# cfc-card.net
KiCad netlist of a schematic drawn in EAGLE
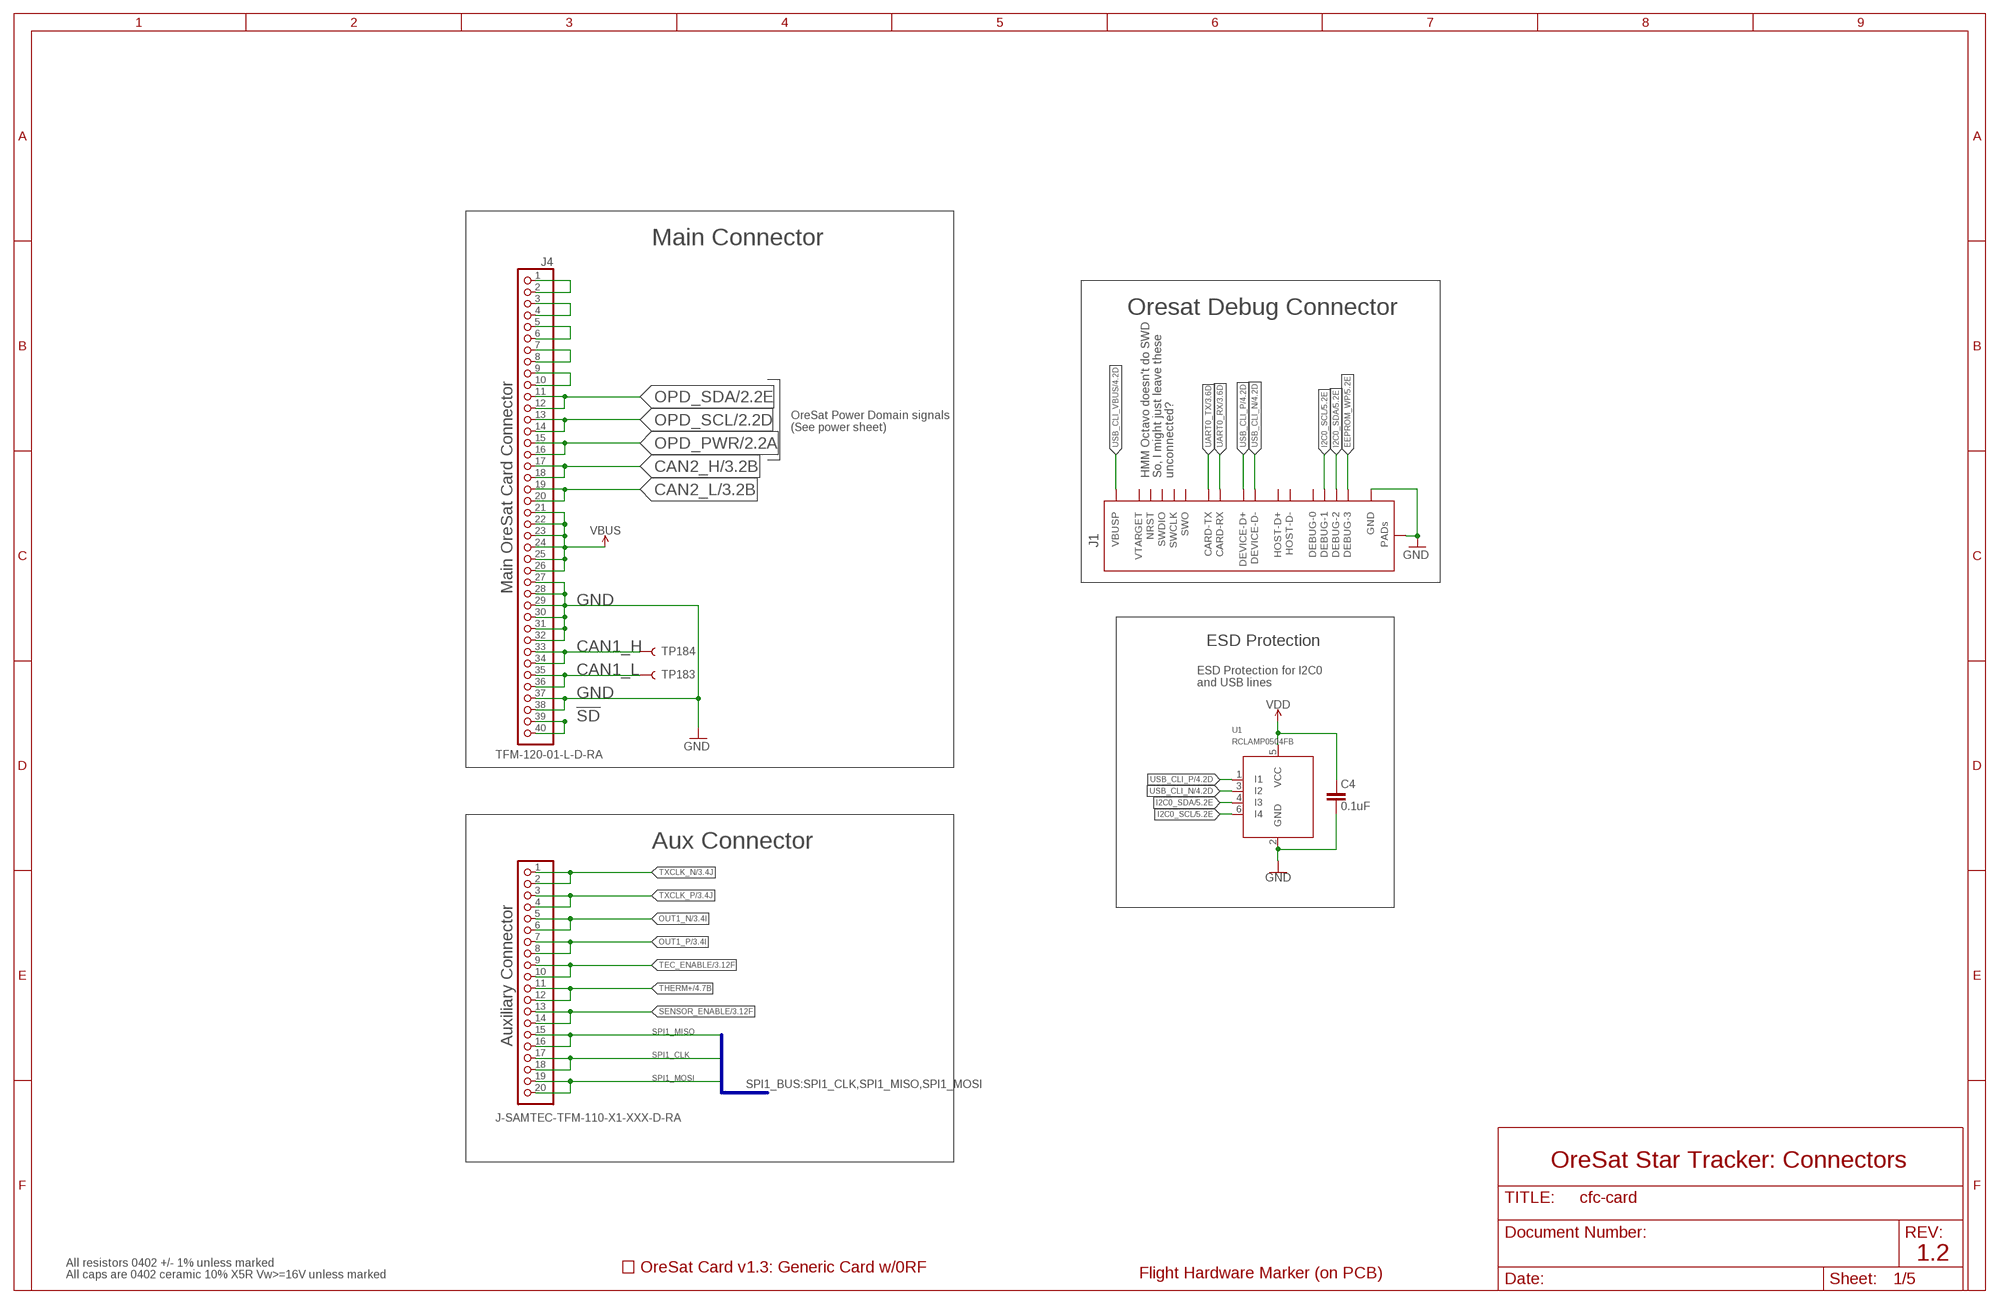
[diagram p0: schematic, sheet 1]
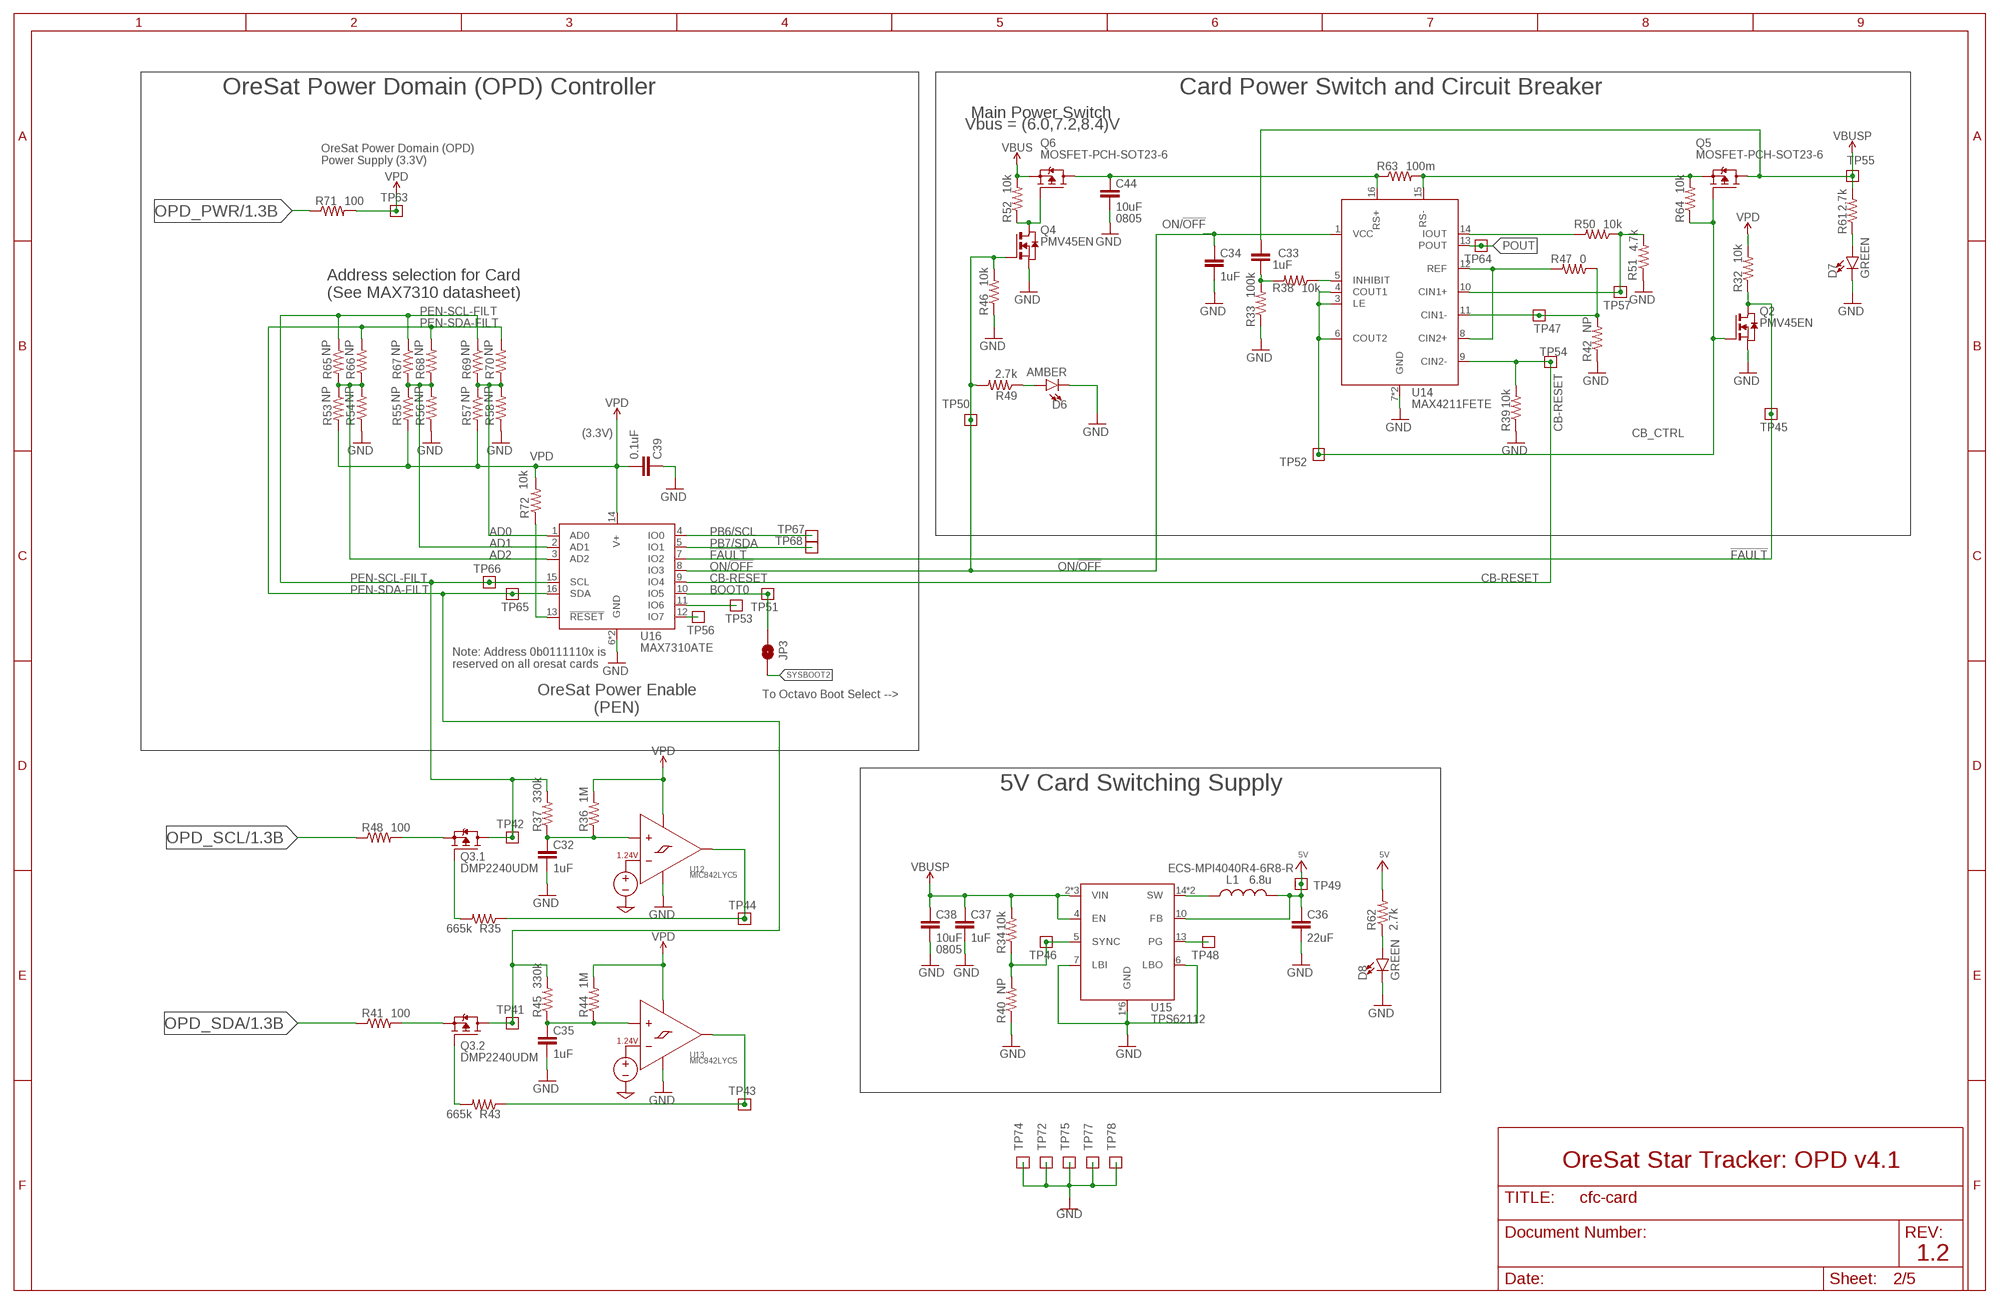
[diagram p1: schematic, sheet 2]
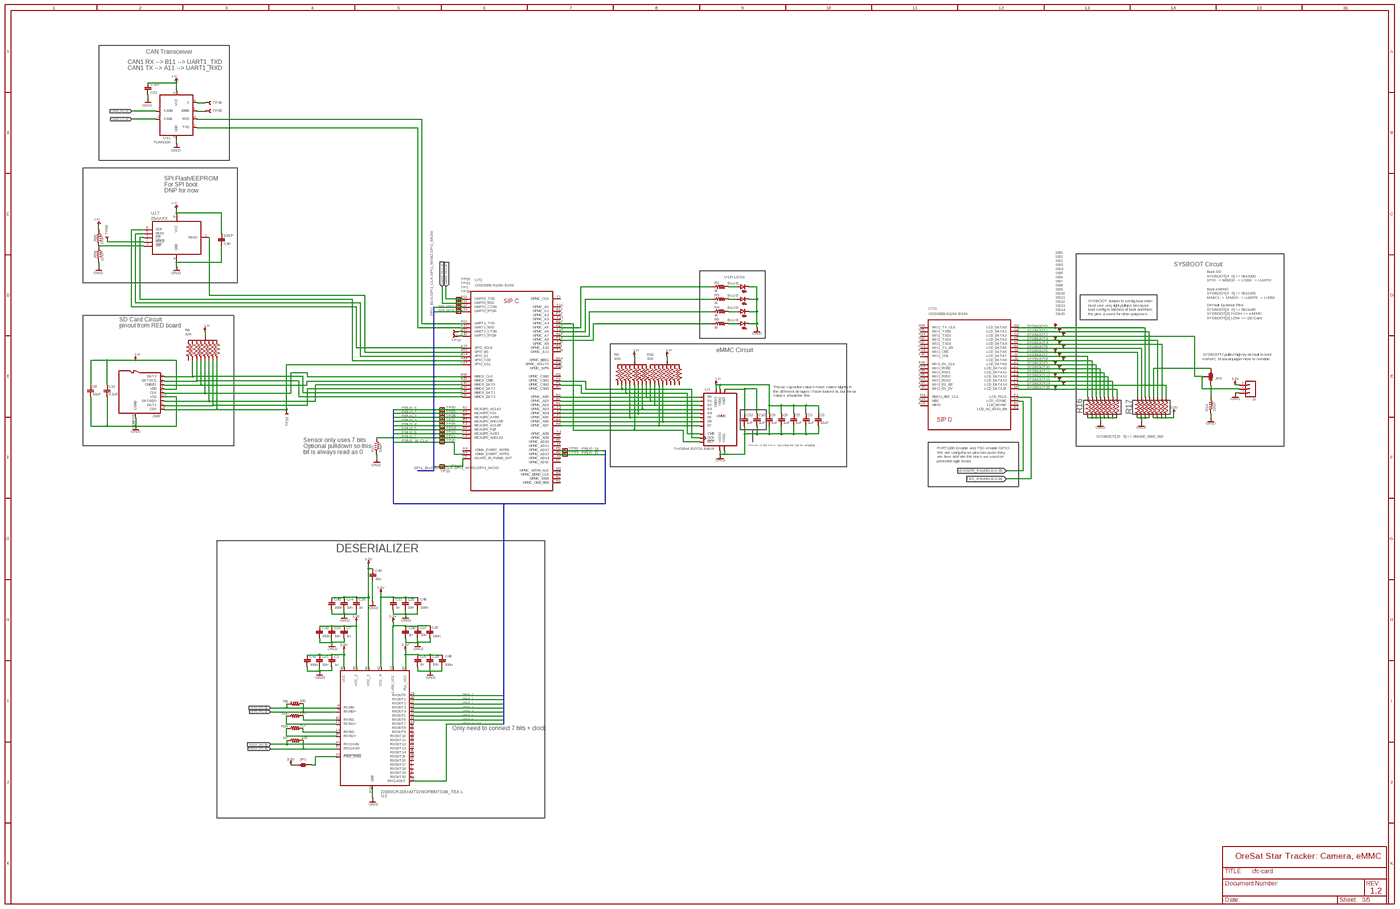
[diagram p2: schematic, sheet 3, overview]
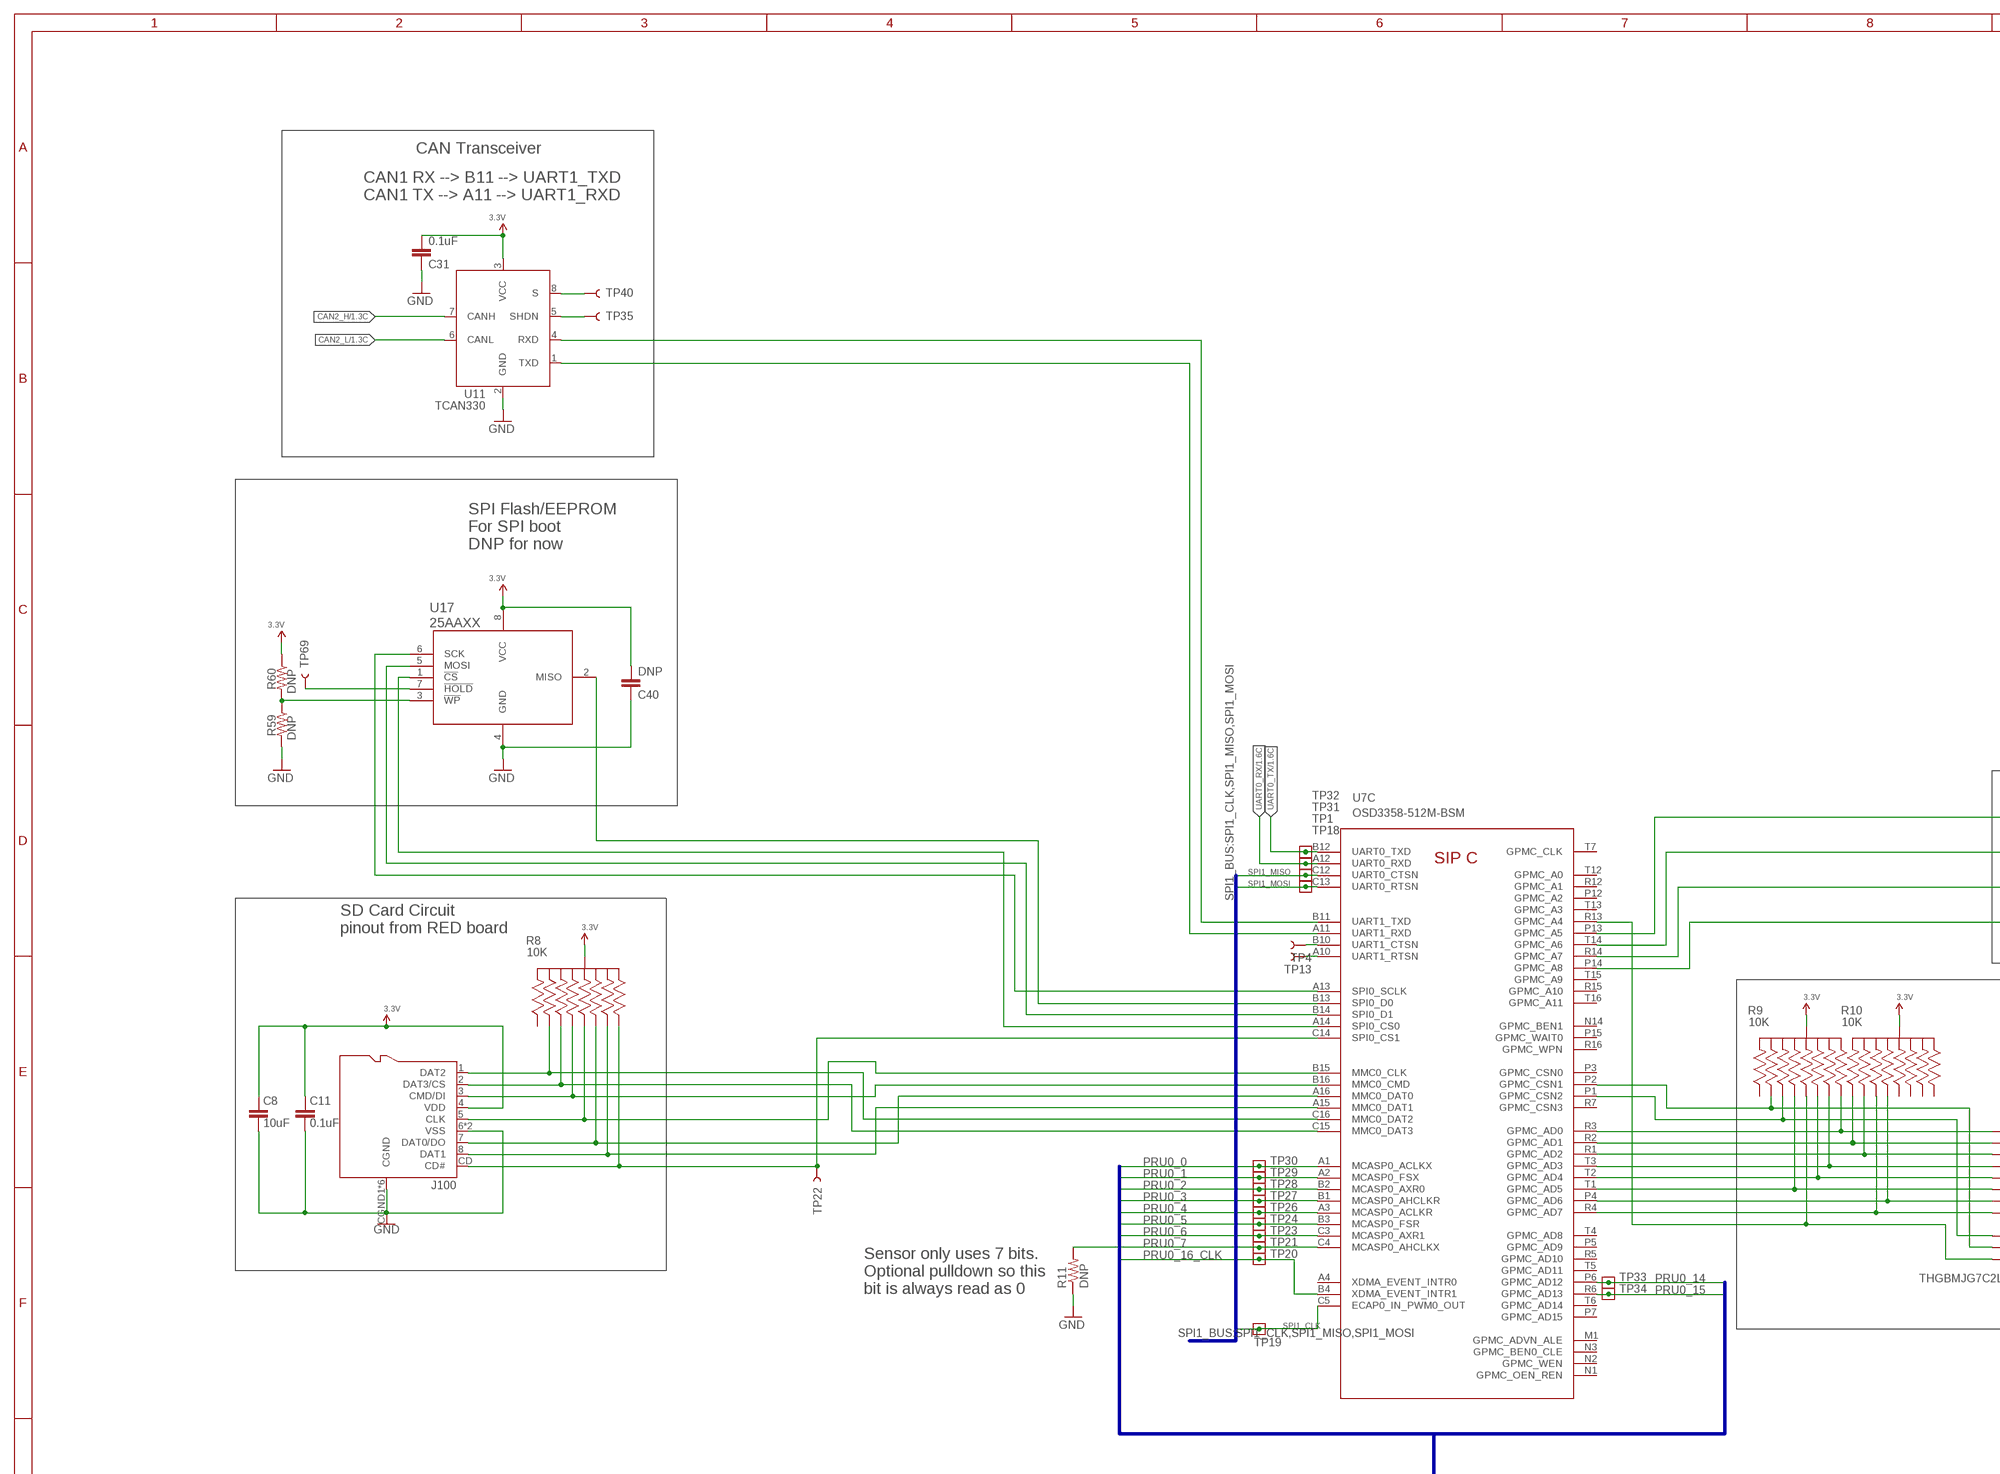
[diagram p3: schematic, sheet 3, part 1 of 4]
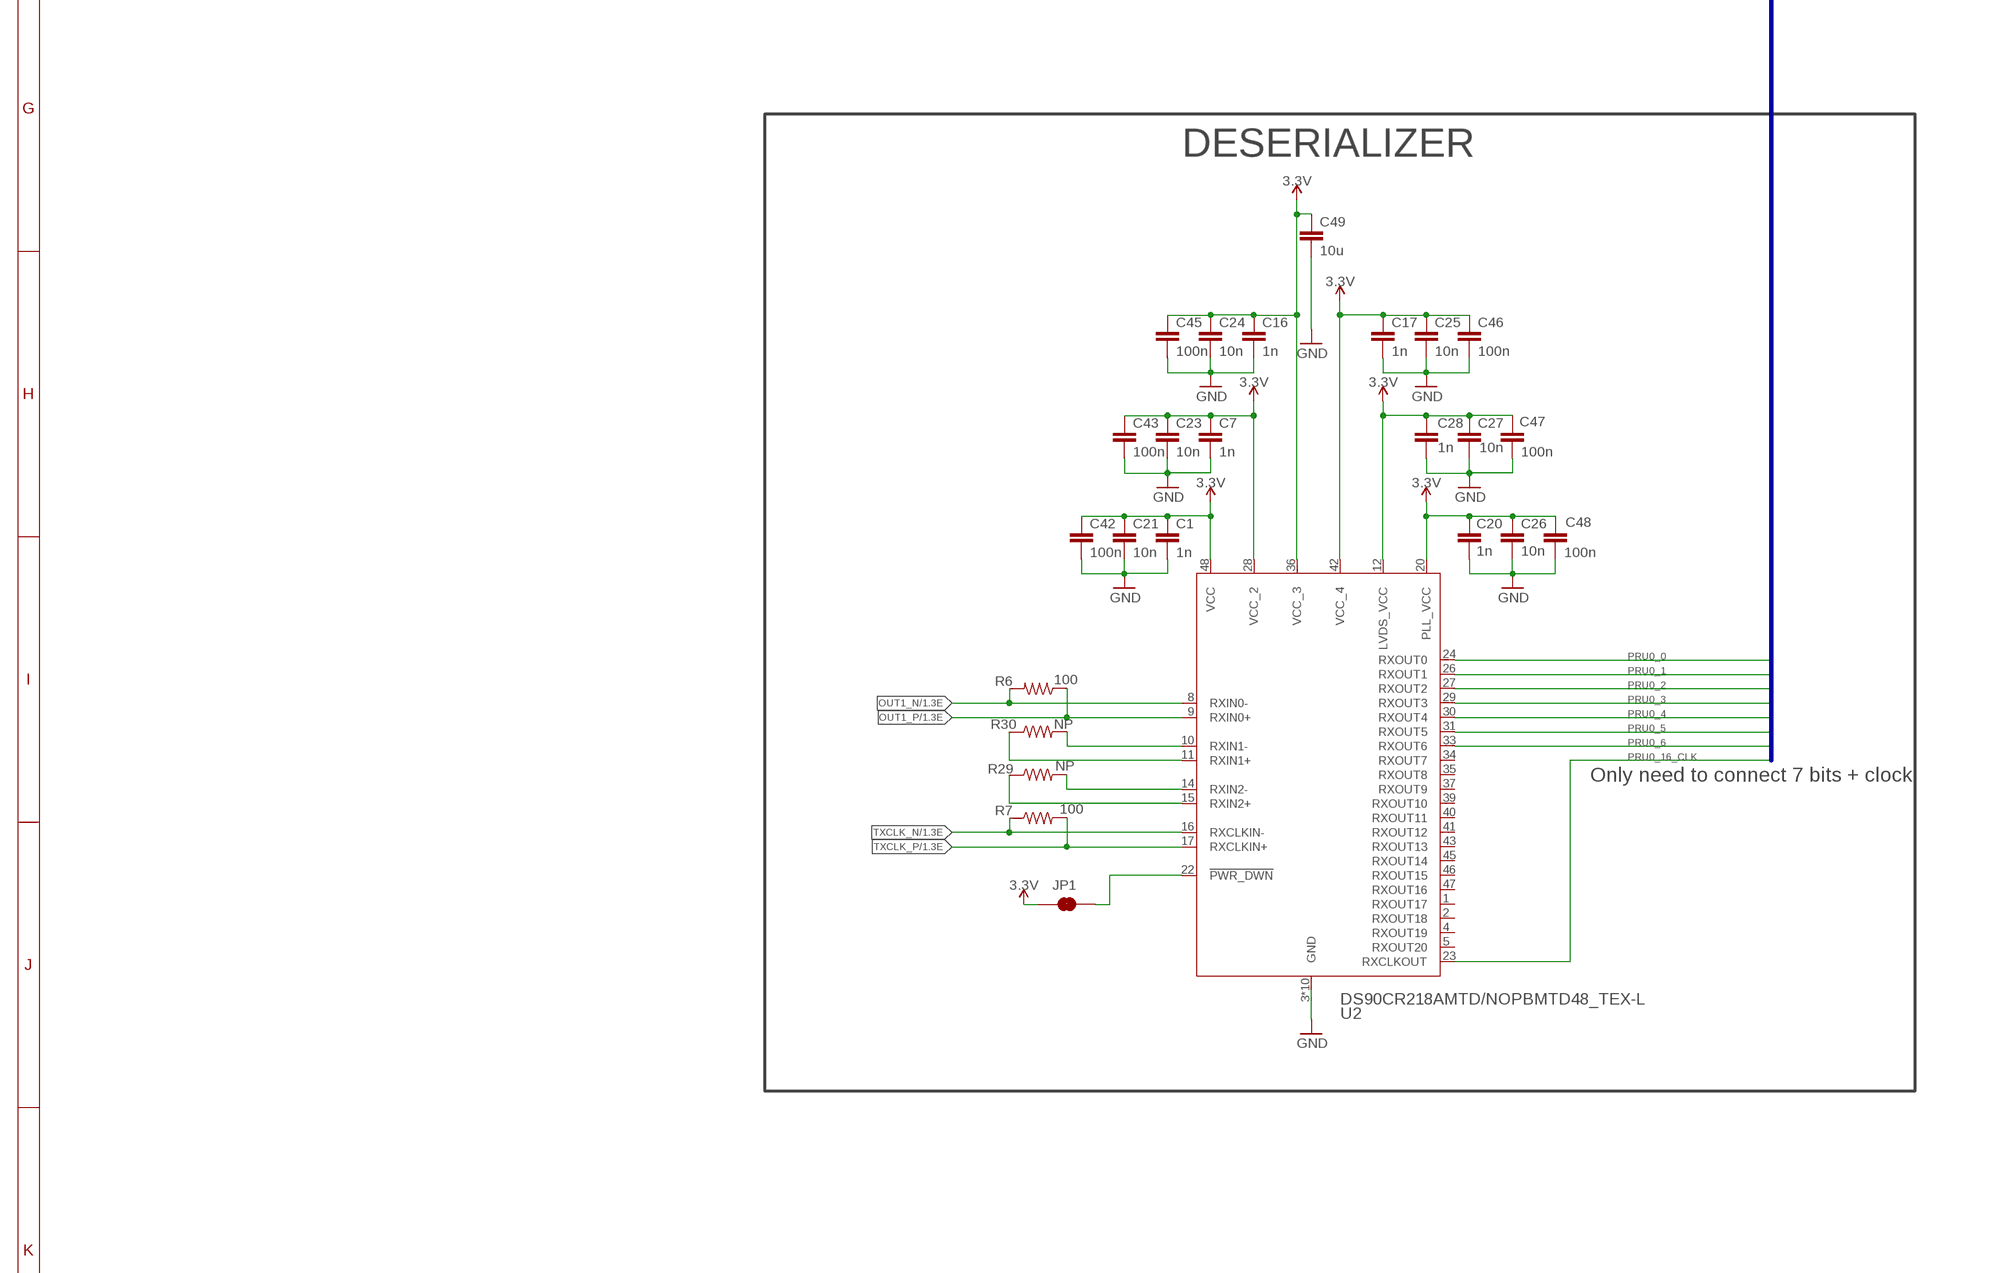
[diagram p4: schematic, sheet 3, part 2 of 4]
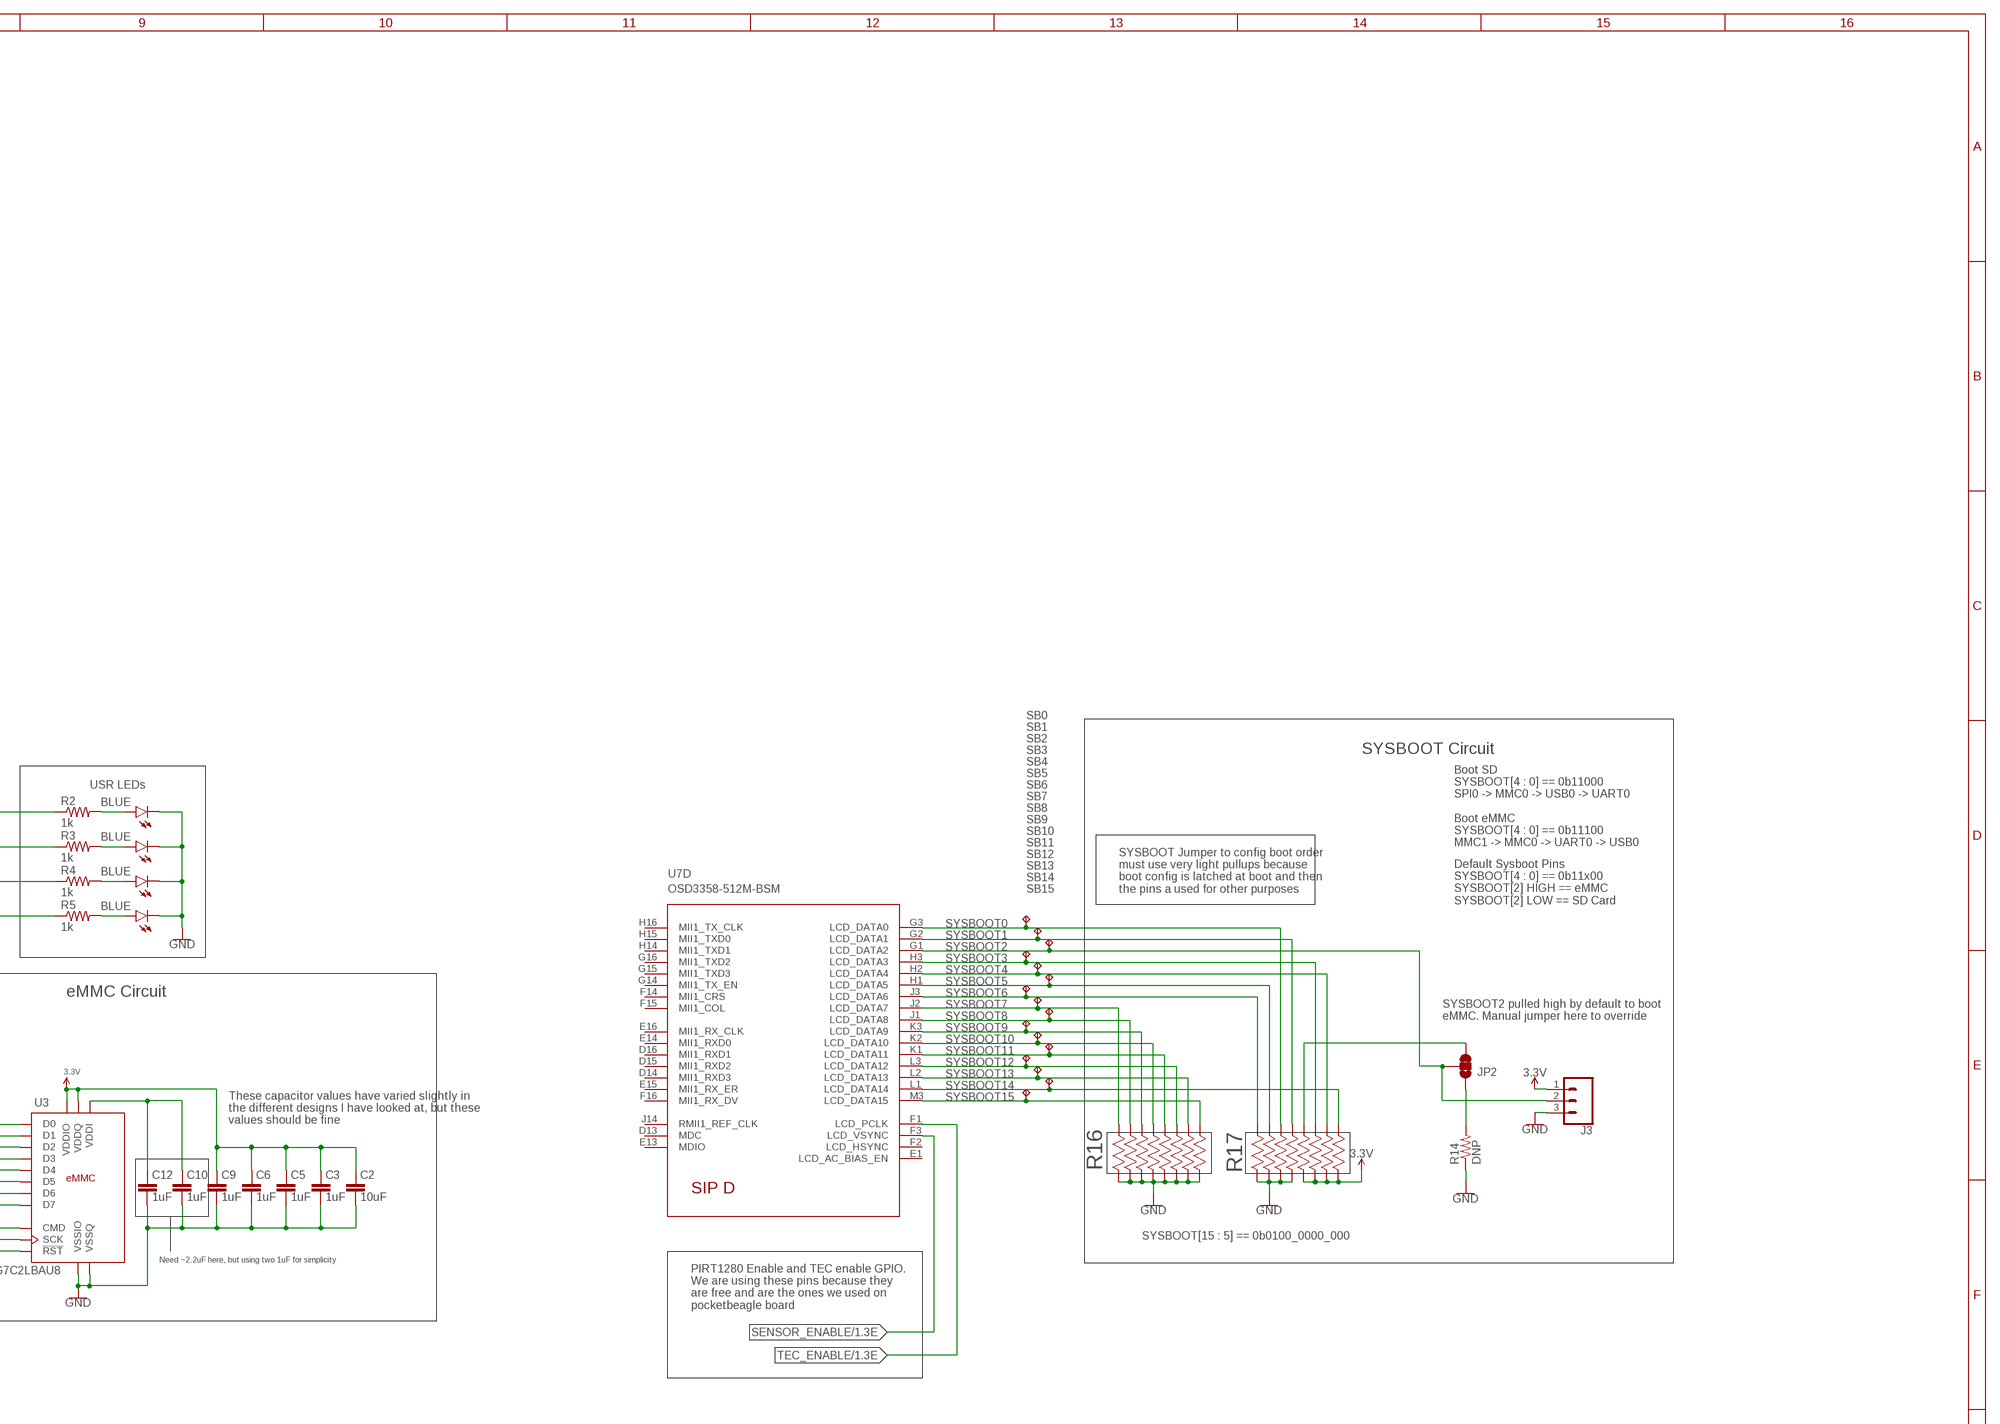
[diagram p5: schematic, sheet 3, part 3 of 4]
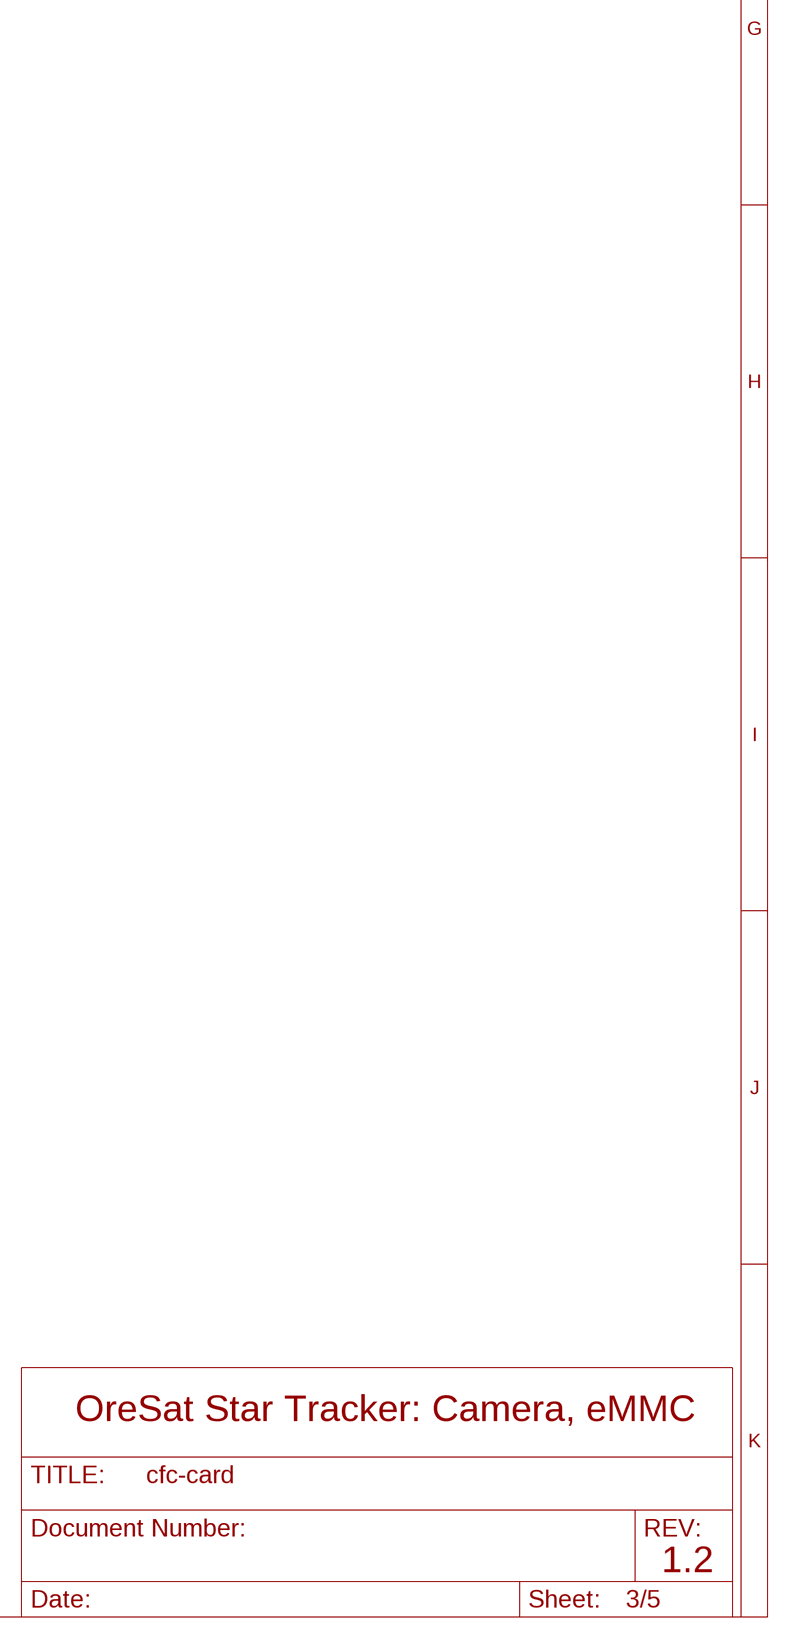
[diagram p6: schematic, sheet 3, part 4 of 4]
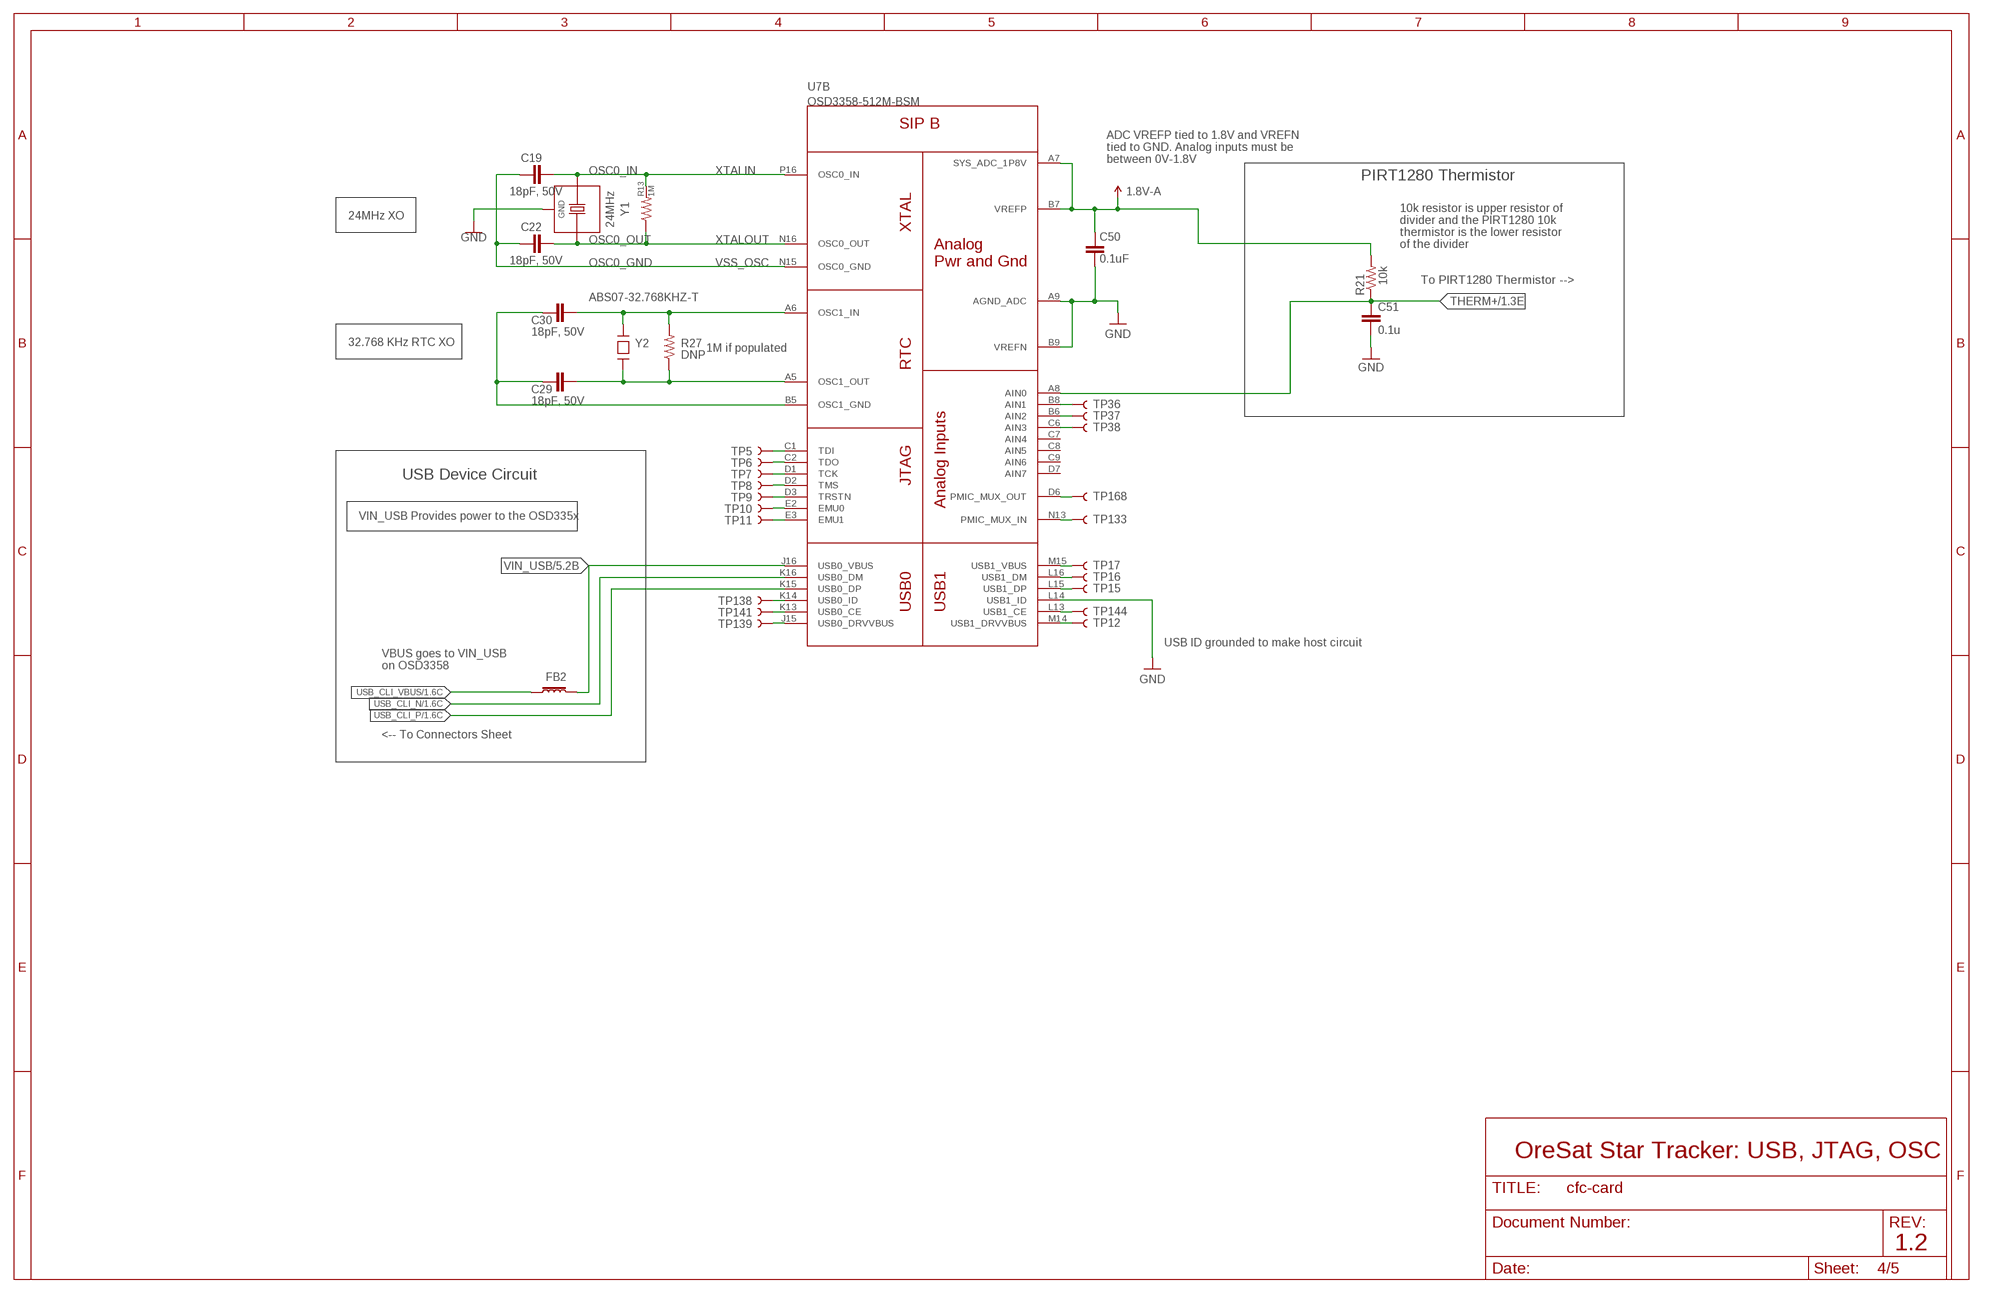
[diagram p7: schematic, sheet 4]
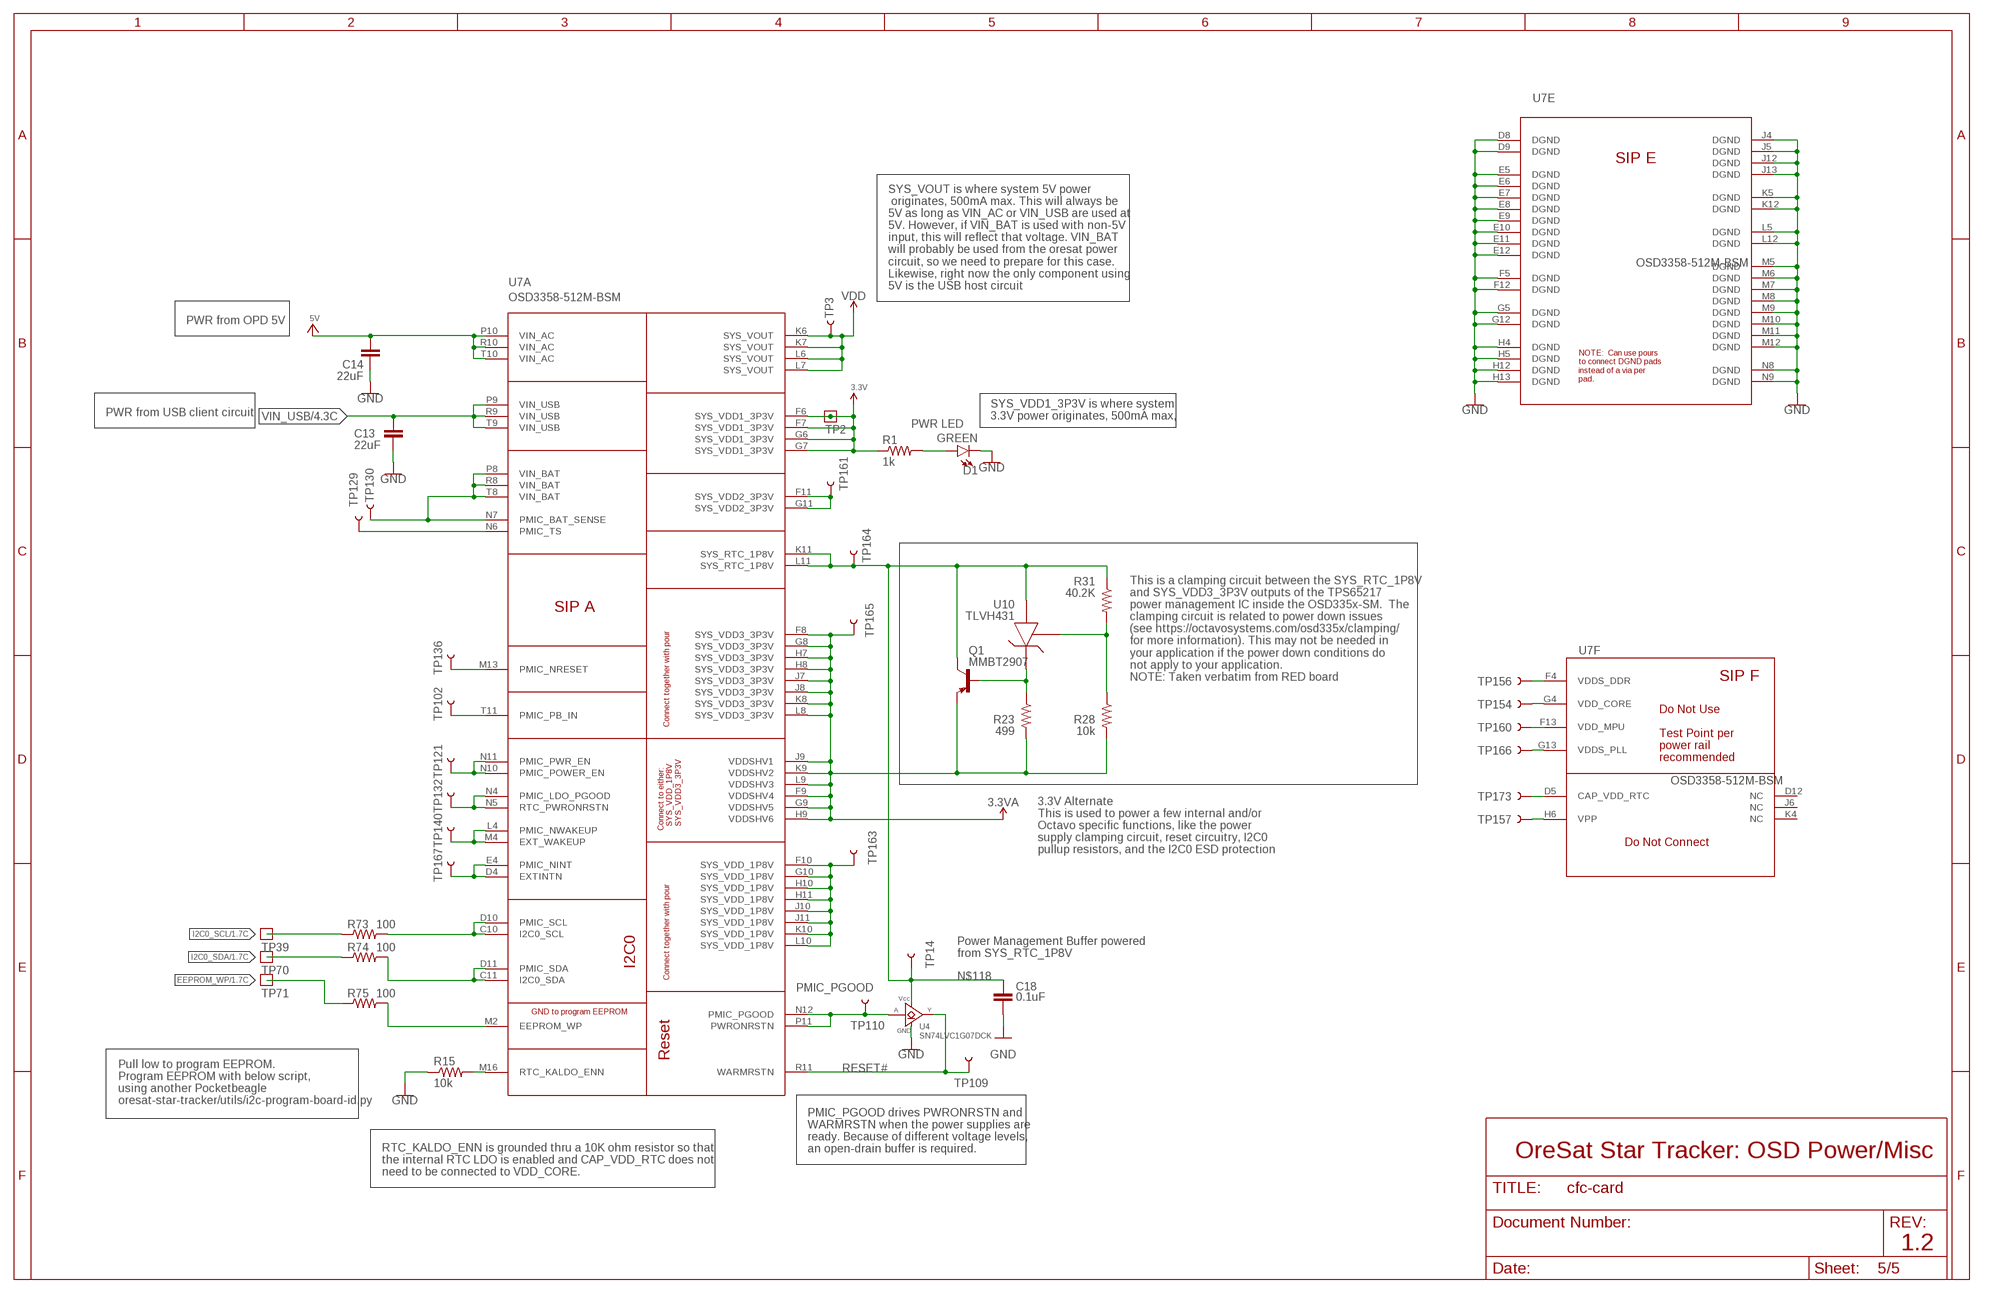
[diagram p8: schematic, sheet 5]

(export (version "E")
  (design (tool "Eeschema 10.0.6"))
  (components
    (comp (ref "C4")
      (value "0.1uF")
      (footprint "eagle-import:.0603-A")
      (libsource (lib "eagle-import") (part "C-EU0603-A"))
    )
    (comp (ref "J1")
      (value "ORESAT-DEBUG-CONNECTOR-ALL")
      (footprint "eagle-import:TE_2-1734592-0")
      (fields (field (name "MPN") "2-1734592-0"))
      (libsource (lib "eagle-import") (part "ORESAT-DEBUG-CONNECTOR-ALL"))
    )
    (comp (ref "J2")
      (value "J-SAMTEC-TFM-110-X1-XXX-D-RA")
      (footprint "eagle-import:J-SAMTEC-TFM-110-X1-XXX-D-RA")
      (fields (field (name "MFR") "Samtec") (field (name "MPN") "TFM-110-01-L-D-RA "))
      (libsource (lib "eagle-import") (part "J-SAMTEC-TFM-110-X1-XXX-D-RA"))
    )
    (comp (ref "J4")
      (value "TFM-120-01-L-D-RA")
      (footprint "eagle-import:J-SAMTEC-TFM-120-X1-XXX-D-RA")
      (libsource (lib "eagle-import") (part "J-SAMTEC-TFM-120-X1-XXX-D-RA"))
    )
    (comp (ref "PCB1")
      (value "ORESAT-CARD-V1.3-GENERIC-0RF")
      (footprint "eagle-import:ORESAT-CARD-V1.3-GENERIC-0RF")
      (libsource (lib "eagle-import") (part "ORESAT-CARD-V1.3-GENERIC-0RF"))
    )
    (comp (ref "TP183")
      (value "TEST-POINT3X4")
      (footprint "eagle-import:PAD.03X.04")
      (libsource (lib "eagle-import") (part "TEST-POINT3X4"))
    )
    (comp (ref "TP184")
      (value "TEST-POINT3X4")
      (footprint "eagle-import:PAD.03X.04")
      (libsource (lib "eagle-import") (part "TEST-POINT3X4"))
    )
    (comp (ref "U$1")
      (value "FLIGHMARKERNEW")
      (footprint "eagle-import:FLIGHTMARKER_NEW_BOARDS")
      (libsource (lib "eagle-import") (part "FLIGHMARKERNEW"))
    )
    (comp (ref "U1")
      (value "RCLAMP0504FB")
      (footprint "eagle-import:SC70-6")
      (fields (field (name "MPN") "RCLAMP0504FBTCT"))
      (libsource (lib "eagle-import") (part "RCLAMP0504FB"))
    )
    (comp (ref "C1")
      (value "1n")
      (footprint "eagle-import:.0402-C-NOSILK")
      (fields (field (name "MFR") "Murata") (field (name "MPN") "GRM155R71H102KA01J"))
      (libsource (lib "eagle-import") (part "C-EU0402-C-NOSILK"))
    )
    (comp (ref "C2")
      (value "10uF")
      (footprint "eagle-import:.0805-B")
      (libsource (lib "eagle-import") (part "C-EU0805-B"))
    )
    (comp (ref "C3")
      (value "1uF")
      (footprint "eagle-import:.0603-A")
      (libsource (lib "eagle-import") (part "C-EU0603-A"))
    )
    (comp (ref "C5")
      (value "1uF")
      (footprint "eagle-import:.0603-A")
      (libsource (lib "eagle-import") (part "C-EU0603-A"))
    )
    (comp (ref "C6")
      (value "1uF")
      (footprint "eagle-import:.0603-A")
      (libsource (lib "eagle-import") (part "C-EU0603-A"))
    )
    (comp (ref "C7")
      (value "1n")
      (footprint "eagle-import:.0402-C-NOSILK")
      (fields (field (name "MFR") "Murata") (field (name "MPN") "GRM155R71H102KA01J"))
      (libsource (lib "eagle-import") (part "C-EU0402-C-NOSILK"))
    )
    (comp (ref "C8")
      (value "10uF")
      (footprint "eagle-import:.0805-B")
      (libsource (lib "eagle-import") (part "C-EU0805-B"))
    )
    (comp (ref "C9")
      (value "1uF")
      (footprint "eagle-import:.0603-A")
      (libsource (lib "eagle-import") (part "C-EU0603-A"))
    )
    (comp (ref "C10")
      (value "1uF")
      (footprint "eagle-import:.0603-A")
      (libsource (lib "eagle-import") (part "C-EU0603-A"))
    )
    (comp (ref "C11")
      (value "0.1uF")
      (footprint "eagle-import:.0603-A")
      (libsource (lib "eagle-import") (part "C-EU0603-A"))
    )
    (comp (ref "C12")
      (value "1uF")
      (footprint "eagle-import:.0603-A")
      (libsource (lib "eagle-import") (part "C-EU0603-A"))
    )
    (comp (ref "C16")
      (value "1n")
      (footprint "eagle-import:.0402-C-NOSILK")
      (fields (field (name "MFR") "Murata") (field (name "MPN") "GRM155R71H102KA01J"))
      (libsource (lib "eagle-import") (part "C-EU0402-C-NOSILK"))
    )
    (comp (ref "C17")
      (value "1n")
      (footprint "eagle-import:.0402-C-NOSILK")
      (fields (field (name "MFR") "Murata") (field (name "MPN") "GRM155R71H102KA01J"))
      (libsource (lib "eagle-import") (part "C-EU0402-C-NOSILK"))
    )
    (comp (ref "C20")
      (value "1n")
      (footprint "eagle-import:.0402-C-NOSILK")
      (fields (field (name "MFR") "Murata") (field (name "MPN") "GRM155R71H102KA01J"))
      (libsource (lib "eagle-import") (part "C-EU0402-C-NOSILK"))
    )
    (comp (ref "C21")
      (value "10n")
      (footprint "eagle-import:.0402-C-NOSILK")
      (fields (field (name "MFR") "Kemet") (field (name "MPN") "C0603C103M5RACTU"))
      (libsource (lib "eagle-import") (part "C-EU0402-C-NOSILK"))
    )
    (comp (ref "C23")
      (value "10n")
      (footprint "eagle-import:.0402-C-NOSILK")
      (fields (field (name "MFR") "Kemet") (field (name "MPN") "C0603C103M5RACTU"))
      (libsource (lib "eagle-import") (part "C-EU0402-C-NOSILK"))
    )
    (comp (ref "C24")
      (value "10n")
      (footprint "eagle-import:.0402-C-NOSILK")
      (fields (field (name "MFR") "Kemet") (field (name "MPN") "C0603C103M5RACTU"))
      (libsource (lib "eagle-import") (part "C-EU0402-C-NOSILK"))
    )
    (comp (ref "C25")
      (value "10n")
      (footprint "eagle-import:.0402-C-NOSILK")
      (fields (field (name "MFR") "Kemet") (field (name "MPN") "C0603C103M5RACTU"))
      (libsource (lib "eagle-import") (part "C-EU0402-C-NOSILK"))
    )
    (comp (ref "C26")
      (value "10n")
      (footprint "eagle-import:.0402-C-NOSILK")
      (fields (field (name "MFR") "Kemet") (field (name "MPN") "C0603C103M5RACTU"))
      (libsource (lib "eagle-import") (part "C-EU0402-C-NOSILK"))
    )
    (comp (ref "C27")
      (value "10n")
      (footprint "eagle-import:.0402-C-NOSILK")
      (fields (field (name "MFR") "Kemet") (field (name "MPN") "C0603C103M5RACTU"))
      (libsource (lib "eagle-import") (part "C-EU0402-C-NOSILK"))
    )
    (comp (ref "C28")
      (value "1n")
      (footprint "eagle-import:.0402-C-NOSILK")
      (fields (field (name "MFR") "Murata") (field (name "MPN") "GRM155R71H102KA01J"))
      (libsource (lib "eagle-import") (part "C-EU0402-C-NOSILK"))
    )
    (comp (ref "C31")
      (value "0.1uF")
      (footprint "eagle-import:.0603-A")
      (libsource (lib "eagle-import") (part "C-EU0603-A"))
    )
    (comp (ref "C40")
      (value "DNP")
      (footprint "eagle-import:.0603-A")
      (libsource (lib "eagle-import") (part "C-EU0603-A"))
    )
    (comp (ref "C42")
      (value "100n")
      (footprint "eagle-import:.0402-C-NOSILK")
      (fields (field (name "MFR") "Kemet") (field (name "MPN") "C0805C104Z5VACTU"))
      (libsource (lib "eagle-import") (part "C-EU0402-C-NOSILK"))
    )
    (comp (ref "C43")
      (value "100n")
      (footprint "eagle-import:.0402-C-NOSILK")
      (fields (field (name "MFR") "Kemet") (field (name "MPN") "C0805C104Z5VACTU"))
      (libsource (lib "eagle-import") (part "C-EU0402-C-NOSILK"))
    )
    (comp (ref "C45")
      (value "100n")
      (footprint "eagle-import:.0402-C-NOSILK")
      (fields (field (name "MFR") "Kemet") (field (name "MPN") "C0805C104Z5VACTU"))
      (libsource (lib "eagle-import") (part "C-EU0402-C-NOSILK"))
    )
    (comp (ref "C46")
      (value "100n")
      (footprint "eagle-import:.0402-C-NOSILK")
      (fields (field (name "MFR") "Kemet") (field (name "MPN") "C0805C104Z5VACTU"))
      (libsource (lib "eagle-import") (part "C-EU0402-C-NOSILK"))
    )
    (comp (ref "C47")
      (value "100n")
      (footprint "eagle-import:.0402-C-NOSILK")
      (fields (field (name "MFR") "Kemet") (field (name "MPN") "C0805C104Z5VACTU"))
      (libsource (lib "eagle-import") (part "C-EU0402-C-NOSILK"))
    )
    (comp (ref "C48")
      (value "100n")
      (footprint "eagle-import:.0402-C-NOSILK")
      (fields (field (name "MFR") "Kemet") (field (name "MPN") "C0805C104Z5VACTU"))
      (libsource (lib "eagle-import") (part "C-EU0402-C-NOSILK"))
    )
    (comp (ref "C49")
      (value "10u")
      (footprint "eagle-import:.0603-C-NOSILK")
      (fields (field (name "MFR") "Murata") (field (name "MPN") "GRM188R61A106KE69J"))
      (libsource (lib "eagle-import") (part "C-EU0603-C-NOSILK"))
    )
    (comp (ref "D2")
      (value "BLUE")
      (footprint "eagle-import:LED-0603")
      (libsource (lib "eagle-import") (part "LED-BLUE0603"))
    )
    (comp (ref "D3")
      (value "BLUE")
      (footprint "eagle-import:LED-0603")
      (libsource (lib "eagle-import") (part "LED-BLUE0603"))
    )
    (comp (ref "D4")
      (value "BLUE")
      (footprint "eagle-import:LED-0603")
      (libsource (lib "eagle-import") (part "LED-BLUE0603"))
    )
    (comp (ref "D5")
      (value "BLUE")
      (footprint "eagle-import:LED-0603")
      (libsource (lib "eagle-import") (part "LED-BLUE0603"))
    )
    (comp (ref "J3")
      (value "CONN_03LONGPADS")
      (footprint "eagle-import:1X03_LONGPADS")
      (libsource (lib "eagle-import") (part "CONN_03LONGPADS"))
    )
    (comp (ref "J100")
      (value "DM3BT-DSF-PEJS")
      (footprint "eagle-import:DM3BT-DSF-PEJS")
      (libsource (lib "eagle-import") (part "DM3BT-DSF-PEJS"))
    )
    (comp (ref "JP1")
      (value "JUMPER-SMT_2_NC_TRACE_SILK")
      (footprint "eagle-import:SMT-JUMPER_2_NC_TRACE_SILK")
      (libsource (lib "eagle-import") (part "JUMPER-SMT_2_NC_TRACE_SILK"))
    )
    (comp (ref "JP2")
      (value "JUMPER-SMT_3_1-NC_TRACE_SILK")
      (footprint "eagle-import:SMT-JUMPER_3_1-NC_TRACE_SILK")
      (libsource (lib "eagle-import") (part "JUMPER-SMT_3_1-NC_TRACE_SILK"))
    )
    (comp (ref "R2")
      (value "1k")
      (footprint "eagle-import:.0603-A")
      (libsource (lib "eagle-import") (part "R-US_0603-A"))
    )
    (comp (ref "R3")
      (value "1k")
      (footprint "eagle-import:.0603-A")
      (libsource (lib "eagle-import") (part "R-US_0603-A"))
    )
    (comp (ref "R4")
      (value "1k")
      (footprint "eagle-import:.0603-A")
      (libsource (lib "eagle-import") (part "R-US_0603-A"))
    )
    (comp (ref "R5")
      (value "1k")
      (footprint "eagle-import:.0603-A")
      (libsource (lib "eagle-import") (part "R-US_0603-A"))
    )
    (comp (ref "R6")
      (value "100")
      (footprint "eagle-import:.0402-C-NOSILK")
      (fields (field (name "MFR") "Yageo") (field (name "MPN") "RC0201FR-07100RL"))
      (libsource (lib "eagle-import") (part "R-US_0402-C-NOSILK"))
    )
    (comp (ref "R7")
      (value "100")
      (footprint "eagle-import:.0402-C-NOSILK")
      (fields (field (name "MFR") "Yageo") (field (name "MPN") "RC0201FR-07100RL"))
      (libsource (lib "eagle-import") (part "R-US_0402-C-NOSILK"))
    )
    (comp (ref "R8")
      (value "10K")
      (footprint "eagle-import:ARRAY_EXBA-M")
      (fields (field (name "MFR") "Panasonic Electronic Components"))
      (libsource (lib "eagle-import") (part "EXB-A10P391JC_ARRAY_EXBA-M"))
    )
    (comp (ref "R9")
      (value "10K")
      (footprint "eagle-import:ARRAY_EXBA-M")
      (fields (field (name "MFR") "Panasonic Electronic Components"))
      (libsource (lib "eagle-import") (part "EXB-A10P391JC_ARRAY_EXBA-M"))
    )
    (comp (ref "R10")
      (value "10K")
      (footprint "eagle-import:ARRAY_EXBA-M")
      (fields (field (name "MFR") "Panasonic Electronic Components") (field (name "DPN") "U7103CT-ND"))
      (libsource (lib "eagle-import") (part "EXB-A10P391JC_ARRAY_EXBA-M"))
    )
    (comp (ref "R11")
      (value "DNP")
      (footprint "eagle-import:.0603-A")
      (libsource (lib "eagle-import") (part "R-US_0603-A"))
    )
    (comp (ref "R14")
      (value "DNP")
      (footprint "eagle-import:.0603-A")
      (libsource (lib "eagle-import") (part "R-US_0603-A"))
    )
    (comp (ref "R16")
      (value "100k")
      (footprint "eagle-import:RES_EXB2HV")
      (fields (field (name "MPN") "EXB-2HV103JV"))
      (libsource (lib "eagle-import") (part "EXB-2HV103JV"))
    )
    (comp (ref "R17")
      (value "100k")
      (footprint "eagle-import:RES_EXB2HV")
      (fields (field (name "MPN") "EXB-2HV103JV"))
      (libsource (lib "eagle-import") (part "EXB-2HV103JV"))
    )
    (comp (ref "R29")
      (value "NP")
      (footprint "eagle-import:.0402-C-NOSILK")
      (fields (field (name "MFR") "Yageo") (field (name "MPN") "RC0201FR-07100RL"))
      (libsource (lib "eagle-import") (part "R-US_0402-C-NOSILK"))
    )
    (comp (ref "R30")
      (value "NP")
      (footprint "eagle-import:.0402-C-NOSILK")
      (fields (field (name "MFR") "Yageo") (field (name "MPN") "RC0201FR-07100RL"))
      (libsource (lib "eagle-import") (part "R-US_0402-C-NOSILK"))
    )
    (comp (ref "R59")
      (value "DNP")
      (footprint "eagle-import:.0603-A")
      (libsource (lib "eagle-import") (part "R-US_0603-A"))
    )
    (comp (ref "R60")
      (value "DNP")
      (footprint "eagle-import:.0603-A")
      (libsource (lib "eagle-import") (part "R-US_0603-A"))
    )
    (comp (ref "SB0")
      (value "TEST-POINT-SMALL")
      (footprint "eagle-import:TEST-POINT-SMALL")
      (libsource (lib "eagle-import") (part "TEST-POINT-SMALL"))
    )
    (comp (ref "SB1")
      (value "TEST-POINT-SMALL")
      (footprint "eagle-import:TEST-POINT-SMALL")
      (libsource (lib "eagle-import") (part "TEST-POINT-SMALL"))
    )
    (comp (ref "SB2")
      (value "TEST-POINT-SMALL")
      (footprint "eagle-import:TEST-POINT-SMALL")
      (libsource (lib "eagle-import") (part "TEST-POINT-SMALL"))
    )
    (comp (ref "SB3")
      (value "TEST-POINT-SMALL")
      (footprint "eagle-import:TEST-POINT-SMALL")
      (libsource (lib "eagle-import") (part "TEST-POINT-SMALL"))
    )
    (comp (ref "SB4")
      (value "TEST-POINT-SMALL")
      (footprint "eagle-import:TEST-POINT-SMALL")
      (libsource (lib "eagle-import") (part "TEST-POINT-SMALL"))
    )
    (comp (ref "SB5")
      (value "TEST-POINT-SMALL")
      (footprint "eagle-import:TEST-POINT-SMALL")
      (libsource (lib "eagle-import") (part "TEST-POINT-SMALL"))
    )
    (comp (ref "SB6")
      (value "TEST-POINT-SMALL")
      (footprint "eagle-import:TEST-POINT-SMALL")
      (libsource (lib "eagle-import") (part "TEST-POINT-SMALL"))
    )
    (comp (ref "SB7")
      (value "TEST-POINT-SMALL")
      (footprint "eagle-import:TEST-POINT-SMALL")
      (libsource (lib "eagle-import") (part "TEST-POINT-SMALL"))
    )
    (comp (ref "SB8")
      (value "TEST-POINT-SMALL")
      (footprint "eagle-import:TEST-POINT-SMALL")
      (libsource (lib "eagle-import") (part "TEST-POINT-SMALL"))
    )
    (comp (ref "SB9")
      (value "TEST-POINT-SMALL")
      (footprint "eagle-import:TEST-POINT-SMALL")
      (libsource (lib "eagle-import") (part "TEST-POINT-SMALL"))
    )
    (comp (ref "SB10")
      (value "TEST-POINT-SMALL")
      (footprint "eagle-import:TEST-POINT-SMALL")
      (libsource (lib "eagle-import") (part "TEST-POINT-SMALL"))
    )
    (comp (ref "SB11")
      (value "TEST-POINT-SMALL")
      (footprint "eagle-import:TEST-POINT-SMALL")
      (libsource (lib "eagle-import") (part "TEST-POINT-SMALL"))
    )
    (comp (ref "SB12")
      (value "TEST-POINT-SMALL")
      (footprint "eagle-import:TEST-POINT-SMALL")
      (libsource (lib "eagle-import") (part "TEST-POINT-SMALL"))
    )
    (comp (ref "SB13")
      (value "TEST-POINT-SMALL")
      (footprint "eagle-import:TEST-POINT-SMALL")
      (libsource (lib "eagle-import") (part "TEST-POINT-SMALL"))
    )
    (comp (ref "SB14")
      (value "TEST-POINT-SMALL")
      (footprint "eagle-import:TEST-POINT-SMALL")
      (libsource (lib "eagle-import") (part "TEST-POINT-SMALL"))
    )
    (comp (ref "SB15")
      (value "TEST-POINT-SMALL")
      (footprint "eagle-import:TEST-POINT-SMALL")
      (libsource (lib "eagle-import") (part "TEST-POINT-SMALL"))
    )
    (comp (ref "TP1")
      (value "TEST-POINT")
      (footprint "eagle-import:2MM-TEST-POINT")
      (libsource (lib "eagle-import") (part "TEST-POINT"))
    )
    (comp (ref "TP4")
      (value "TEST-POINT3X4")
      (footprint "eagle-import:PAD.03X.04")
      (libsource (lib "eagle-import") (part "TEST-POINT3X4"))
    )
    (comp (ref "TP13")
      (value "TEST-POINT3X4")
      (footprint "eagle-import:PAD.03X.04")
      (libsource (lib "eagle-import") (part "TEST-POINT3X4"))
    )
    (comp (ref "TP18")
      (value "TEST-POINT")
      (footprint "eagle-import:2MM-TEST-POINT")
      (libsource (lib "eagle-import") (part "TEST-POINT"))
    )
    (comp (ref "TP19")
      (value "TEST-POINT")
      (footprint "eagle-import:2MM-TEST-POINT")
      (libsource (lib "eagle-import") (part "TEST-POINT"))
    )
    (comp (ref "TP20")
      (value "TEST-POINT")
      (footprint "eagle-import:2MM-TEST-POINT")
      (libsource (lib "eagle-import") (part "TEST-POINT"))
    )
    (comp (ref "TP21")
      (value "TEST-POINT")
      (footprint "eagle-import:2MM-TEST-POINT")
      (libsource (lib "eagle-import") (part "TEST-POINT"))
    )
    (comp (ref "TP22")
      (value "TEST-POINT3X4")
      (footprint "eagle-import:PAD.03X.04")
      (libsource (lib "eagle-import") (part "TEST-POINT3X4"))
    )
    (comp (ref "TP23")
      (value "TEST-POINT")
      (footprint "eagle-import:2MM-TEST-POINT")
      (libsource (lib "eagle-import") (part "TEST-POINT"))
    )
    (comp (ref "TP24")
      (value "TEST-POINT")
      (footprint "eagle-import:2MM-TEST-POINT")
      (libsource (lib "eagle-import") (part "TEST-POINT"))
    )
    (comp (ref "TP26")
      (value "TEST-POINT")
      (footprint "eagle-import:2MM-TEST-POINT")
      (libsource (lib "eagle-import") (part "TEST-POINT"))
    )
    (comp (ref "TP27")
      (value "TEST-POINT")
      (footprint "eagle-import:2MM-TEST-POINT")
      (libsource (lib "eagle-import") (part "TEST-POINT"))
    )
    (comp (ref "TP28")
      (value "TEST-POINT")
      (footprint "eagle-import:2MM-TEST-POINT")
      (libsource (lib "eagle-import") (part "TEST-POINT"))
    )
    (comp (ref "TP29")
      (value "TEST-POINT")
      (footprint "eagle-import:2MM-TEST-POINT")
      (libsource (lib "eagle-import") (part "TEST-POINT"))
    )
    (comp (ref "TP30")
      (value "TEST-POINT")
      (footprint "eagle-import:2MM-TEST-POINT")
      (libsource (lib "eagle-import") (part "TEST-POINT"))
    )
    (comp (ref "TP31")
      (value "TEST-POINT")
      (footprint "eagle-import:2MM-TEST-POINT")
      (libsource (lib "eagle-import") (part "TEST-POINT"))
    )
    (comp (ref "TP32")
      (value "TEST-POINT")
      (footprint "eagle-import:2MM-TEST-POINT")
      (libsource (lib "eagle-import") (part "TEST-POINT"))
    )
    (comp (ref "TP33")
      (value "TEST-POINT")
      (footprint "eagle-import:2MM-TEST-POINT")
      (libsource (lib "eagle-import") (part "TEST-POINT"))
    )
    (comp (ref "TP34")
      (value "TEST-POINT")
      (footprint "eagle-import:2MM-TEST-POINT")
      (libsource (lib "eagle-import") (part "TEST-POINT"))
    )
    (comp (ref "TP35")
      (value "TEST-POINT3X4")
      (footprint "eagle-import:PAD.03X.04")
      (libsource (lib "eagle-import") (part "TEST-POINT3X4"))
    )
    (comp (ref "TP40")
      (value "TEST-POINT3X4")
      (footprint "eagle-import:PAD.03X.04")
      (libsource (lib "eagle-import") (part "TEST-POINT3X4"))
    )
    (comp (ref "TP69")
      (value "TEST-POINT3X4")
      (footprint "eagle-import:PAD.03X.04")
      (libsource (lib "eagle-import") (part "TEST-POINT3X4"))
    )
    (comp (ref "U2")
      (value "DS90CR218AMTD/NOPBMTD48_TEX-L")
      (footprint "eagle-import:MTD48_TEX-L")
      (fields (field (name "MFR") "Texas Instruments") (field (name "MPN") "DS90CR218AMTD/NOPB"))
      (libsource (lib "eagle-import") (part "DS90CR218AMTD/NOPBMTD48_TEX-L"))
    )
    (comp (ref "U3")
      (value "THGBMJG7C2LBAU8")
      (footprint "eagle-import:BGA-153(11.5X13)(EMMC-BA)")
      (libsource (lib "eagle-import") (part "EMMC+RESET+5.1-COMPATIBLE-BA"))
    )
    (comp (ref "U7")
      (value "OSD3358-512M-BSM")
      (footprint "eagle-import:OSD335X-BGA-256")
      (fields (field (name "MFR") "Octavo Systems"))
      (libsource (lib "eagle-import") (part "OSD3358-512M-BSM"))
    )
    (comp (ref "U11")
      (value "TCAN330")
      (footprint "eagle-import:SOT23-8_TI-DCN")
      (fields (field (name "MPN") "TCAN330GDCNT"))
      (libsource (lib "eagle-import") (part "TCAN330"))
    )
    (comp (ref "U17")
      (value "25AAXX")
      (footprint "eagle-import:SOIC8")
      (fields (field (name "MPN") "25AA02E48T-I/SN"))
      (libsource (lib "eagle-import") (part "25AAXX"))
    )
    (comp (ref "C32")
      (value "1uF")
      (footprint "eagle-import:.0805-B-NOSILK")
      (libsource (lib "eagle-import") (part "C-EU0805-B-NOSILK"))
    )
    (comp (ref "C33")
      (value "1uF")
      (footprint "eagle-import:.0603-A")
      (fields (field (name "MFR") "Samsung") (field (name "MPN") "CL05B104KO5NNNC"))
      (libsource (lib "eagle-import") (part "C-EU0603-A"))
    )
    (comp (ref "C34")
      (value "1uF")
      (footprint "eagle-import:.0603-A")
      (libsource (lib "eagle-import") (part "C-EU0603-A"))
    )
    (comp (ref "C35")
      (value "1uF")
      (footprint "eagle-import:.0805-B-NOSILK")
      (libsource (lib "eagle-import") (part "C-EU0805-B-NOSILK"))
    )
    (comp (ref "C36")
      (value "22uF")
      (footprint "eagle-import:C1210")
      (libsource (lib "eagle-import") (part "C-EUC1210"))
    )
    (comp (ref "C37")
      (value "1uF")
      (footprint "eagle-import:.0603-A")
      (libsource (lib "eagle-import") (part "C-EU0603-A"))
    )
    (comp (ref "C38")
      (value "10uF")
      (footprint "eagle-import:.0805-B")
      (libsource (lib "eagle-import") (part "C-EU0805-B"))
    )
    (comp (ref "C39")
      (value "0.1uF")
      (footprint "eagle-import:.0603-A")
      (libsource (lib "eagle-import") (part "C-EU0603-A"))
    )
    (comp (ref "C44")
      (value "10uF")
      (footprint "eagle-import:.0805-B")
      (libsource (lib "eagle-import") (part "C-EU0805-B"))
    )
    (comp (ref "D6")
      (value "AMBER")
      (footprint "eagle-import:LED-0603")
      (libsource (lib "eagle-import") (part "SparkFun-LED_529_LED-GREEN0603"))
    )
    (comp (ref "D7")
      (value "GREEN")
      (footprint "eagle-import:LED-0603")
      (libsource (lib "eagle-import") (part "LED-GREEN0603"))
    )
    (comp (ref "D8")
      (value "GREEN")
      (footprint "eagle-import:LED-0603")
      (libsource (lib "eagle-import") (part "LED-GREEN0603"))
    )
    (comp (ref "JP3")
      (value "JUMPER-SMT_2_NO_SILK")
      (footprint "eagle-import:SMT-JUMPER_2_NO_SILK")
      (libsource (lib "eagle-import") (part "JUMPER-SMT_2_NO_SILK"))
    )
    (comp (ref "L1")
      (value "6.8u")
      (footprint "eagle-import:ECS-MPI4040")
      (fields (field (name "MPN") "ECS-MPI4040R4-6R8-R"))
      (libsource (lib "eagle-import") (part "L-ECS-MPI4040"))
    )
    (comp (ref "Q2")
      (value "PMV45EN")
      (footprint "eagle-import:SOT23")
      (fields (field (name "MPN") "PMV45EN2R"))
      (libsource (lib "eagle-import") (part "PMV45EN"))
    )
    (comp (ref "Q3")
      (value "DMP2240UDM")
      (footprint "eagle-import:SOT23-6")
      (fields (field (name "MFR") "Diodes Inc") (field (name "MPN") "DMP2240UDM-7"))
      (libsource (lib "eagle-import") (part "Q-MOSFET-PCH-dual-SOT23-6_MOSFET-PCH-SOT23-6"))
    )
    (comp (ref "Q4")
      (value "PMV45EN")
      (footprint "eagle-import:SOT23")
      (fields (field (name "MPN") "PMV45EN2R"))
      (libsource (lib "eagle-import") (part "PMV45EN"))
    )
    (comp (ref "Q5")
      (value "MOSFET-PCH-SOT23-6")
      (footprint "eagle-import:SOT23-6")
      (fields (field (name "MPN") "DMP3050LVT-7") (field (name "MPN_1") "DMP3050LVT-7"))
      (libsource (lib "eagle-import") (part "MOSFET-PCH-SOT23-6"))
    )
    (comp (ref "Q6")
      (value "MOSFET-PCH-SOT23-6")
      (footprint "eagle-import:SOT23-6")
      (fields (field (name "MPN") "DMP3050LVT-7") (field (name "MPN_1") "DMP3050LVT-7"))
      (libsource (lib "eagle-import") (part "MOSFET-PCH-SOT23-6"))
    )
    (comp (ref "R32")
      (value "10k")
      (footprint "eagle-import:.0603-A")
      (libsource (lib "eagle-import") (part "R-US_0603-A"))
    )
    (comp (ref "R33")
      (value "100k")
      (footprint "eagle-import:.0603-A")
      (fields (field (name "MFR") "Samsung") (field (name "MPN") "RC1005F6653CS"))
      (libsource (lib "eagle-import") (part "R-US_0603-A"))
    )
    (comp (ref "R34")
      (value "10k")
      (footprint "eagle-import:.0603-A")
      (libsource (lib "eagle-import") (part "R-US_0603-A"))
    )
    (comp (ref "R35")
      (value "665k")
      (footprint "eagle-import:.0603-A")
      (libsource (lib "eagle-import") (part "R-US_0603-A"))
    )
    (comp (ref "R36")
      (value "1M")
      (footprint "eagle-import:.0603-A")
      (libsource (lib "eagle-import") (part "R-US_0603-A"))
    )
    (comp (ref "R37")
      (value "330k")
      (footprint "eagle-import:.0603-A")
      (libsource (lib "eagle-import") (part "R-US_0603-A"))
    )
    (comp (ref "R38")
      (value "10k")
      (footprint "eagle-import:.0603-A")
      (fields (field (name "MFR") "Samsung") (field (name "MPN") "RC1005F6653CS"))
      (libsource (lib "eagle-import") (part "R-US_0603-A"))
    )
    (comp (ref "R39")
      (value "10k")
      (footprint "eagle-import:.0603-A")
      (libsource (lib "eagle-import") (part "R-US_0603-A"))
    )
    (comp (ref "R40")
      (value "NP")
      (footprint "eagle-import:.0603-A")
      (fields (field (name "MFR") "Samsung") (field (name "MPN") "RC1005F6653CS"))
      (libsource (lib "eagle-import") (part "R-US_0603-A"))
    )
    (comp (ref "R41")
      (value "100")
      (footprint "eagle-import:.0603-A")
      (libsource (lib "eagle-import") (part "R-US_0603-A"))
    )
    (comp (ref "R42")
      (value "NP")
      (footprint "eagle-import:.0603-A")
      (fields (field (name "MFR") "Samsung") (field (name "MPN") "RC1005F6653CS"))
      (libsource (lib "eagle-import") (part "R-US_0603-A"))
    )
    (comp (ref "R43")
      (value "665k")
      (footprint "eagle-import:.0603-A")
      (libsource (lib "eagle-import") (part "R-US_0603-A"))
    )
    (comp (ref "R44")
      (value "1M")
      (footprint "eagle-import:.0603-A")
      (libsource (lib "eagle-import") (part "R-US_0603-A"))
    )
    (comp (ref "R45")
      (value "330k")
      (footprint "eagle-import:.0603-A")
      (libsource (lib "eagle-import") (part "R-US_0603-A"))
    )
    (comp (ref "R46")
      (value "10k")
      (footprint "eagle-import:.0603-A")
      (libsource (lib "eagle-import") (part "R-US_0603-A"))
    )
    (comp (ref "R47")
      (value "0")
      (footprint "eagle-import:.0603-A")
      (libsource (lib "eagle-import") (part "R-US_0603-A"))
    )
    (comp (ref "R48")
      (value "100")
      (footprint "eagle-import:.0603-A")
      (libsource (lib "eagle-import") (part "R-US_0603-A"))
    )
    (comp (ref "R49")
      (value "2.7k")
      (footprint "eagle-import:.0603-A")
      (libsource (lib "eagle-import") (part "R-US_0603-A"))
    )
    (comp (ref "R50")
      (value "10k")
      (footprint "eagle-import:.0603-A")
      (libsource (lib "eagle-import") (part "R-US_0603-A"))
    )
    (comp (ref "R51")
      (value "4.7k")
      (footprint "eagle-import:.0603-A")
      (fields (field (name "MFR") "Samsung") (field (name "MPN") "RC1005F6653CS"))
      (libsource (lib "eagle-import") (part "R-US_0603-A"))
    )
    (comp (ref "R52")
      (value "10k")
      (footprint "eagle-import:.0603-A")
      (libsource (lib "eagle-import") (part "R-US_0603-A"))
    )
    (comp (ref "R53")
      (value "NP")
      (footprint "eagle-import:.0603-A")
      (fields (field (name "MFR") "Samsung") (field (name "MPN") "RC1005F6653CS"))
      (libsource (lib "eagle-import") (part "R-US_0603-A"))
    )
    (comp (ref "R54")
      (value "NP")
      (footprint "eagle-import:.0603-A")
      (fields (field (name "MFR") "Samsung") (field (name "MPN") "RC1005F6653CS"))
      (libsource (lib "eagle-import") (part "R-US_0603-A"))
    )
    (comp (ref "R55")
      (value "NP")
      (footprint "eagle-import:.0603-A")
      (fields (field (name "MFR") "Samsung") (field (name "MPN") "RC1005F6653CS"))
      (libsource (lib "eagle-import") (part "R-US_0603-A"))
    )
    (comp (ref "R56")
      (value "NP")
      (footprint "eagle-import:.0603-A")
      (fields (field (name "MFR") "Samsung") (field (name "MPN") "RC1005F6653CS"))
      (libsource (lib "eagle-import") (part "R-US_0603-A"))
    )
    (comp (ref "R57")
      (value "NP")
      (footprint "eagle-import:.0603-A")
      (fields (field (name "MFR") "Samsung") (field (name "MPN") "RC1005F6653CS"))
      (libsource (lib "eagle-import") (part "R-US_0603-A"))
    )
    (comp (ref "R58")
      (value "NP")
      (footprint "eagle-import:.0603-A")
      (fields (field (name "MFR") "Samsung") (field (name "MPN") "RC1005F6653CS"))
      (libsource (lib "eagle-import") (part "R-US_0603-A"))
    )
    (comp (ref "R61")
      (value "2.7k")
      (footprint "eagle-import:.0603-A")
      (libsource (lib "eagle-import") (part "R-US_0603-A"))
    )
    (comp (ref "R62")
      (value "2.7k")
      (footprint "eagle-import:.0603-A")
      (libsource (lib "eagle-import") (part "R-US_0603-A"))
    )
    (comp (ref "R63")
      (value "100m")
      (footprint "eagle-import:R1206")
      (libsource (lib "eagle-import") (part "rcl_334_R-US_R1206"))
    )
    (comp (ref "R64")
      (value "10k")
      (footprint "eagle-import:.0603-A")
      (libsource (lib "eagle-import") (part "R-US_0603-A"))
    )
    (comp (ref "R65")
      (value "NP")
      (footprint "eagle-import:.0603-A")
      (fields (field (name "MFR") "Samsung") (field (name "MPN") "RC1005F6653CS"))
      (libsource (lib "eagle-import") (part "R-US_0603-A"))
    )
    (comp (ref "R66")
      (value "NP")
      (footprint "eagle-import:.0603-A")
      (fields (field (name "MFR") "Samsung") (field (name "MPN") "RC1005F6653CS"))
      (libsource (lib "eagle-import") (part "R-US_0603-A"))
    )
    (comp (ref "R67")
      (value "NP")
      (footprint "eagle-import:.0603-A")
      (fields (field (name "MFR") "Samsung") (field (name "MPN") "RC1005F6653CS"))
      (libsource (lib "eagle-import") (part "R-US_0603-A"))
    )
    (comp (ref "R68")
      (value "NP")
      (footprint "eagle-import:.0603-A")
      (fields (field (name "MFR") "Samsung") (field (name "MPN") "RC1005F6653CS"))
      (libsource (lib "eagle-import") (part "R-US_0603-A"))
    )
    (comp (ref "R69")
      (value "NP")
      (footprint "eagle-import:.0603-A")
      (fields (field (name "MFR") "Samsung") (field (name "MPN") "RC1005F6653CS"))
      (libsource (lib "eagle-import") (part "R-US_0603-A"))
    )
    (comp (ref "R70")
      (value "NP")
      (footprint "eagle-import:.0603-A")
      (fields (field (name "MFR") "Samsung") (field (name "MPN") "RC1005F6653CS"))
      (libsource (lib "eagle-import") (part "R-US_0603-A"))
    )
    (comp (ref "R71")
      (value "100")
      (footprint "eagle-import:.0603-A")
      (libsource (lib "eagle-import") (part "R-US_0603-A"))
    )
    (comp (ref "R72")
      (value "10k")
      (footprint "eagle-import:.0603-A")
      (libsource (lib "eagle-import") (part "R-US_0603-A"))
    )
    (comp (ref "TP41")
      (value "TEST-POINT")
      (footprint "eagle-import:2MM-TEST-POINT")
      (libsource (lib "eagle-import") (part "TEST-POINT"))
    )
    (comp (ref "TP42")
      (value "TEST-POINT")
      (footprint "eagle-import:2MM-TEST-POINT")
      (libsource (lib "eagle-import") (part "TEST-POINT"))
    )
    (comp (ref "TP43")
      (value "TEST-POINT")
      (footprint "eagle-import:2MM-TEST-POINT")
      (libsource (lib "eagle-import") (part "TEST-POINT"))
    )
    (comp (ref "TP44")
      (value "TEST-POINT")
      (footprint "eagle-import:2MM-TEST-POINT")
      (libsource (lib "eagle-import") (part "TEST-POINT"))
    )
    (comp (ref "TP45")
      (value "TEST-POINT")
      (footprint "eagle-import:2MM-TEST-POINT")
      (libsource (lib "eagle-import") (part "TEST-POINT"))
    )
    (comp (ref "TP46")
      (value "TEST-POINT")
      (footprint "eagle-import:2MM-TEST-POINT")
      (libsource (lib "eagle-import") (part "TEST-POINT"))
    )
    (comp (ref "TP47")
      (value "TEST-POINT")
      (footprint "eagle-import:2MM-TEST-POINT")
      (libsource (lib "eagle-import") (part "TEST-POINT"))
    )
    (comp (ref "TP48")
      (value "TEST-POINT")
      (footprint "eagle-import:2MM-TEST-POINT")
      (libsource (lib "eagle-import") (part "TEST-POINT"))
    )
    (comp (ref "TP49")
      (value "TEST-POINT")
      (footprint "eagle-import:2MM-TEST-POINT")
      (libsource (lib "eagle-import") (part "TEST-POINT"))
    )
    (comp (ref "TP50")
      (value "TEST-POINT")
      (footprint "eagle-import:2MM-TEST-POINT")
      (libsource (lib "eagle-import") (part "TEST-POINT"))
    )
    (comp (ref "TP51")
      (value "TEST-POINT")
      (footprint "eagle-import:2MM-TEST-POINT")
      (libsource (lib "eagle-import") (part "TEST-POINT"))
    )
    (comp (ref "TP52")
      (value "TEST-POINT")
      (footprint "eagle-import:2MM-TEST-POINT")
      (libsource (lib "eagle-import") (part "TEST-POINT"))
    )
    (comp (ref "TP53")
      (value "TEST-POINT")
      (footprint "eagle-import:2MM-TEST-POINT")
      (libsource (lib "eagle-import") (part "TEST-POINT"))
    )
    (comp (ref "TP54")
      (value "TEST-POINT")
      (footprint "eagle-import:2MM-TEST-POINT")
      (libsource (lib "eagle-import") (part "TEST-POINT"))
    )
    (comp (ref "TP55")
      (value "TEST-POINT")
      (footprint "eagle-import:2MM-TEST-POINT")
      (libsource (lib "eagle-import") (part "TEST-POINT"))
    )
    (comp (ref "TP56")
      (value "TEST-POINT")
      (footprint "eagle-import:2MM-TEST-POINT")
      (libsource (lib "eagle-import") (part "TEST-POINT"))
    )
    (comp (ref "TP57")
      (value "TEST-POINT")
      (footprint "eagle-import:2MM-TEST-POINT")
      (libsource (lib "eagle-import") (part "TEST-POINT"))
    )
    (comp (ref "TP63")
      (value "TEST-POINT")
      (footprint "eagle-import:2MM-TEST-POINT")
      (libsource (lib "eagle-import") (part "TEST-POINT"))
    )
    (comp (ref "TP64")
      (value "TEST-POINT")
      (footprint "eagle-import:2MM-TEST-POINT")
      (libsource (lib "eagle-import") (part "TEST-POINT"))
    )
    (comp (ref "TP65")
      (value "TEST-POINT")
      (footprint "eagle-import:2MM-TEST-POINT")
      (libsource (lib "eagle-import") (part "TEST-POINT"))
    )
    (comp (ref "TP66")
      (value "TEST-POINT")
      (footprint "eagle-import:2MM-TEST-POINT")
      (libsource (lib "eagle-import") (part "TEST-POINT"))
    )
    (comp (ref "TP67")
      (value "TEST-POINT")
      (footprint "eagle-import:2MM-TEST-POINT")
      (libsource (lib "eagle-import") (part "TEST-POINT"))
    )
    (comp (ref "TP68")
      (value "TEST-POINT")
      (footprint "eagle-import:2MM-TEST-POINT")
      (libsource (lib "eagle-import") (part "TEST-POINT"))
    )
    (comp (ref "TP72")
      (value "TEST-POINT")
      (footprint "eagle-import:2MM-TEST-POINT")
      (libsource (lib "eagle-import") (part "TEST-POINT"))
    )
    (comp (ref "TP74")
      (value "TEST-POINT")
      (footprint "eagle-import:2MM-TEST-POINT")
      (libsource (lib "eagle-import") (part "TEST-POINT"))
    )
    (comp (ref "TP75")
      (value "TEST-POINT")
      (footprint "eagle-import:2MM-TEST-POINT")
      (libsource (lib "eagle-import") (part "TEST-POINT"))
    )
    (comp (ref "TP77")
      (value "TEST-POINT")
      (footprint "eagle-import:2MM-TEST-POINT")
      (libsource (lib "eagle-import") (part "TEST-POINT"))
    )
    (comp (ref "TP78")
      (value "TEST-POINT")
      (footprint "eagle-import:2MM-TEST-POINT")
      (libsource (lib "eagle-import") (part "TEST-POINT"))
    )
    (comp (ref "U12")
      (value "MIC842LYC5")
      (footprint "eagle-import:SC70-5")
      (libsource (lib "eagle-import") (part "MIC842LYC5"))
    )
    (comp (ref "U13")
      (value "MIC842LYC5")
      (footprint "eagle-import:SC70-5")
      (libsource (lib "eagle-import") (part "MIC842LYC5"))
    )
    (comp (ref "U14")
      (value "MAX4211FETE")
      (footprint "eagle-import:QFN65P400X400X80-17T210")
      (fields (field (name "MPN") "MAX4211FETE+"))
      (libsource (lib "eagle-import") (part "MAX4211"))
    )
    (comp (ref "U15")
      (value "TPS62112")
      (footprint "eagle-import:S-PVQFN-16")
      (fields (field (name "MPN") "TPS62112RSAR"))
      (libsource (lib "eagle-import") (part "TPS6211X"))
    )
    (comp (ref "U16")
      (value "MAX7310ATE")
      (footprint "eagle-import:QFN65P400X400X80-17T210")
      (fields
        (field (name "MPN") "MAX7310ATE+")
        (field (name "MFR") "Maxim")
        (field (name "MPN_1") "MAX7310ATE")
      )
      (libsource (lib "eagle-import") (part "MAX7310"))
    )
    (comp (ref "C19")
      (value "18pF, 50V")
      (footprint "eagle-import:.0603-A")
      (libsource (lib "eagle-import") (part "C-EU0603-A"))
    )
    (comp (ref "C22")
      (value "18pF, 50V")
      (footprint "eagle-import:.0603-A")
      (libsource (lib "eagle-import") (part "C-EU0603-A"))
    )
    (comp (ref "C29")
      (value "18pF, 50V")
      (footprint "eagle-import:.0603-A")
      (libsource (lib "eagle-import") (part "C-EU0603-A"))
    )
    (comp (ref "C30")
      (value "18pF, 50V")
      (footprint "eagle-import:.0603-A")
      (libsource (lib "eagle-import") (part "C-EU0603-A"))
    )
    (comp (ref "C50")
      (value "0.1uF")
      (footprint "eagle-import:.0603-A")
      (libsource (lib "eagle-import") (part "C-EU0603-A"))
    )
    (comp (ref "C51")
      (value "0.1u")
      (footprint "eagle-import:.0603-A")
      (libsource (lib "eagle-import") (part "C-EU0603-A"))
    )
    (comp (ref "FB2")
      (value "30Ω/1.8A")
      (footprint "eagle-import:0603")
      (fields (field (name "MPN") "BLM18KG300JH1D"))
      (libsource (lib "eagle-import") (part "FERRITE_BEAD-0603"))
    )
    (comp (ref "R13")
      (value "1M")
      (footprint "eagle-import:.0603-A")
      (libsource (lib "eagle-import") (part "R-US_0603-A"))
    )
    (comp (ref "R21")
      (value "10k")
      (footprint "eagle-import:.0603-A")
      (libsource (lib "eagle-import") (part "R-US_0603-A"))
    )
    (comp (ref "R27")
      (value "DNP")
      (footprint "eagle-import:.0603-A")
      (libsource (lib "eagle-import") (part "R-US_0603-A"))
    )
    (comp (ref "TP5")
      (value "TEST-POINT3X4")
      (footprint "eagle-import:PAD.03X.04")
      (libsource (lib "eagle-import") (part "TEST-POINT3X4"))
    )
    (comp (ref "TP6")
      (value "TEST-POINT3X4")
      (footprint "eagle-import:PAD.03X.04")
      (libsource (lib "eagle-import") (part "TEST-POINT3X4"))
    )
    (comp (ref "TP7")
      (value "TEST-POINT3X4")
      (footprint "eagle-import:PAD.03X.04")
      (libsource (lib "eagle-import") (part "TEST-POINT3X4"))
    )
    (comp (ref "TP8")
      (value "TEST-POINT3X4")
      (footprint "eagle-import:PAD.03X.04")
      (libsource (lib "eagle-import") (part "TEST-POINT3X4"))
    )
    (comp (ref "TP9")
      (value "TEST-POINT3X4")
      (footprint "eagle-import:PAD.03X.04")
      (libsource (lib "eagle-import") (part "TEST-POINT3X4"))
    )
    (comp (ref "TP10")
      (value "TEST-POINT3X4")
      (footprint "eagle-import:PAD.03X.04")
      (libsource (lib "eagle-import") (part "TEST-POINT3X4"))
    )
    (comp (ref "TP11")
      (value "TEST-POINT3X4")
      (footprint "eagle-import:PAD.03X.04")
      (libsource (lib "eagle-import") (part "TEST-POINT3X4"))
    )
    (comp (ref "TP12")
      (value "TEST-POINT3X4")
      (footprint "eagle-import:PAD.03X.04")
      (libsource (lib "eagle-import") (part "TEST-POINT3X4"))
    )
    (comp (ref "TP15")
      (value "TEST-POINT3X4")
      (footprint "eagle-import:PAD.03X.04")
      (libsource (lib "eagle-import") (part "TEST-POINT3X4"))
    )
    (comp (ref "TP16")
      (value "TEST-POINT3X4")
      (footprint "eagle-import:PAD.03X.04")
      (libsource (lib "eagle-import") (part "TEST-POINT3X4"))
    )
    (comp (ref "TP17")
      (value "TEST-POINT3X4")
      (footprint "eagle-import:PAD.03X.04")
      (libsource (lib "eagle-import") (part "TEST-POINT3X4"))
    )
    (comp (ref "TP36")
      (value "TEST-POINT3X4")
      (footprint "eagle-import:PAD.03X.04")
      (libsource (lib "eagle-import") (part "TEST-POINT3X4"))
    )
    (comp (ref "TP37")
      (value "TEST-POINT3X4")
      (footprint "eagle-import:PAD.03X.04")
      (libsource (lib "eagle-import") (part "TEST-POINT3X4"))
    )
    (comp (ref "TP38")
      (value "TEST-POINT3X4")
      (footprint "eagle-import:PAD.03X.04")
      (libsource (lib "eagle-import") (part "TEST-POINT3X4"))
    )
    (comp (ref "TP133")
      (value "TEST-POINT3X4")
      (footprint "eagle-import:PAD.03X.04")
      (libsource (lib "eagle-import") (part "TEST-POINT3X4"))
    )
    (comp (ref "TP138")
      (value "TEST-POINT3X4")
      (footprint "eagle-import:PAD.03X.04")
      (libsource (lib "eagle-import") (part "TEST-POINT3X4"))
    )
    (comp (ref "TP139")
      (value "TEST-POINT3X4")
      (footprint "eagle-import:PAD.03X.04")
      (libsource (lib "eagle-import") (part "TEST-POINT3X4"))
    )
    (comp (ref "TP141")
      (value "TEST-POINT3X4")
      (footprint "eagle-import:PAD.03X.04")
      (libsource (lib "eagle-import") (part "TEST-POINT3X4"))
    )
    (comp (ref "TP144")
      (value "TEST-POINT3X4")
      (footprint "eagle-import:PAD.03X.04")
      (libsource (lib "eagle-import") (part "TEST-POINT3X4"))
    )
    (comp (ref "TP168")
      (value "TEST-POINT3X4")
      (footprint "eagle-import:PAD.03X.04")
      (libsource (lib "eagle-import") (part "TEST-POINT3X4"))
    )
    (comp (ref "Y1")
      (value "24MHz")
      (footprint "eagle-import:5X3.2-4SMD")
      (fields (field (name "MPN") "ECS-240-12-30BQ-AEN-TR"))
      (libsource (lib "eagle-import") (part "ECS-240-12-30BQ-AEN-TR"))
    )
    (comp (ref "Y2")
      (value "ABS07-32.768KHZ-T")
      (footprint "eagle-import:CRYSTAL_3.2X1.5")
      (libsource (lib "eagle-import") (part "ABS07-32.768KHZ-T"))
    )
    (comp (ref "C13")
      (value "22uF")
      (footprint "eagle-import:C1210")
      (libsource (lib "eagle-import") (part "C-EUC1210"))
    )
    (comp (ref "C14")
      (value "22uF")
      (footprint "eagle-import:C1210")
      (libsource (lib "eagle-import") (part "C-EUC1210"))
    )
    (comp (ref "C18")
      (value "0.1uF")
      (footprint "eagle-import:.0603-A")
      (libsource (lib "eagle-import") (part "C-EU0603-A"))
    )
    (comp (ref "D1")
      (value "GREEN")
      (footprint "eagle-import:LED-0603")
      (libsource (lib "eagle-import") (part "LED-GREEN0603"))
    )
    (comp (ref "Q1")
      (value "MMBT2907")
      (footprint "eagle-import:SOT23-BEC")
      (fields (field (name "MPN") "MMBT2907A-7-F"))
      (libsource (lib "eagle-import") (part "MMBT2907SMD"))
    )
    (comp (ref "R1")
      (value "1k")
      (footprint "eagle-import:.0603-A")
      (libsource (lib "eagle-import") (part "R-US_0603-A"))
    )
    (comp (ref "R15")
      (value "10k")
      (footprint "eagle-import:.0603-A")
      (libsource (lib "eagle-import") (part "R-US_0603-A"))
    )
    (comp (ref "R23")
      (value "499")
      (footprint "eagle-import:.0603-A")
      (libsource (lib "eagle-import") (part "R-US_0603-A"))
    )
    (comp (ref "R28")
      (value "10k")
      (footprint "eagle-import:.0603-A")
      (libsource (lib "eagle-import") (part "R-US_0603-A"))
    )
    (comp (ref "R31")
      (value "40.2K")
      (footprint "eagle-import:.0603-A")
      (libsource (lib "eagle-import") (part "R-US_0603-A"))
    )
    (comp (ref "R73")
      (value "100")
      (footprint "eagle-import:.0603-A")
      (libsource (lib "eagle-import") (part "R-US_0603-A"))
    )
    (comp (ref "R74")
      (value "100")
      (footprint "eagle-import:.0603-A")
      (libsource (lib "eagle-import") (part "R-US_0603-A"))
    )
    (comp (ref "R75")
      (value "100")
      (footprint "eagle-import:.0603-A")
      (libsource (lib "eagle-import") (part "R-US_0603-A"))
    )
    (comp (ref "TP2")
      (value "TEST-POINT")
      (footprint "eagle-import:2MM-TEST-POINT")
      (libsource (lib "eagle-import") (part "TEST-POINT"))
    )
    (comp (ref "TP3")
      (value "TEST-POINT3X4")
      (footprint "eagle-import:PAD.03X.04")
      (libsource (lib "eagle-import") (part "TEST-POINT3X4"))
    )
    (comp (ref "TP14")
      (value "TEST-POINT3X4")
      (footprint "eagle-import:PAD.03X.04")
      (libsource (lib "eagle-import") (part "TEST-POINT3X4"))
    )
    (comp (ref "TP39")
      (value "TEST-POINT")
      (footprint "eagle-import:2MM-TEST-POINT")
      (libsource (lib "eagle-import") (part "TEST-POINT"))
    )
    (comp (ref "TP70")
      (value "TEST-POINT")
      (footprint "eagle-import:2MM-TEST-POINT")
      (libsource (lib "eagle-import") (part "TEST-POINT"))
    )
    (comp (ref "TP71")
      (value "TEST-POINT")
      (footprint "eagle-import:2MM-TEST-POINT")
      (libsource (lib "eagle-import") (part "TEST-POINT"))
    )
    (comp (ref "TP102")
      (value "TEST-POINT3X4")
      (footprint "eagle-import:PAD.03X.04")
      (libsource (lib "eagle-import") (part "TEST-POINT3X4"))
    )
    (comp (ref "TP109")
      (value "TEST-POINT3X4")
      (footprint "eagle-import:PAD.03X.04")
      (libsource (lib "eagle-import") (part "TEST-POINT3X4"))
    )
    (comp (ref "TP110")
      (value "TEST-POINT3X4")
      (footprint "eagle-import:PAD.03X.04")
      (libsource (lib "eagle-import") (part "TEST-POINT3X4"))
    )
    (comp (ref "TP121")
      (value "TEST-POINT3X4")
      (footprint "eagle-import:PAD.03X.04")
      (libsource (lib "eagle-import") (part "TEST-POINT3X4"))
    )
    (comp (ref "TP129")
      (value "TEST-POINT3X4")
      (footprint "eagle-import:PAD.03X.04")
      (libsource (lib "eagle-import") (part "TEST-POINT3X4"))
    )
    (comp (ref "TP130")
      (value "TEST-POINT3X4")
      (footprint "eagle-import:PAD.03X.04")
      (libsource (lib "eagle-import") (part "TEST-POINT3X4"))
    )
    (comp (ref "TP132")
      (value "TEST-POINT3X4")
      (footprint "eagle-import:PAD.03X.04")
      (libsource (lib "eagle-import") (part "TEST-POINT3X4"))
    )
    (comp (ref "TP136")
      (value "TEST-POINT3X4")
      (footprint "eagle-import:PAD.03X.04")
      (libsource (lib "eagle-import") (part "TEST-POINT3X4"))
    )
    (comp (ref "TP140")
      (value "TEST-POINT3X4")
      (footprint "eagle-import:PAD.03X.04")
      (libsource (lib "eagle-import") (part "TEST-POINT3X4"))
    )
    (comp (ref "TP154")
      (value "TEST-POINT3X4")
      (footprint "eagle-import:PAD.03X.04")
      (libsource (lib "eagle-import") (part "TEST-POINT3X4"))
    )
    (comp (ref "TP156")
      (value "TEST-POINT3X4")
      (footprint "eagle-import:PAD.03X.04")
      (libsource (lib "eagle-import") (part "TEST-POINT3X4"))
    )
    (comp (ref "TP157")
      (value "TEST-POINT3X4")
      (footprint "eagle-import:PAD.03X.04")
      (libsource (lib "eagle-import") (part "TEST-POINT3X4"))
    )
    (comp (ref "TP160")
      (value "TEST-POINT3X4")
      (footprint "eagle-import:PAD.03X.04")
      (libsource (lib "eagle-import") (part "TEST-POINT3X4"))
    )
    (comp (ref "TP161")
      (value "TEST-POINT3X4")
      (footprint "eagle-import:PAD.03X.04")
      (libsource (lib "eagle-import") (part "TEST-POINT3X4"))
    )
    (comp (ref "TP163")
      (value "TEST-POINT3X4")
      (footprint "eagle-import:PAD.03X.04")
      (libsource (lib "eagle-import") (part "TEST-POINT3X4"))
    )
    (comp (ref "TP164")
      (value "TEST-POINT3X4")
      (footprint "eagle-import:PAD.03X.04")
      (libsource (lib "eagle-import") (part "TEST-POINT3X4"))
    )
    (comp (ref "TP165")
      (value "TEST-POINT3X4")
      (footprint "eagle-import:PAD.03X.04")
      (libsource (lib "eagle-import") (part "TEST-POINT3X4"))
    )
    (comp (ref "TP166")
      (value "TEST-POINT3X4")
      (footprint "eagle-import:PAD.03X.04")
      (libsource (lib "eagle-import") (part "TEST-POINT3X4"))
    )
    (comp (ref "TP167")
      (value "TEST-POINT3X4")
      (footprint "eagle-import:PAD.03X.04")
      (libsource (lib "eagle-import") (part "TEST-POINT3X4"))
    )
    (comp (ref "TP173")
      (value "TEST-POINT3X4")
      (footprint "eagle-import:PAD.03X.04")
      (libsource (lib "eagle-import") (part "TEST-POINT3X4"))
    )
    (comp (ref "U4")
      (value "SN74LVC1G07DCK")
      (footprint "eagle-import:C70(TI-DCK)")
      (fields (field (name "MPN") "SN74LVC1G07DCKR"))
      (libsource (lib "eagle-import") (part "SN74LVC1G07DCK"))
    )
    (comp (ref "U10")
      (value "TLVH431")
      (footprint "eagle-import:SOT23-3")
      (fields (field (name "MPN") "TLVH431BQDBZRQ1"))
      (libsource (lib "eagle-import") (part "TLVH431"))
    )
  )
  (nets
    (net (code "5") (name "1.8V-A") (class "Default")
      (node (ref "C50") (pin "1") (pinfunction "1_1") (pintype "passive"))
      (node (ref "R21") (pin "2") (pinfunction "2_2") (pintype "passive"))
      (node (ref "U7") (pin "A7") (pinfunction "SYS_ADC_1P8V_A7") (pintype "bidirectional"))
      (node (ref "U7") (pin "B7") (pinfunction "VREFP_B7") (pintype "bidirectional"))
    )
    (net (code "6") (name "3.3V") (class "Default")
      (node (ref "C1") (pin "1") (pinfunction "1_1") (pintype "passive"))
      (node (ref "C11") (pin "1") (pinfunction "1_1") (pintype "passive"))
      (node (ref "C16") (pin "1") (pinfunction "1_1") (pintype "passive"))
      (node (ref "C17") (pin "1") (pinfunction "1_1") (pintype "passive"))
      (node (ref "C2") (pin "1") (pinfunction "1_1") (pintype "passive"))
      (node (ref "C20") (pin "1") (pinfunction "1_1") (pintype "passive"))
      (node (ref "C21") (pin "1") (pinfunction "1_1") (pintype "passive"))
      (node (ref "C23") (pin "1") (pinfunction "1_1") (pintype "passive"))
      (node (ref "C24") (pin "1") (pinfunction "1_1") (pintype "passive"))
      (node (ref "C25") (pin "1") (pinfunction "1_1") (pintype "passive"))
      (node (ref "C26") (pin "1") (pinfunction "1_1") (pintype "passive"))
      (node (ref "C27") (pin "1") (pinfunction "1_1") (pintype "passive"))
      (node (ref "C28") (pin "1") (pinfunction "1_1") (pintype "passive"))
      (node (ref "C3") (pin "1") (pinfunction "1_1") (pintype "passive"))
      (node (ref "C31") (pin "2") (pinfunction "2_2") (pintype "passive"))
      (node (ref "C40") (pin "2") (pinfunction "2_2") (pintype "passive"))
      (node (ref "C42") (pin "1") (pinfunction "1_1") (pintype "passive"))
      (node (ref "C43") (pin "1") (pinfunction "1_1") (pintype "passive"))
      (node (ref "C45") (pin "1") (pinfunction "1_1") (pintype "passive"))
      (node (ref "C46") (pin "1") (pinfunction "1_1") (pintype "passive"))
      (node (ref "C47") (pin "1") (pinfunction "1_1") (pintype "passive"))
      (node (ref "C48") (pin "1") (pinfunction "1_1") (pintype "passive"))
      (node (ref "C49") (pin "1") (pinfunction "1_1") (pintype "passive"))
      (node (ref "C5") (pin "1") (pinfunction "1_1") (pintype "passive"))
      (node (ref "C6") (pin "1") (pinfunction "1_1") (pintype "passive"))
      (node (ref "C7") (pin "1") (pinfunction "1_1") (pintype "passive"))
      (node (ref "C8") (pin "1") (pinfunction "1_1") (pintype "passive"))
      (node (ref "C9") (pin "1") (pinfunction "1_1") (pintype "passive"))
      (node (ref "J100") (pin "4") (pinfunction "VDD_4") (pintype "bidirectional"))
      (node (ref "J3") (pin "1") (pinfunction "1_1") (pintype "passive"))
      (node (ref "JP1") (pin "1") (pinfunction "1_1") (pintype "passive"))
      (node (ref "R1") (pin "1") (pinfunction "1_1") (pintype "passive"))
      (node (ref "R10") (pin "10") (pinfunction "55_10") (pintype "passive"))
      (node (ref "R10") (pin "5") (pinfunction "55_5") (pintype "passive"))
      (node (ref "R17") (pin "5") (pinfunction "5_5") (pintype "passive"))
      (node (ref "R17") (pin "6") (pinfunction "6_6") (pintype "passive"))
      (node (ref "R17") (pin "7") (pinfunction "7_7") (pintype "passive"))
      (node (ref "R17") (pin "8") (pinfunction "8_8") (pintype "passive"))
      (node (ref "R60") (pin "1") (pinfunction "1_1") (pintype "passive"))
      (node (ref "R8") (pin "10") (pinfunction "55_10") (pintype "passive"))
      (node (ref "R8") (pin "5") (pinfunction "55_5") (pintype "passive"))
      (node (ref "R9") (pin "10") (pinfunction "55_10") (pintype "passive"))
      (node (ref "R9") (pin "5") (pinfunction "55_5") (pintype "passive"))
      (node (ref "TP2") (pin "1") (pinfunction "1_1") (pintype "passive"))
      (node (ref "U11") (pin "3") (pinfunction "VCC_3") (pintype "power_in"))
      (node (ref "U17") (pin "8") (pinfunction "VCC_8") (pintype "power_in"))
      (node (ref "U2") (pin "12") (pinfunction "LVDS_VCC_12") (pintype "power_in"))
      (node (ref "U2") (pin "20") (pinfunction "PLL_VCC_20") (pintype "power_in"))
      (node (ref "U2") (pin "28") (pinfunction "VCC_2_28") (pintype "power_in"))
      (node (ref "U2") (pin "36") (pinfunction "VCC_3_36") (pintype "power_in"))
      (node (ref "U2") (pin "42") (pinfunction "VCC_4_42") (pintype "power_in"))
      (node (ref "U2") (pin "48") (pinfunction "VCC_48") (pintype "power_in"))
      (node (ref "U3") (pin "C6") (pinfunction "VDDQ_C6") (pintype "power_in"))
      (node (ref "U3") (pin "E6") (pinfunction "VDDIO_E6") (pintype "power_in"))
      (node (ref "U3") (pin "F5") (pinfunction "VDDIO_F5") (pintype "power_in"))
      (node (ref "U3") (pin "J10") (pinfunction "VDDIO_J10") (pintype "power_in"))
      (node (ref "U3") (pin "K9") (pinfunction "VDDIO_K9") (pintype "power_in"))
      (node (ref "U3") (pin "M4") (pinfunction "VDDQ_M4") (pintype "power_in"))
      (node (ref "U3") (pin "N4") (pinfunction "VDDQ_N4") (pintype "power_in"))
      (node (ref "U3") (pin "P3") (pinfunction "VDDQ_P3") (pintype "power_in"))
      (node (ref "U3") (pin "P5") (pinfunction "VDDQ_P5") (pintype "power_in"))
      (node (ref "U7") (pin "F6") (pinfunction "SYS_VDD1_3P3V_F6") (pintype "power_in"))
      (node (ref "U7") (pin "F7") (pinfunction "SYS_VDD1_3P3V_F7") (pintype "power_in"))
      (node (ref "U7") (pin "G6") (pinfunction "SYS_VDD1_3P3V_G6") (pintype "power_in"))
      (node (ref "U7") (pin "G7") (pinfunction "SYS_VDD1_3P3V_G7") (pintype "power_in"))
    )
    (net (code "7") (name "3.3VA") (class "Default")
      (node (ref "Q1") (pin "E") (pinfunction "E_E") (pintype "passive"))
      (node (ref "R23") (pin "2") (pinfunction "2_2") (pintype "passive"))
      (node (ref "R28") (pin "2") (pinfunction "2_2") (pintype "passive"))
      (node (ref "TP165") (pin "P$1") (pinfunction "1_P$1") (pintype "bidirectional"))
      (node (ref "U7") (pin "F8") (pinfunction "SYS_VDD3_3P3V_F8") (pintype "power_in"))
      (node (ref "U7") (pin "F9") (pinfunction "VDDSHV4_F9") (pintype "power_in"))
      (node (ref "U7") (pin "G8") (pinfunction "SYS_VDD3_3P3V_G8") (pintype "power_in"))
      (node (ref "U7") (pin "G9") (pinfunction "VDDSHV5_G9") (pintype "power_in"))
      (node (ref "U7") (pin "H7") (pinfunction "SYS_VDD3_3P3V_H7") (pintype "power_in"))
      (node (ref "U7") (pin "H8") (pinfunction "SYS_VDD3_3P3V_H8") (pintype "power_in"))
      (node (ref "U7") (pin "H9") (pinfunction "VDDSHV6_H9") (pintype "power_in"))
      (node (ref "U7") (pin "J7") (pinfunction "SYS_VDD3_3P3V_J7") (pintype "power_in"))
      (node (ref "U7") (pin "J8") (pinfunction "SYS_VDD3_3P3V_J8") (pintype "power_in"))
      (node (ref "U7") (pin "J9") (pinfunction "VDDSHV1_J9") (pintype "power_in"))
      (node (ref "U7") (pin "K8") (pinfunction "SYS_VDD3_3P3V_K8") (pintype "power_in"))
      (node (ref "U7") (pin "K9") (pinfunction "VDDSHV2_K9") (pintype "power_in"))
      (node (ref "U7") (pin "L8") (pinfunction "SYS_VDD3_3P3V_L8") (pintype "power_in"))
      (node (ref "U7") (pin "L9") (pinfunction "VDDSHV3_L9") (pintype "power_in"))
    )
    (net (code "8") (name "5V") (class "Default")
      (node (ref "C14") (pin "1") (pinfunction "1_1") (pintype "passive"))
      (node (ref "C36") (pin "1") (pinfunction "1_1") (pintype "passive"))
      (node (ref "L1") (pin "2") (pinfunction "2_2") (pintype "passive"))
      (node (ref "R62") (pin "2") (pinfunction "2_2") (pintype "passive"))
      (node (ref "TP49") (pin "1") (pinfunction "1_1") (pintype "passive"))
      (node (ref "U15") (pin "10") (pinfunction "FB_10") (pintype "input"))
      (node (ref "U7") (pin "P10") (pinfunction "VIN_AC_P10") (pintype "power_in"))
      (node (ref "U7") (pin "R10") (pinfunction "VIN_AC_R10") (pintype "power_in"))
      (node (ref "U7") (pin "T10") (pinfunction "VIN_AC_T10") (pintype "power_in"))
    )
    (net (code "9") (name "AD0") (class "Default")
      (node (ref "R57") (pin "1") (pinfunction "1_1") (pintype "passive"))
      (node (ref "R58") (pin "2") (pinfunction "2_2") (pintype "passive"))
      (node (ref "R69") (pin "2") (pinfunction "2_2") (pintype "passive"))
      (node (ref "R70") (pin "1") (pinfunction "1_1") (pintype "passive"))
      (node (ref "U16") (pin "1") (pinfunction "AD0_1") (pintype "input"))
    )
    (net (code "10") (name "AD1") (class "Default")
      (node (ref "R55") (pin "1") (pinfunction "1_1") (pintype "passive"))
      (node (ref "R56") (pin "2") (pinfunction "2_2") (pintype "passive"))
      (node (ref "R67") (pin "2") (pinfunction "2_2") (pintype "passive"))
      (node (ref "R68") (pin "1") (pinfunction "1_1") (pintype "passive"))
      (node (ref "U16") (pin "2") (pinfunction "AD1_2") (pintype "input"))
    )
    (net (code "11") (name "AD2") (class "Default")
      (node (ref "R53") (pin "1") (pinfunction "1_1") (pintype "passive"))
      (node (ref "R54") (pin "2") (pinfunction "2_2") (pintype "passive"))
      (node (ref "R65") (pin "2") (pinfunction "2_2") (pintype "passive"))
      (node (ref "R66") (pin "1") (pinfunction "1_1") (pintype "passive"))
      (node (ref "U16") (pin "3") (pinfunction "AD2_3") (pintype "input"))
    )
    (net (code "12") (name "BOOT0") (class "Default")
      (node (ref "JP3") (pin "1") (pinfunction "1_1") (pintype "passive"))
      (node (ref "TP51") (pin "1") (pinfunction "1_1") (pintype "passive"))
      (node (ref "U16") (pin "10") (pinfunction "IO5_10") (pintype "bidirectional"))
    )
    (net (code "13") (name "CAN1_H") (class "Default")
      (node (ref "J4") (pin "33") (pinfunction "33_33") (pintype "passive"))
      (node (ref "J4") (pin "34") (pinfunction "34_34") (pintype "passive"))
      (node (ref "TP184") (pin "P$1") (pinfunction "1_P$1") (pintype "bidirectional"))
    )
    (net (code "14") (name "CAN1_L") (class "Default")
      (node (ref "J4") (pin "35") (pinfunction "35_35") (pintype "passive"))
      (node (ref "J4") (pin "36") (pinfunction "36_36") (pintype "passive"))
      (node (ref "TP183") (pin "P$1") (pinfunction "1_P$1") (pintype "bidirectional"))
    )
    (net (code "15") (name "CAN2_H") (class "Default")
      (node (ref "J4") (pin "17") (pinfunction "17_17") (pintype "passive"))
      (node (ref "J4") (pin "18") (pinfunction "18_18") (pintype "passive"))
      (node (ref "U11") (pin "7") (pinfunction "CANH_7") (pintype "bidirectional"))
    )
    (net (code "16") (name "CAN2_L") (class "Default")
      (node (ref "J4") (pin "19") (pinfunction "19_19") (pintype "passive"))
      (node (ref "J4") (pin "20") (pinfunction "20_20") (pintype "passive"))
      (node (ref "U11") (pin "6") (pinfunction "CANL_6") (pintype "bidirectional"))
    )
    (net (code "17") (name "CB-RESET") (class "Default")
      (node (ref "R39") (pin "2") (pinfunction "2_2") (pintype "passive"))
      (node (ref "TP54") (pin "1") (pinfunction "1_1") (pintype "passive"))
      (node (ref "U14") (pin "9") (pinfunction "CIN2-_9") (pintype "input"))
      (node (ref "U16") (pin "9") (pinfunction "IO4_9") (pintype "bidirectional"))
    )
    (net (code "18") (name "CB_CTRL") (class "Default")
      (node (ref "Q2") (pin "1") (pinfunction "G_1") (pintype "passive"))
      (node (ref "Q5") (pin "3") (pinfunction "G_3") (pintype "passive"))
      (node (ref "R64") (pin "1") (pinfunction "1_1") (pintype "passive"))
      (node (ref "TP52") (pin "1") (pinfunction "1_1") (pintype "passive"))
      (node (ref "U14") (pin "3") (pinfunction "LE_3") (pintype "input"))
      (node (ref "U14") (pin "4") (pinfunction "COUT1_4") (pintype "open_collector"))
      (node (ref "U14") (pin "6") (pinfunction "COUT2_6") (pintype "open_collector"))
    )
    (net (code "19") (name "EEPROM_WP") (class "Default")
      (node (ref "J1") (pin "20") (pinfunction "DEBUG-3_20") (pintype "passive"))
      (node (ref "R75") (pin "1") (pinfunction "1_1") (pintype "passive"))
      (node (ref "TP71") (pin "1") (pinfunction "1_1") (pintype "passive"))
    )
    (net (code "20") (name "GND") (class "Default")
      (node (ref "C1") (pin "2") (pinfunction "2_2") (pintype "passive"))
      (node (ref "C10") (pin "2") (pinfunction "2_2") (pintype "passive"))
      (node (ref "C11") (pin "2") (pinfunction "2_2") (pintype "passive"))
      (node (ref "C12") (pin "2") (pinfunction "2_2") (pintype "passive"))
      (node (ref "C13") (pin "2") (pinfunction "2_2") (pintype "passive"))
      (node (ref "C14") (pin "2") (pinfunction "2_2") (pintype "passive"))
      (node (ref "C16") (pin "2") (pinfunction "2_2") (pintype "passive"))
      (node (ref "C17") (pin "2") (pinfunction "2_2") (pintype "passive"))
      (node (ref "C18") (pin "2") (pinfunction "2_2") (pintype "passive"))
      (node (ref "C2") (pin "2") (pinfunction "2_2") (pintype "passive"))
      (node (ref "C20") (pin "2") (pinfunction "2_2") (pintype "passive"))
      (node (ref "C21") (pin "2") (pinfunction "2_2") (pintype "passive"))
      (node (ref "C23") (pin "2") (pinfunction "2_2") (pintype "passive"))
      (node (ref "C24") (pin "2") (pinfunction "2_2") (pintype "passive"))
      (node (ref "C25") (pin "2") (pinfunction "2_2") (pintype "passive"))
      (node (ref "C26") (pin "2") (pinfunction "2_2") (pintype "passive"))
      (node (ref "C27") (pin "2") (pinfunction "2_2") (pintype "passive"))
      (node (ref "C28") (pin "2") (pinfunction "2_2") (pintype "passive"))
      (node (ref "C3") (pin "2") (pinfunction "2_2") (pintype "passive"))
      (node (ref "C31") (pin "1") (pinfunction "1_1") (pintype "passive"))
      (node (ref "C32") (pin "2") (pinfunction "2_2") (pintype "passive"))
      (node (ref "C34") (pin "2") (pinfunction "2_2") (pintype "passive"))
      (node (ref "C35") (pin "2") (pinfunction "2_2") (pintype "passive"))
      (node (ref "C36") (pin "2") (pinfunction "2_2") (pintype "passive"))
      (node (ref "C37") (pin "2") (pinfunction "2_2") (pintype "passive"))
      (node (ref "C38") (pin "2") (pinfunction "2_2") (pintype "passive"))
      (node (ref "C39") (pin "1") (pinfunction "1_1") (pintype "passive"))
      (node (ref "C4") (pin "2") (pinfunction "2_2") (pintype "passive"))
      (node (ref "C40") (pin "1") (pinfunction "1_1") (pintype "passive"))
      (node (ref "C42") (pin "2") (pinfunction "2_2") (pintype "passive"))
      (node (ref "C43") (pin "2") (pinfunction "2_2") (pintype "passive"))
      (node (ref "C44") (pin "2") (pinfunction "2_2") (pintype "passive"))
      (node (ref "C45") (pin "2") (pinfunction "2_2") (pintype "passive"))
      (node (ref "C46") (pin "2") (pinfunction "2_2") (pintype "passive"))
      (node (ref "C47") (pin "2") (pinfunction "2_2") (pintype "passive"))
      (node (ref "C48") (pin "2") (pinfunction "2_2") (pintype "passive"))
      (node (ref "C49") (pin "2") (pinfunction "2_2") (pintype "passive"))
      (node (ref "C5") (pin "2") (pinfunction "2_2") (pintype "passive"))
      (node (ref "C50") (pin "2") (pinfunction "2_2") (pintype "passive"))
      (node (ref "C51") (pin "2") (pinfunction "2_2") (pintype "passive"))
      (node (ref "C6") (pin "2") (pinfunction "2_2") (pintype "passive"))
      (node (ref "C7") (pin "2") (pinfunction "2_2") (pintype "passive"))
      (node (ref "C8") (pin "2") (pinfunction "2_2") (pintype "passive"))
      (node (ref "C9") (pin "2") (pinfunction "2_2") (pintype "passive"))
      (node (ref "D1") (pin "C") (pinfunction "C_C") (pintype "passive"))
      (node (ref "D2") (pin "C") (pinfunction "C_C") (pintype "passive"))
      (node (ref "D3") (pin "C") (pinfunction "C_C") (pintype "passive"))
      (node (ref "D4") (pin "C") (pinfunction "C_C") (pintype "passive"))
      (node (ref "D5") (pin "C") (pinfunction "C_C") (pintype "passive"))
      (node (ref "D6") (pin "C") (pinfunction "C_C") (pintype "passive"))
      (node (ref "D7") (pin "C") (pinfunction "C_C") (pintype "passive"))
      (node (ref "D8") (pin "C") (pinfunction "C_C") (pintype "passive"))
      (node (ref "J1") (pin "3") (pinfunction "GND_3") (pintype "passive"))
      (node (ref "J1") (pin "6") (pinfunction "GND_6") (pintype "passive"))
      (node (ref "J1") (pin "9") (pinfunction "GND_9") (pintype "passive"))
      (node (ref "J1") (pin "PAD1") (pinfunction "PAD_PAD1") (pintype "bidirectional"))
      (node (ref "J1") (pin "PAD2") (pinfunction "PAD_PAD2") (pintype "bidirectional"))
      (node (ref "J100") (pin "6") (pinfunction "VSS_6") (pintype "bidirectional"))
      (node (ref "J100") (pin "CGND1") (pinfunction "CGND_CGND1") (pintype "bidirectional"))
      (node (ref "J100") (pin "CGND2") (pinfunction "CGND_CGND2") (pintype "bidirectional"))
      (node (ref "J100") (pin "CGND3") (pinfunction "CGND_CGND3") (pintype "bidirectional"))
      (node (ref "J100") (pin "CGND4") (pinfunction "CGND_CGND4") (pintype "bidirectional"))
      (node (ref "J100") (pin "CGND5") (pinfunction "CGND_CGND5") (pintype "bidirectional"))
      (node (ref "J100") (pin "CGND6") (pinfunction "CGND_CGND6") (pintype "bidirectional"))
      (node (ref "J100") (pin "GND") (pinfunction "VSS_GND") (pintype "bidirectional"))
      (node (ref "J3") (pin "3") (pinfunction "3_3") (pintype "passive"))
      (node (ref "J4") (pin "27") (pinfunction "27_27") (pintype "passive"))
      (node (ref "J4") (pin "28") (pinfunction "28_28") (pintype "passive"))
      (node (ref "J4") (pin "29") (pinfunction "29_29") (pintype "passive"))
      (node (ref "J4") (pin "30") (pinfunction "30_30") (pintype "passive"))
      (node (ref "J4") (pin "31") (pinfunction "31_31") (pintype "passive"))
      (node (ref "J4") (pin "32") (pinfunction "32_32") (pintype "passive"))
      (node (ref "J4") (pin "37") (pinfunction "37_37") (pintype "passive"))
      (node (ref "J4") (pin "38") (pinfunction "38_38") (pintype "passive"))
      (node (ref "Q2") (pin "2") (pinfunction "S_2") (pintype "passive"))
      (node (ref "Q4") (pin "2") (pinfunction "S_2") (pintype "passive"))
      (node (ref "R11") (pin "1") (pinfunction "1_1") (pintype "passive"))
      (node (ref "R14") (pin "1") (pinfunction "1_1") (pintype "passive"))
      (node (ref "R15") (pin "1") (pinfunction "1_1") (pintype "passive"))
      (node (ref "R16") (pin "1") (pinfunction "1_1") (pintype "passive"))
      (node (ref "R16") (pin "2") (pinfunction "2_2") (pintype "passive"))
      (node (ref "R16") (pin "3") (pinfunction "3_3") (pintype "passive"))
      (node (ref "R16") (pin "4") (pinfunction "4_4") (pintype "passive"))
      (node (ref "R16") (pin "5") (pinfunction "5_5") (pintype "passive"))
      (node (ref "R16") (pin "6") (pinfunction "6_6") (pintype "passive"))
      (node (ref "R16") (pin "7") (pinfunction "7_7") (pintype "passive"))
      (node (ref "R16") (pin "8") (pinfunction "8_8") (pintype "passive"))
      (node (ref "R17") (pin "1") (pinfunction "1_1") (pintype "passive"))
      (node (ref "R17") (pin "2") (pinfunction "2_2") (pintype "passive"))
      (node (ref "R17") (pin "3") (pinfunction "3_3") (pintype "passive"))
      (node (ref "R17") (pin "4") (pinfunction "4_4") (pintype "passive"))
      (node (ref "R33") (pin "1") (pinfunction "1_1") (pintype "passive"))
      (node (ref "R39") (pin "1") (pinfunction "1_1") (pintype "passive"))
      (node (ref "R40") (pin "1") (pinfunction "1_1") (pintype "passive"))
      (node (ref "R42") (pin "1") (pinfunction "1_1") (pintype "passive"))
      (node (ref "R46") (pin "1") (pinfunction "1_1") (pintype "passive"))
      (node (ref "R51") (pin "1") (pinfunction "1_1") (pintype "passive"))
      (node (ref "R54") (pin "1") (pinfunction "1_1") (pintype "passive"))
      (node (ref "R56") (pin "1") (pinfunction "1_1") (pintype "passive"))
      (node (ref "R58") (pin "1") (pinfunction "1_1") (pintype "passive"))
      (node (ref "R59") (pin "2") (pinfunction "2_2") (pintype "passive"))
      (node (ref "TP72") (pin "1") (pinfunction "1_1") (pintype "passive"))
      (node (ref "TP74") (pin "1") (pinfunction "1_1") (pintype "passive"))
      (node (ref "TP75") (pin "1") (pinfunction "1_1") (pintype "passive"))
      (node (ref "TP77") (pin "1") (pinfunction "1_1") (pintype "passive"))
      (node (ref "TP78") (pin "1") (pinfunction "1_1") (pintype "passive"))
      (node (ref "U1") (pin "2") (pinfunction "GND_2") (pintype "power_in"))
      (node (ref "U11") (pin "2") (pinfunction "GND_2") (pintype "power_in"))
      (node (ref "U12") (pin "2") (pinfunction "GND_2") (pintype "power_in"))
      (node (ref "U13") (pin "2") (pinfunction "GND_2") (pintype "power_in"))
      (node (ref "U14") (pin "7") (pinfunction "GND_7") (pintype "power_in"))
      (node (ref "U14") (pin "EPAD") (pinfunction "GND_EPAD") (pintype "power_in"))
      (node (ref "U15") (pin "1") (pinfunction "GND_1") (pintype "power_in"))
      (node (ref "U15") (pin "11") (pinfunction "GND_11") (pintype "power_in"))
      (node (ref "U15") (pin "12") (pinfunction "GND_12") (pintype "power_in"))
      (node (ref "U15") (pin "16") (pinfunction "GND_16") (pintype "power_in"))
      (node (ref "U15") (pin "6") (pinfunction "LBO_6") (pintype "open_collector"))
      (node (ref "U15") (pin "7") (pinfunction "LBI_7") (pintype "input"))
      (node (ref "U15") (pin "9") (pinfunction "GND_9") (pintype "power_in"))
      (node (ref "U15") (pin "PAD") (pinfunction "GND_PAD") (pintype "power_in"))
      (node (ref "U16") (pin "6") (pinfunction "GND_6") (pintype "power_in"))
      (node (ref "U16") (pin "EPAD") (pinfunction "GND_EPAD") (pintype "power_in"))
      (node (ref "U17") (pin "4") (pinfunction "GND_4") (pintype "power_in"))
      (node (ref "U2") (pin "13") (pinfunction "GND_13") (pintype "power_in"))
      (node (ref "U2") (pin "18") (pinfunction "GND_18") (pintype "power_in"))
      (node (ref "U2") (pin "19") (pinfunction "GND_19") (pintype "power_in"))
      (node (ref "U2") (pin "21") (pinfunction "GND_21") (pintype "power_in"))
      (node (ref "U2") (pin "25") (pinfunction "GND_25") (pintype "power_in"))
      (node (ref "U2") (pin "3") (pinfunction "GND_3") (pintype "power_in"))
      (node (ref "U2") (pin "32") (pinfunction "GND_32") (pintype "power_in"))
      (node (ref "U2") (pin "38") (pinfunction "GND_38") (pintype "power_in"))
      (node (ref "U2") (pin "44") (pinfunction "GND_44") (pintype "power_in"))
      (node (ref "U2") (pin "7") (pinfunction "GND_7") (pintype "power_in"))
      (node (ref "U3") (pin "A6") (pinfunction "VSSIO_A6") (pintype "power_in"))
      (node (ref "U3") (pin "C4") (pinfunction "VSSQ_C4") (pintype "power_in"))
      (node (ref "U3") (pin "E7") (pinfunction "VSSIO_E7") (pintype "power_in"))
      (node (ref "U3") (pin "G5") (pinfunction "VSSIO_G5") (pintype "power_in"))
      (node (ref "U3") (pin "H10") (pinfunction "VSSIO_H10") (pintype "power_in"))
      (node (ref "U3") (pin "J5") (pinfunction "VSSIO_J5") (pintype "power_in"))
      (node (ref "U3") (pin "K8") (pinfunction "VSSIO_K8") (pintype "power_in"))
      (node (ref "U3") (pin "N2") (pinfunction "VSSQ_N2") (pintype "power_in"))
      (node (ref "U3") (pin "N5") (pinfunction "VSSQ_N5") (pintype "power_in"))
      (node (ref "U3") (pin "P4") (pinfunction "VSSQ_P4") (pintype "power_in"))
      (node (ref "U3") (pin "P6") (pinfunction "VSSQ_P6") (pintype "power_in"))
      (node (ref "U4") (pin "3") (pinfunction "GND_3") (pintype "bidirectional"))
      (node (ref "U7") (pin "A9") (pinfunction "AGND_ADC_A9") (pintype "bidirectional"))
      (node (ref "U7") (pin "B9") (pinfunction "VREFN_B9") (pintype "bidirectional"))
      (node (ref "U7") (pin "D8") (pinfunction "DGND_D8") (pintype "bidirectional"))
      (node (ref "U7") (pin "D9") (pinfunction "DGND_D9") (pintype "bidirectional"))
      (node (ref "U7") (pin "E10") (pinfunction "DGND_E10") (pintype "bidirectional"))
      (node (ref "U7") (pin "E11") (pinfunction "DGND_E11") (pintype "bidirectional"))
      (node (ref "U7") (pin "E12") (pinfunction "DGND_E12") (pintype "bidirectional"))
      (node (ref "U7") (pin "E5") (pinfunction "DGND_E5") (pintype "bidirectional"))
      (node (ref "U7") (pin "E6") (pinfunction "DGND_E6") (pintype "bidirectional"))
      (node (ref "U7") (pin "E7") (pinfunction "DGND_E7") (pintype "bidirectional"))
      (node (ref "U7") (pin "E8") (pinfunction "DGND_E8") (pintype "bidirectional"))
      (node (ref "U7") (pin "E9") (pinfunction "DGND_E9") (pintype "bidirectional"))
      (node (ref "U7") (pin "F12") (pinfunction "DGND_F12") (pintype "bidirectional"))
      (node (ref "U7") (pin "F5") (pinfunction "DGND_F5") (pintype "bidirectional"))
      (node (ref "U7") (pin "G12") (pinfunction "DGND_G12") (pintype "bidirectional"))
      (node (ref "U7") (pin "G5") (pinfunction "DGND_G5") (pintype "bidirectional"))
      (node (ref "U7") (pin "H12") (pinfunction "DGND_H12") (pintype "bidirectional"))
      (node (ref "U7") (pin "H13") (pinfunction "DGND_H13") (pintype "bidirectional"))
      (node (ref "U7") (pin "H4") (pinfunction "DGND_H4") (pintype "bidirectional"))
      (node (ref "U7") (pin "H5") (pinfunction "DGND_H5") (pintype "bidirectional"))
      (node (ref "U7") (pin "J12") (pinfunction "DGND_J12") (pintype "bidirectional"))
      (node (ref "U7") (pin "J13") (pinfunction "DGND_J13") (pintype "bidirectional"))
      (node (ref "U7") (pin "J4") (pinfunction "DGND_J4") (pintype "bidirectional"))
      (node (ref "U7") (pin "J5") (pinfunction "DGND_J5") (pintype "bidirectional"))
      (node (ref "U7") (pin "K12") (pinfunction "DGND_K12") (pintype "bidirectional"))
      (node (ref "U7") (pin "K5") (pinfunction "DGND_K5") (pintype "bidirectional"))
      (node (ref "U7") (pin "L12") (pinfunction "DGND_L12") (pintype "bidirectional"))
      (node (ref "U7") (pin "L14") (pinfunction "USB1_ID_L14") (pintype "bidirectional"))
      (node (ref "U7") (pin "L5") (pinfunction "DGND_L5") (pintype "bidirectional"))
      (node (ref "U7") (pin "M10") (pinfunction "DGND_M10") (pintype "bidirectional"))
      (node (ref "U7") (pin "M11") (pinfunction "DGND_M11") (pintype "bidirectional"))
      (node (ref "U7") (pin "M12") (pinfunction "DGND_M12") (pintype "bidirectional"))
      (node (ref "U7") (pin "M5") (pinfunction "DGND_M5") (pintype "bidirectional"))
      (node (ref "U7") (pin "M6") (pinfunction "DGND_M6") (pintype "bidirectional"))
      (node (ref "U7") (pin "M7") (pinfunction "DGND_M7") (pintype "bidirectional"))
      (node (ref "U7") (pin "M8") (pinfunction "DGND_M8") (pintype "bidirectional"))
      (node (ref "U7") (pin "M9") (pinfunction "DGND_M9") (pintype "bidirectional"))
      (node (ref "U7") (pin "N8") (pinfunction "DGND_N8") (pintype "bidirectional"))
      (node (ref "U7") (pin "N9") (pinfunction "DGND_N9") (pintype "bidirectional"))
      (node (ref "Y1") (pin "2") (pinfunction "GND_2") (pintype "power_in"))
      (node (ref "Y1") (pin "4") (pinfunction "GND_4") (pintype "power_in"))
    )
    (net (code "21") (name "I2C0_SCL") (class "Default")
      (node (ref "J1") (pin "18") (pinfunction "DEBUG-1_18") (pintype "passive"))
      (node (ref "R73") (pin "1") (pinfunction "1_1") (pintype "passive"))
      (node (ref "TP39") (pin "1") (pinfunction "1_1") (pintype "passive"))
      (node (ref "U1") (pin "6") (pinfunction "I4_6") (pintype "bidirectional"))
    )
    (net (code "22") (name "I2C0_SDA") (class "Default")
      (node (ref "J1") (pin "19") (pinfunction "DEBUG-2_19") (pintype "passive"))
      (node (ref "R74") (pin "1") (pinfunction "1_1") (pintype "passive"))
      (node (ref "TP70") (pin "1") (pinfunction "1_1") (pintype "passive"))
      (node (ref "U1") (pin "4") (pinfunction "I3_4") (pintype "bidirectional"))
    )
    (net (code "23") (name "N$118") (class "Default")
      (node (ref "C18") (pin "1") (pinfunction "1_1") (pintype "passive"))
      (node (ref "Q1") (pin "C") (pinfunction "C_C") (pintype "passive"))
      (node (ref "R31") (pin "1") (pinfunction "1_1") (pintype "passive"))
      (node (ref "TP14") (pin "P$1") (pinfunction "1_P$1") (pintype "bidirectional"))
      (node (ref "TP164") (pin "P$1") (pinfunction "1_P$1") (pintype "bidirectional"))
      (node (ref "U10") (pin "3") (pinfunction "ANODE_3") (pintype "bidirectional"))
      (node (ref "U4") (pin "5") (pinfunction "VCC_5") (pintype "bidirectional"))
      (node (ref "U7") (pin "K11") (pinfunction "SYS_RTC_1P8V_K11") (pintype "power_in"))
      (node (ref "U7") (pin "L11") (pinfunction "SYS_RTC_1P8V_L11") (pintype "power_in"))
    )
    (net (code "24") (name "Net-(C33-Pad1)") (class "Default")
      (node (ref "C33") (pin "1") (pinfunction "1_1") (pintype "passive"))
      (node (ref "R33") (pin "2") (pinfunction "2_2") (pintype "passive"))
      (node (ref "R38") (pin "2") (pinfunction "2_2") (pintype "passive"))
    )
    (net (code "25") (name "Net-(D1-PadA)") (class "Default")
      (node (ref "D1") (pin "A") (pinfunction "A_A") (pintype "passive"))
      (node (ref "R1") (pin "2") (pinfunction "2_2") (pintype "passive"))
    )
    (net (code "26") (name "Net-(D2-PadA)") (class "Default")
      (node (ref "D2") (pin "A") (pinfunction "A_A") (pintype "passive"))
      (node (ref "R2") (pin "2") (pinfunction "2_2") (pintype "passive"))
    )
    (net (code "27") (name "Net-(D3-PadA)") (class "Default")
      (node (ref "D3") (pin "A") (pinfunction "A_A") (pintype "passive"))
      (node (ref "R3") (pin "2") (pinfunction "2_2") (pintype "passive"))
    )
    (net (code "28") (name "Net-(D4-PadA)") (class "Default")
      (node (ref "D4") (pin "A") (pinfunction "A_A") (pintype "passive"))
      (node (ref "R4") (pin "2") (pinfunction "2_2") (pintype "passive"))
    )
    (net (code "29") (name "Net-(D5-PadA)") (class "Default")
      (node (ref "D5") (pin "A") (pinfunction "A_A") (pintype "passive"))
      (node (ref "R5") (pin "2") (pinfunction "2_2") (pintype "passive"))
    )
    (net (code "30") (name "Net-(D6-PadA)") (class "Default")
      (node (ref "D6") (pin "A") (pinfunction "A_A") (pintype "passive"))
      (node (ref "R49") (pin "1") (pinfunction "1_1") (pintype "passive"))
    )
    (net (code "31") (name "Net-(D7-PadA)") (class "Default")
      (node (ref "D7") (pin "A") (pinfunction "A_A") (pintype "passive"))
      (node (ref "R61") (pin "1") (pinfunction "1_1") (pintype "passive"))
    )
    (net (code "32") (name "Net-(D8-PadA)") (class "Default")
      (node (ref "D8") (pin "A") (pinfunction "A_A") (pintype "passive"))
      (node (ref "R62") (pin "1") (pinfunction "1_1") (pintype "passive"))
    )
    (net (code "33") (name "Net-(J4-Pad1)") (class "Default")
      (node (ref "J4") (pin "1") (pinfunction "1_1") (pintype "passive"))
      (node (ref "J4") (pin "2") (pinfunction "2_2") (pintype "passive"))
    )
    (net (code "34") (name "Net-(J4-Pad3)") (class "Default")
      (node (ref "J4") (pin "3") (pinfunction "3_3") (pintype "passive"))
      (node (ref "J4") (pin "4") (pinfunction "4_4") (pintype "passive"))
    )
    (net (code "35") (name "Net-(J4-Pad5)") (class "Default")
      (node (ref "J4") (pin "5") (pinfunction "5_5") (pintype "passive"))
      (node (ref "J4") (pin "6") (pinfunction "6_6") (pintype "passive"))
    )
    (net (code "36") (name "Net-(J4-Pad7)") (class "Default")
      (node (ref "J4") (pin "7") (pinfunction "7_7") (pintype "passive"))
      (node (ref "J4") (pin "8") (pinfunction "8_8") (pintype "passive"))
    )
    (net (code "37") (name "Net-(J4-Pad10)") (class "Default")
      (node (ref "J4") (pin "10") (pinfunction "10_10") (pintype "passive"))
      (node (ref "J4") (pin "9") (pinfunction "9_9") (pintype "passive"))
    )
    (net (code "38") (name "Net-(J100-CD#)") (class "Default")
      (node (ref "J100") (pin "CD") (pinfunction "CD#_CD") (pintype "bidirectional"))
      (node (ref "R8") (pin "6") (pinfunction "66_6") (pintype "passive"))
      (node (ref "TP22") (pin "P$1") (pinfunction "1_P$1") (pintype "bidirectional"))
      (node (ref "U7") (pin "C14") (pinfunction "SPI0_CS1_C14") (pintype "bidirectional"))
    )
    (net (code "39") (name "Net-(J100-CLK)") (class "Default")
      (node (ref "J100") (pin "5") (pinfunction "CLK_5") (pintype "bidirectional"))
      (node (ref "R8") (pin "3") (pinfunction "33_3") (pintype "passive"))
      (node (ref "U7") (pin "B15") (pinfunction "MMC0_CLK_B15") (pintype "bidirectional"))
    )
    (net (code "40") (name "Net-(J100-CMD{slash}DI)") (class "Default")
      (node (ref "J100") (pin "3") (pinfunction "CMD/DI_3") (pintype "bidirectional"))
      (node (ref "R8") (pin "8") (pinfunction "88_8") (pintype "passive"))
      (node (ref "U7") (pin "B16") (pinfunction "MMC0_CMD_B16") (pintype "bidirectional"))
    )
    (net (code "41") (name "Net-(J100-DAT0{slash}DO)") (class "Default")
      (node (ref "J100") (pin "7") (pinfunction "DAT0/DO_7") (pintype "bidirectional"))
      (node (ref "R8") (pin "7") (pinfunction "77_7") (pintype "passive"))
      (node (ref "U7") (pin "A16") (pinfunction "MMC0_DAT0_A16") (pintype "bidirectional"))
    )
    (net (code "42") (name "Net-(J100-DAT1)") (class "Default")
      (node (ref "J100") (pin "8") (pinfunction "DAT1_8") (pintype "bidirectional"))
      (node (ref "R8") (pin "4") (pinfunction "44_4") (pintype "passive"))
      (node (ref "U7") (pin "A15") (pinfunction "MMC0_DAT1_A15") (pintype "bidirectional"))
    )
    (net (code "43") (name "Net-(J100-DAT2)") (class "Default")
      (node (ref "J100") (pin "1") (pinfunction "DAT2_1") (pintype "bidirectional"))
      (node (ref "R8") (pin "9") (pinfunction "99_9") (pintype "passive"))
      (node (ref "U7") (pin "C16") (pinfunction "MMC0_DAT2_C16") (pintype "bidirectional"))
    )
    (net (code "44") (name "Net-(J100-DAT3{slash}CS)") (class "Default")
      (node (ref "J100") (pin "2") (pinfunction "DAT3/CS_2") (pintype "bidirectional"))
      (node (ref "R8") (pin "2") (pinfunction "22_2") (pintype "passive"))
      (node (ref "U7") (pin "C15") (pinfunction "MMC0_DAT3_C15") (pintype "bidirectional"))
    )
    (net (code "45") (name "Net-(JP2-Pad1)") (class "Default")
      (node (ref "JP2") (pin "1") (pinfunction "1_1") (pintype "passive"))
      (node (ref "R14") (pin "2") (pinfunction "2_2") (pintype "passive"))
    )
    (net (code "46") (name "Net-(JP2-Pad3)") (class "Default")
      (node (ref "JP2") (pin "3") (pinfunction "3_3") (pintype "passive"))
      (node (ref "R17") (pin "12") (pinfunction "12_12") (pintype "passive"))
    )
    (net (code "47") (name "Net-(L1-Pad1)") (class "Default")
      (node (ref "L1") (pin "1") (pinfunction "1_1") (pintype "passive"))
      (node (ref "U15") (pin "14") (pinfunction "SW_14") (pintype "output"))
      (node (ref "U15") (pin "15") (pinfunction "SW_15") (pintype "output"))
    )
    (net (code "48") (name "Net-(Q3A-G)") (class "Default")
      (node (ref "Q3") (pin "1") (pinfunction "G_1") (pintype "passive"))
      (node (ref "R35") (pin "2") (pinfunction "2_2") (pintype "passive"))
    )
    (net (code "49") (name "Net-(Q3A-S)") (class "Default")
      (node (ref "Q3") (pin "5") (pinfunction "S_5") (pintype "passive"))
      (node (ref "R48") (pin "2") (pinfunction "2_2") (pintype "passive"))
    )
    (net (code "50") (name "Net-(Q3B-G)") (class "Default")
      (node (ref "Q3") (pin "3") (pinfunction "G_3") (pintype "passive"))
      (node (ref "R43") (pin "2") (pinfunction "2_2") (pintype "passive"))
    )
    (net (code "51") (name "Net-(Q3B-S)") (class "Default")
      (node (ref "Q3") (pin "2") (pinfunction "S_2") (pintype "passive"))
      (node (ref "R41") (pin "2") (pinfunction "2_2") (pintype "passive"))
    )
    (net (code "52") (name "Net-(Q4-D)") (class "Default")
      (node (ref "Q4") (pin "3") (pinfunction "D_3") (pintype "passive"))
      (node (ref "Q6") (pin "3") (pinfunction "G_3") (pintype "passive"))
      (node (ref "R52") (pin "1") (pinfunction "1_1") (pintype "passive"))
    )
    (net (code "53") (name "Net-(Q5-S)") (class "Default")
      (node (ref "Q5") (pin "4") (pinfunction "S_4") (pintype "passive"))
      (node (ref "R63") (pin "2") (pinfunction "2_2") (pintype "passive"))
      (node (ref "R64") (pin "2") (pinfunction "2_2") (pintype "passive"))
      (node (ref "U14") (pin "15") (pinfunction "RS-_15") (pintype "passive"))
    )
    (net (code "54") (name "Net-(R9-22)") (class "Default")
      (node (ref "R9") (pin "2") (pinfunction "22_2") (pintype "passive"))
      (node (ref "U3") (pin "M5") (pinfunction "CMD_M5") (pintype "input"))
      (node (ref "U7") (pin "P1") (pinfunction "GPMC_CSN2_P1") (pintype "bidirectional"))
    )
    (net (code "55") (name "Net-(R9-33)") (class "Default")
      (node (ref "R9") (pin "3") (pinfunction "33_3") (pintype "passive"))
      (node (ref "U3") (pin "K5") (pinfunction "~{RST}_K5") (pintype "input"))
      (node (ref "U7") (pin "R13") (pinfunction "GPMC_A4_R13") (pintype "bidirectional"))
    )
    (net (code "56") (name "Net-(R9-44)") (class "Default")
      (node (ref "R9") (pin "4") (pinfunction "44_4") (pintype "passive"))
      (node (ref "U3") (pin "B2") (pinfunction "D3_B2") (pintype "input"))
      (node (ref "U7") (pin "T3") (pinfunction "GPMC_AD3_T3") (pintype "bidirectional"))
    )
    (net (code "57") (name "Net-(R9-66)") (class "Default")
      (node (ref "R9") (pin "6") (pinfunction "66_6") (pintype "passive"))
      (node (ref "U3") (pin "A3") (pinfunction "D0_A3") (pintype "input"))
      (node (ref "U7") (pin "R3") (pinfunction "GPMC_AD0_R3") (pintype "bidirectional"))
    )
    (net (code "58") (name "Net-(R9-77)") (class "Default")
      (node (ref "R9") (pin "7") (pinfunction "77_7") (pintype "passive"))
      (node (ref "U3") (pin "B3") (pinfunction "D4_B3") (pintype "input"))
      (node (ref "U7") (pin "T2") (pinfunction "GPMC_AD4_T2") (pintype "bidirectional"))
    )
    (net (code "59") (name "Net-(R9-88)") (class "Default")
      (node (ref "R9") (pin "8") (pinfunction "88_8") (pintype "passive"))
      (node (ref "U3") (pin "B4") (pinfunction "D5_B4") (pintype "input"))
      (node (ref "U7") (pin "T1") (pinfunction "GPMC_AD5_T1") (pintype "bidirectional"))
    )
    (net (code "60") (name "Net-(R9-99)") (class "Default")
      (node (ref "R9") (pin "9") (pinfunction "99_9") (pintype "passive"))
      (node (ref "U3") (pin "M6") (pinfunction "SCK_M6") (pintype "input"))
      (node (ref "U7") (pin "P2") (pinfunction "GPMC_CSN1_P2") (pintype "bidirectional"))
    )
    (net (code "61") (name "Net-(R10-11)") (class "Default")
      (node (ref "R10") (pin "1") (pinfunction "11_1") (pintype "passive"))
      (node (ref "U3") (pin "A4") (pinfunction "D1_A4") (pintype "input"))
      (node (ref "U7") (pin "R2") (pinfunction "GPMC_AD1_R2") (pintype "bidirectional"))
    )
    (net (code "62") (name "Net-(R10-22)") (class "Default")
      (node (ref "R10") (pin "2") (pinfunction "22_2") (pintype "passive"))
      (node (ref "U3") (pin "B6") (pinfunction "D7_B6") (pintype "input"))
      (node (ref "U7") (pin "R4") (pinfunction "GPMC_AD7_R4") (pintype "bidirectional"))
    )
    (net (code "63") (name "Net-(R10-88)") (class "Default")
      (node (ref "R10") (pin "8") (pinfunction "88_8") (pintype "passive"))
      (node (ref "U3") (pin "B5") (pinfunction "D6_B5") (pintype "bidirectional"))
      (node (ref "U7") (pin "P4") (pinfunction "GPMC_AD6_P4") (pintype "bidirectional"))
    )
    (net (code "64") (name "Net-(R10-99)") (class "Default")
      (node (ref "R10") (pin "9") (pinfunction "99_9") (pintype "passive"))
      (node (ref "U3") (pin "A5") (pinfunction "D2_A5") (pintype "input"))
      (node (ref "U7") (pin "R1") (pinfunction "GPMC_AD2_R1") (pintype "bidirectional"))
    )
    (net (code "65") (name "Net-(TP4-1)") (class "Default")
      (node (ref "TP4") (pin "P$1") (pinfunction "1_P$1") (pintype "bidirectional"))
      (node (ref "U7") (pin "B10") (pinfunction "UART1_CTSN_B10") (pintype "bidirectional"))
    )
    (net (code "66") (name "Net-(TP5-1)") (class "Default")
      (node (ref "TP5") (pin "P$1") (pinfunction "1_P$1") (pintype "bidirectional"))
      (node (ref "U7") (pin "C1") (pinfunction "TDI_C1") (pintype "bidirectional"))
    )
    (net (code "67") (name "Net-(TP6-1)") (class "Default")
      (node (ref "TP6") (pin "P$1") (pinfunction "1_P$1") (pintype "bidirectional"))
      (node (ref "U7") (pin "C2") (pinfunction "TDO_C2") (pintype "bidirectional"))
    )
    (net (code "68") (name "Net-(TP7-1)") (class "Default")
      (node (ref "TP7") (pin "P$1") (pinfunction "1_P$1") (pintype "bidirectional"))
      (node (ref "U7") (pin "D1") (pinfunction "TCK_D1") (pintype "bidirectional"))
    )
    (net (code "69") (name "Net-(TP8-1)") (class "Default")
      (node (ref "TP8") (pin "P$1") (pinfunction "1_P$1") (pintype "bidirectional"))
      (node (ref "U7") (pin "D2") (pinfunction "TMS_D2") (pintype "bidirectional"))
    )
    (net (code "70") (name "Net-(TP9-1)") (class "Default")
      (node (ref "TP9") (pin "P$1") (pinfunction "1_P$1") (pintype "bidirectional"))
      (node (ref "U7") (pin "D3") (pinfunction "TRSTN_D3") (pintype "bidirectional"))
    )
    (net (code "71") (name "Net-(TP10-1)") (class "Default")
      (node (ref "TP10") (pin "P$1") (pinfunction "1_P$1") (pintype "bidirectional"))
      (node (ref "U7") (pin "E2") (pinfunction "EMU0_E2") (pintype "bidirectional"))
    )
    (net (code "72") (name "Net-(TP11-1)") (class "Default")
      (node (ref "TP11") (pin "P$1") (pinfunction "1_P$1") (pintype "bidirectional"))
      (node (ref "U7") (pin "E3") (pinfunction "EMU1_E3") (pintype "bidirectional"))
    )
    (net (code "73") (name "Net-(TP12-1)") (class "Default")
      (node (ref "TP12") (pin "P$1") (pinfunction "1_P$1") (pintype "bidirectional"))
      (node (ref "U7") (pin "M14") (pinfunction "USB1_DRVVBUS_M14") (pintype "bidirectional"))
    )
    (net (code "74") (name "Net-(TP13-1)") (class "Default")
      (node (ref "TP13") (pin "P$1") (pinfunction "1_P$1") (pintype "bidirectional"))
      (node (ref "U7") (pin "A10") (pinfunction "UART1_RTSN_A10") (pintype "bidirectional"))
    )
    (net (code "75") (name "Net-(TP15-1)") (class "Default")
      (node (ref "TP15") (pin "P$1") (pinfunction "1_P$1") (pintype "bidirectional"))
      (node (ref "U7") (pin "L15") (pinfunction "USB1_DP_L15") (pintype "bidirectional"))
    )
    (net (code "76") (name "Net-(TP16-1)") (class "Default")
      (node (ref "TP16") (pin "P$1") (pinfunction "1_P$1") (pintype "bidirectional"))
      (node (ref "U7") (pin "L16") (pinfunction "USB1_DM_L16") (pintype "bidirectional"))
    )
    (net (code "77") (name "Net-(TP17-1)") (class "Default")
      (node (ref "TP17") (pin "P$1") (pinfunction "1_P$1") (pintype "bidirectional"))
      (node (ref "U7") (pin "M15") (pinfunction "USB1_VBUS_M15") (pintype "bidirectional"))
    )
    (net (code "78") (name "Net-(TP35-1)") (class "Default")
      (node (ref "TP35") (pin "P$1") (pinfunction "1_P$1") (pintype "bidirectional"))
      (node (ref "U11") (pin "5") (pinfunction "SHDN_5") (pintype "input"))
    )
    (net (code "79") (name "Net-(TP36-1)") (class "Default")
      (node (ref "TP36") (pin "P$1") (pinfunction "1_P$1") (pintype "bidirectional"))
      (node (ref "U7") (pin "B8") (pinfunction "AIN1_B8") (pintype "bidirectional"))
    )
    (net (code "80") (name "Net-(TP37-1)") (class "Default")
      (node (ref "TP37") (pin "P$1") (pinfunction "1_P$1") (pintype "bidirectional"))
      (node (ref "U7") (pin "B6") (pinfunction "AIN2_B6") (pintype "bidirectional"))
    )
    (net (code "81") (name "Net-(TP38-1)") (class "Default")
      (node (ref "TP38") (pin "P$1") (pinfunction "1_P$1") (pintype "bidirectional"))
      (node (ref "U7") (pin "C6") (pinfunction "AIN3_C6") (pintype "bidirectional"))
    )
    (net (code "82") (name "Net-(TP40-1)") (class "Default")
      (node (ref "TP40") (pin "P$1") (pinfunction "1_P$1") (pintype "bidirectional"))
      (node (ref "U11") (pin "8") (pinfunction "S_8") (pintype "input"))
    )
    (net (code "83") (name "Net-(TP69-1)") (class "Default")
      (node (ref "TP69") (pin "P$1") (pinfunction "1_P$1") (pintype "bidirectional"))
      (node (ref "U17") (pin "7") (pinfunction "~{HOLD}_7") (pintype "input"))
    )
    (net (code "84") (name "Net-(TP102-1)") (class "Default")
      (node (ref "TP102") (pin "P$1") (pinfunction "1_P$1") (pintype "bidirectional"))
      (node (ref "U7") (pin "T11") (pinfunction "PMIC_PB_IN_T11") (pintype "bidirectional"))
    )
    (net (code "85") (name "Net-(TP121-1)") (class "Default")
      (node (ref "TP121") (pin "P$1") (pinfunction "1_P$1") (pintype "bidirectional"))
      (node (ref "U7") (pin "N10") (pinfunction "PMIC_POWER_EN_N10") (pintype "output"))
      (node (ref "U7") (pin "N11") (pinfunction "PMIC_PWR_EN_N11") (pintype "input"))
    )
    (net (code "86") (name "Net-(TP129-1)") (class "Default")
      (node (ref "TP129") (pin "P$1") (pinfunction "1_P$1") (pintype "bidirectional"))
      (node (ref "U7") (pin "N6") (pinfunction "PMIC_TS_N6") (pintype "bidirectional"))
    )
    (net (code "87") (name "Net-(TP130-1)") (class "Default")
      (node (ref "TP130") (pin "P$1") (pinfunction "1_P$1") (pintype "bidirectional"))
      (node (ref "U7") (pin "N7") (pinfunction "PMIC_BAT_SENSE_N7") (pintype "bidirectional"))
      (node (ref "U7") (pin "P8") (pinfunction "VIN_BAT_P8") (pintype "power_in"))
      (node (ref "U7") (pin "R8") (pinfunction "VIN_BAT_R8") (pintype "power_in"))
      (node (ref "U7") (pin "T8") (pinfunction "VIN_BAT_T8") (pintype "power_in"))
    )
    (net (code "88") (name "Net-(TP132-1)") (class "Default")
      (node (ref "TP132") (pin "P$1") (pinfunction "1_P$1") (pintype "bidirectional"))
      (node (ref "U7") (pin "N4") (pinfunction "PMIC_LDO_PGOOD_N4") (pintype "output"))
      (node (ref "U7") (pin "N5") (pinfunction "RTC_PWRONRSTN_N5") (pintype "bidirectional"))
    )
    (net (code "89") (name "Net-(TP133-1)") (class "Default")
      (node (ref "TP133") (pin "P$1") (pinfunction "1_P$1") (pintype "bidirectional"))
      (node (ref "U7") (pin "N13") (pinfunction "PMIC_MUX_IN_N13") (pintype "bidirectional"))
    )
    (net (code "90") (name "Net-(TP136-1)") (class "Default")
      (node (ref "TP136") (pin "P$1") (pinfunction "1_P$1") (pintype "bidirectional"))
      (node (ref "U7") (pin "M13") (pinfunction "PMIC_NRESET_M13") (pintype "bidirectional"))
    )
    (net (code "91") (name "Net-(TP138-1)") (class "Default")
      (node (ref "TP138") (pin "P$1") (pinfunction "1_P$1") (pintype "bidirectional"))
      (node (ref "U7") (pin "K14") (pinfunction "USB0_ID_K14") (pintype "bidirectional"))
    )
    (net (code "92") (name "Net-(TP139-1)") (class "Default")
      (node (ref "TP139") (pin "P$1") (pinfunction "1_P$1") (pintype "bidirectional"))
      (node (ref "U7") (pin "J15") (pinfunction "USB0_DRVVBUS_J15") (pintype "bidirectional"))
    )
    (net (code "93") (name "Net-(TP140-1)") (class "Default")
      (node (ref "TP140") (pin "P$1") (pinfunction "1_P$1") (pintype "bidirectional"))
      (node (ref "U7") (pin "L4") (pinfunction "PMIC_NWAKEUP_L4") (pintype "output"))
      (node (ref "U7") (pin "M4") (pinfunction "EXT_WAKEUP_M4") (pintype "bidirectional"))
    )
    (net (code "94") (name "Net-(TP141-1)") (class "Default")
      (node (ref "TP141") (pin "P$1") (pinfunction "1_P$1") (pintype "bidirectional"))
      (node (ref "U7") (pin "K13") (pinfunction "USB0_CE_K13") (pintype "bidirectional"))
    )
    (net (code "95") (name "Net-(TP144-1)") (class "Default")
      (node (ref "TP144") (pin "P$1") (pinfunction "1_P$1") (pintype "bidirectional"))
      (node (ref "U7") (pin "L13") (pinfunction "USB1_CE_L13") (pintype "bidirectional"))
    )
    (net (code "96") (name "Net-(TP154-1)") (class "Default")
      (node (ref "TP154") (pin "P$1") (pinfunction "1_P$1") (pintype "bidirectional"))
      (node (ref "U7") (pin "G4") (pinfunction "VDD_CORE_G4") (pintype "bidirectional"))
    )
    (net (code "97") (name "Net-(TP156-1)") (class "Default")
      (node (ref "TP156") (pin "P$1") (pinfunction "1_P$1") (pintype "bidirectional"))
      (node (ref "U7") (pin "F4") (pinfunction "VDDS_DDR_F4") (pintype "bidirectional"))
    )
    (net (code "98") (name "Net-(TP157-1)") (class "Default")
      (node (ref "TP157") (pin "P$1") (pinfunction "1_P$1") (pintype "bidirectional"))
      (node (ref "U7") (pin "H6") (pinfunction "VPP_H6") (pintype "bidirectional"))
    )
    (net (code "99") (name "Net-(TP160-1)") (class "Default")
      (node (ref "TP160") (pin "P$1") (pinfunction "1_P$1") (pintype "bidirectional"))
      (node (ref "U7") (pin "F13") (pinfunction "VDD_MPU_F13") (pintype "bidirectional"))
    )
    (net (code "100") (name "Net-(TP161-1)") (class "Default")
      (node (ref "TP161") (pin "P$1") (pinfunction "1_P$1") (pintype "bidirectional"))
      (node (ref "U7") (pin "F11") (pinfunction "SYS_VDD2_3P3V_F11") (pintype "power_in"))
      (node (ref "U7") (pin "G11") (pinfunction "SYS_VDD2_3P3V_G11") (pintype "power_in"))
    )
    (net (code "101") (name "Net-(TP163-1)") (class "Default")
      (node (ref "TP163") (pin "P$1") (pinfunction "1_P$1") (pintype "bidirectional"))
      (node (ref "U7") (pin "F10") (pinfunction "SYS_VDD_1P8V_F10") (pintype "power_in"))
      (node (ref "U7") (pin "G10") (pinfunction "SYS_VDD_1P8V_G10") (pintype "power_in"))
      (node (ref "U7") (pin "H10") (pinfunction "SYS_VDD_1P8V_H10") (pintype "power_in"))
      (node (ref "U7") (pin "H11") (pinfunction "SYS_VDD_1P8V_H11") (pintype "power_in"))
      (node (ref "U7") (pin "J10") (pinfunction "SYS_VDD_1P8V_J10") (pintype "power_in"))
      (node (ref "U7") (pin "J11") (pinfunction "SYS_VDD_1P8V_J11") (pintype "power_in"))
      (node (ref "U7") (pin "K10") (pinfunction "SYS_VDD_1P8V_K10") (pintype "power_in"))
      (node (ref "U7") (pin "L10") (pinfunction "SYS_VDD_1P8V_L10") (pintype "power_in"))
    )
    (net (code "102") (name "Net-(TP166-1)") (class "Default")
      (node (ref "TP166") (pin "P$1") (pinfunction "1_P$1") (pintype "bidirectional"))
      (node (ref "U7") (pin "G13") (pinfunction "VDDS_PLL_G13") (pintype "bidirectional"))
    )
    (net (code "103") (name "Net-(TP167-1)") (class "Default")
      (node (ref "TP167") (pin "P$1") (pinfunction "1_P$1") (pintype "bidirectional"))
      (node (ref "U7") (pin "D4") (pinfunction "EXTINTN_D4") (pintype "bidirectional"))
      (node (ref "U7") (pin "E4") (pinfunction "PMIC_NINT_E4") (pintype "output"))
    )
    (net (code "104") (name "Net-(TP168-1)") (class "Default")
      (node (ref "TP168") (pin "P$1") (pinfunction "1_P$1") (pintype "bidirectional"))
      (node (ref "U7") (pin "D6") (pinfunction "PMIC_MUX_OUT_D6") (pintype "bidirectional"))
    )
    (net (code "105") (name "Net-(TP173-1)") (class "Default")
      (node (ref "TP173") (pin "P$1") (pinfunction "1_P$1") (pintype "bidirectional"))
      (node (ref "U7") (pin "D5") (pinfunction "CAP_VDD_RTC_D5") (pintype "bidirectional"))
    )
    (net (code "106") (name "Net-(U2-RXIN1+)") (class "Default")
      (node (ref "R30") (pin "1") (pinfunction "1_1") (pintype "passive"))
      (node (ref "U2") (pin "11") (pinfunction "RXIN1+_11") (pintype "input"))
    )
    (net (code "107") (name "Net-(U2-RXIN1-)") (class "Default")
      (node (ref "R30") (pin "2") (pinfunction "2_2") (pintype "passive"))
      (node (ref "U2") (pin "10") (pinfunction "RXIN1-_10") (pintype "input"))
    )
    (net (code "108") (name "Net-(U2-RXIN2+)") (class "Default")
      (node (ref "R29") (pin "1") (pinfunction "1_1") (pintype "passive"))
      (node (ref "U2") (pin "15") (pinfunction "RXIN2+_15") (pintype "input"))
    )
    (net (code "109") (name "Net-(U2-RXIN2-)") (class "Default")
      (node (ref "R29") (pin "2") (pinfunction "2_2") (pintype "passive"))
      (node (ref "U2") (pin "14") (pinfunction "RXIN2-_14") (pintype "input"))
    )
    (net (code "110") (name "Net-(U2-~{PWR_DWN})") (class "Default")
      (node (ref "JP1") (pin "2") (pinfunction "2_2") (pintype "passive"))
      (node (ref "U2") (pin "22") (pinfunction "~{PWR_DWN}_22") (pintype "input"))
    )
    (net (code "111") (name "Net-(U3-VDDI)") (class "Default")
      (node (ref "C10") (pin "1") (pinfunction "1_1") (pintype "passive"))
      (node (ref "C12") (pin "1") (pinfunction "1_1") (pintype "passive"))
      (node (ref "U3") (pin "C2") (pinfunction "VDDI_C2") (pintype "power_in"))
    )
    (net (code "112") (name "Net-(U7A-EEPROM_WP)") (class "Default")
      (node (ref "R75") (pin "2") (pinfunction "2_2") (pintype "passive"))
      (node (ref "U7") (pin "M2") (pinfunction "EEPROM_WP_M2") (pintype "bidirectional"))
    )
    (net (code "113") (name "Net-(U7A-I2C0_SCL)") (class "Default")
      (node (ref "R73") (pin "2") (pinfunction "2_2") (pintype "passive"))
      (node (ref "U7") (pin "C10") (pinfunction "I2C0_SCL_C10") (pintype "bidirectional"))
      (node (ref "U7") (pin "D10") (pinfunction "PMIC_SCL_D10") (pintype "bidirectional"))
    )
    (net (code "114") (name "Net-(U7A-I2C0_SDA)") (class "Default")
      (node (ref "R74") (pin "2") (pinfunction "2_2") (pintype "passive"))
      (node (ref "U7") (pin "C11") (pinfunction "I2C0_SDA_C11") (pintype "bidirectional"))
      (node (ref "U7") (pin "D11") (pinfunction "PMIC_SDA_D11") (pintype "bidirectional"))
    )
    (net (code "115") (name "Net-(U7A-RTC_KALDO_ENN)") (class "Default")
      (node (ref "R15") (pin "2") (pinfunction "2_2") (pintype "passive"))
      (node (ref "U7") (pin "M16") (pinfunction "RTC_KALDO_ENN_M16") (pintype "bidirectional"))
    )
    (net (code "116") (name "Net-(U7B-OSC1_GND)") (class "Default")
      (node (ref "C29") (pin "2") (pinfunction "2_2") (pintype "passive"))
      (node (ref "C30") (pin "2") (pinfunction "2_2") (pintype "passive"))
      (node (ref "U7") (pin "B5") (pinfunction "OSC1_GND_B5") (pintype "bidirectional"))
    )
    (net (code "117") (name "Net-(U7B-OSC1_IN)") (class "Default")
      (node (ref "C30") (pin "1") (pinfunction "1_1") (pintype "passive"))
      (node (ref "R27") (pin "2") (pinfunction "2_2") (pintype "passive"))
      (node (ref "U7") (pin "A6") (pinfunction "OSC1_IN_A6") (pintype "bidirectional"))
      (node (ref "Y2") (pin "P$2") (pinfunction "P$2_P$2") (pintype "passive"))
    )
    (net (code "118") (name "Net-(U7B-OSC1_OUT)") (class "Default")
      (node (ref "C29") (pin "1") (pinfunction "1_1") (pintype "passive"))
      (node (ref "R27") (pin "1") (pinfunction "1_1") (pintype "passive"))
      (node (ref "U7") (pin "A5") (pinfunction "OSC1_OUT_A5") (pintype "bidirectional"))
      (node (ref "Y2") (pin "P$1") (pinfunction "P$1_P$1") (pintype "passive"))
    )
    (net (code "119") (name "Net-(U7C-GPMC_A5)") (class "Default")
      (node (ref "R2") (pin "1") (pinfunction "1_1") (pintype "passive"))
      (node (ref "U7") (pin "P13") (pinfunction "GPMC_A5_P13") (pintype "bidirectional"))
    )
    (net (code "120") (name "Net-(U7C-GPMC_A6)") (class "Default")
      (node (ref "R3") (pin "1") (pinfunction "1_1") (pintype "passive"))
      (node (ref "U7") (pin "T14") (pinfunction "GPMC_A6_T14") (pintype "bidirectional"))
    )
    (net (code "121") (name "Net-(U7C-GPMC_A7)") (class "Default")
      (node (ref "R4") (pin "1") (pinfunction "1_1") (pintype "passive"))
      (node (ref "U7") (pin "R14") (pinfunction "GPMC_A7_R14") (pintype "bidirectional"))
    )
    (net (code "122") (name "Net-(U7C-GPMC_A8)") (class "Default")
      (node (ref "R5") (pin "1") (pinfunction "1_1") (pintype "passive"))
      (node (ref "U7") (pin "P14") (pinfunction "GPMC_A8_P14") (pintype "bidirectional"))
    )
    (net (code "123") (name "Net-(U10-CATHODE)") (class "Default")
      (node (ref "Q1") (pin "B") (pinfunction "B_B") (pintype "passive"))
      (node (ref "R23") (pin "1") (pinfunction "1_1") (pintype "passive"))
      (node (ref "U10") (pin "2") (pinfunction "CATHODE_2") (pintype "bidirectional"))
    )
    (net (code "124") (name "Net-(U10-REF)") (class "Default")
      (node (ref "R28") (pin "1") (pinfunction "1_1") (pintype "passive"))
      (node (ref "R31") (pin "2") (pinfunction "2_2") (pintype "passive"))
      (node (ref "U10") (pin "1") (pinfunction "REF_1") (pintype "bidirectional"))
    )
    (net (code "125") (name "Net-(U11-RXD)") (class "Default")
      (node (ref "U11") (pin "4") (pinfunction "RXD_4") (pintype "output"))
      (node (ref "U7") (pin "B11") (pinfunction "UART1_TXD_B11") (pintype "bidirectional"))
    )
    (net (code "126") (name "Net-(U11-TXD)") (class "Default")
      (node (ref "U11") (pin "1") (pinfunction "TXD_1") (pintype "input"))
      (node (ref "U7") (pin "A11") (pinfunction "UART1_RXD_A11") (pintype "bidirectional"))
    )
    (net (code "127") (name "Net-(U12-INP)") (class "Default")
      (node (ref "C32") (pin "1") (pinfunction "1_1") (pintype "passive"))
      (node (ref "R36") (pin "1") (pinfunction "1_1") (pintype "passive"))
      (node (ref "R37") (pin "1") (pinfunction "1_1") (pintype "passive"))
      (node (ref "U12") (pin "1") (pinfunction "INP_1") (pintype "input"))
    )
    (net (code "128") (name "Net-(U12-OUT)") (class "Default")
      (node (ref "R35") (pin "1") (pinfunction "1_1") (pintype "passive"))
      (node (ref "TP44") (pin "1") (pinfunction "1_1") (pintype "passive"))
      (node (ref "U12") (pin "4") (pinfunction "OUT_4") (pintype "output"))
    )
    (net (code "129") (name "Net-(U13-INP)") (class "Default")
      (node (ref "C35") (pin "1") (pinfunction "1_1") (pintype "passive"))
      (node (ref "R44") (pin "1") (pinfunction "1_1") (pintype "passive"))
      (node (ref "R45") (pin "1") (pinfunction "1_1") (pintype "passive"))
      (node (ref "U13") (pin "1") (pinfunction "INP_1") (pintype "input"))
    )
    (net (code "130") (name "Net-(U13-OUT)") (class "Default")
      (node (ref "R43") (pin "1") (pinfunction "1_1") (pintype "passive"))
      (node (ref "TP43") (pin "1") (pinfunction "1_1") (pintype "passive"))
      (node (ref "U13") (pin "4") (pinfunction "OUT_4") (pintype "output"))
    )
    (net (code "131") (name "Net-(U14-CIN1+)") (class "Default")
      (node (ref "R50") (pin "1") (pinfunction "1_1") (pintype "passive"))
      (node (ref "R51") (pin "2") (pinfunction "2_2") (pintype "passive"))
      (node (ref "TP57") (pin "1") (pinfunction "1_1") (pintype "passive"))
      (node (ref "U14") (pin "10") (pinfunction "CIN1+_10") (pintype "input"))
    )
    (net (code "132") (name "Net-(U14-CIN1-)") (class "Default")
      (node (ref "R42") (pin "2") (pinfunction "2_2") (pintype "passive"))
      (node (ref "R47") (pin "1") (pinfunction "1_1") (pintype "passive"))
      (node (ref "TP47") (pin "1") (pinfunction "1_1") (pintype "passive"))
      (node (ref "U14") (pin "11") (pinfunction "CIN1-_11") (pintype "input"))
    )
    (net (code "133") (name "Net-(U14-CIN2+)") (class "Default")
      (node (ref "R47") (pin "2") (pinfunction "2_2") (pintype "passive"))
      (node (ref "U14") (pin "12") (pinfunction "REF_12") (pintype "output"))
      (node (ref "U14") (pin "8") (pinfunction "CIN2+_8") (pintype "input"))
    )
    (net (code "134") (name "Net-(U14-INHIBIT)") (class "Default")
      (node (ref "R38") (pin "1") (pinfunction "1_1") (pintype "passive"))
      (node (ref "U14") (pin "5") (pinfunction "INHIBIT_5") (pintype "input"))
    )
    (net (code "135") (name "Net-(U14-IOUT)") (class "Default")
      (node (ref "R50") (pin "2") (pinfunction "2_2") (pintype "passive"))
      (node (ref "U14") (pin "14") (pinfunction "IOUT_14") (pintype "output"))
    )
    (net (code "136") (name "Net-(U14-RS+)") (class "Default")
      (node (ref "C44") (pin "1") (pinfunction "1_1") (pintype "passive"))
      (node (ref "Q6") (pin "1") (pinfunction "D_1") (pintype "passive"))
      (node (ref "Q6") (pin "2") (pinfunction "D_2") (pintype "passive"))
      (node (ref "Q6") (pin "5") (pinfunction "D_5") (pintype "passive"))
      (node (ref "Q6") (pin "6") (pinfunction "D_6") (pintype "passive"))
      (node (ref "R63") (pin "1") (pinfunction "1_1") (pintype "passive"))
      (node (ref "U14") (pin "16") (pinfunction "RS+_16") (pintype "passive"))
    )
    (net (code "137") (name "Net-(U15-PG)") (class "Default")
      (node (ref "TP48") (pin "1") (pinfunction "1_1") (pintype "passive"))
      (node (ref "U15") (pin "13") (pinfunction "PG_13") (pintype "open_collector"))
    )
    (net (code "138") (name "Net-(U15-SYNC)") (class "Default")
      (node (ref "R34") (pin "1") (pinfunction "1_1") (pintype "passive"))
      (node (ref "R40") (pin "2") (pinfunction "2_2") (pintype "passive"))
      (node (ref "TP46") (pin "1") (pinfunction "1_1") (pintype "passive"))
      (node (ref "U15") (pin "5") (pinfunction "SYNC_5") (pintype "input"))
    )
    (net (code "139") (name "Net-(U16-IO6)") (class "Default")
      (node (ref "TP53") (pin "1") (pinfunction "1_1") (pintype "passive"))
      (node (ref "U16") (pin "11") (pinfunction "IO6_11") (pintype "bidirectional"))
    )
    (net (code "140") (name "Net-(U16-IO7)") (class "Default")
      (node (ref "TP56") (pin "1") (pinfunction "1_1") (pintype "passive"))
      (node (ref "U16") (pin "12") (pinfunction "IO7_12") (pintype "bidirectional"))
    )
    (net (code "141") (name "Net-(U16-~{RESET})") (class "Default")
      (node (ref "R72") (pin "1") (pinfunction "1_1") (pintype "passive"))
      (node (ref "U16") (pin "13") (pinfunction "~{RESET}_13") (pintype "input"))
    )
    (net (code "142") (name "Net-(U17-MISO)") (class "Default")
      (node (ref "U17") (pin "2") (pinfunction "MISO_2") (pintype "output"))
      (node (ref "U7") (pin "B13") (pinfunction "SPI0_D0_B13") (pintype "bidirectional"))
    )
    (net (code "143") (name "Net-(U17-MOSI)") (class "Default")
      (node (ref "U17") (pin "5") (pinfunction "MOSI_5") (pintype "input"))
      (node (ref "U7") (pin "B14") (pinfunction "SPI0_D1_B14") (pintype "bidirectional"))
    )
    (net (code "144") (name "Net-(U17-SCK)") (class "Default")
      (node (ref "U17") (pin "6") (pinfunction "SCK_6") (pintype "input"))
      (node (ref "U7") (pin "A13") (pinfunction "SPI0_SCLK_A13") (pintype "bidirectional"))
    )
    (net (code "145") (name "Net-(U17-~{CS})") (class "Default")
      (node (ref "U17") (pin "1") (pinfunction "~{CS}_1") (pintype "input"))
      (node (ref "U7") (pin "A14") (pinfunction "SPI0_CS0_A14") (pintype "bidirectional"))
    )
    (net (code "146") (name "Net-(U17-~{WP})") (class "Default")
      (node (ref "R59") (pin "1") (pinfunction "1_1") (pintype "passive"))
      (node (ref "R60") (pin "2") (pinfunction "2_2") (pintype "passive"))
      (node (ref "U17") (pin "3") (pinfunction "~{WP}_3") (pintype "input"))
    )
    (net (code "147") (name "ON{slash}~{OFF}") (class "Default")
      (node (ref "C34") (pin "1") (pinfunction "1_1") (pintype "passive"))
      (node (ref "Q4") (pin "1") (pinfunction "G_1") (pintype "passive"))
      (node (ref "R46") (pin "2") (pinfunction "2_2") (pintype "passive"))
      (node (ref "R49") (pin "2") (pinfunction "2_2") (pintype "passive"))
      (node (ref "TP50") (pin "1") (pinfunction "1_1") (pintype "passive"))
      (node (ref "U14") (pin "1") (pinfunction "VCC_1") (pintype "power_in"))
      (node (ref "U16") (pin "8") (pinfunction "IO3_8") (pintype "bidirectional"))
    )
    (net (code "148") (name "OPD_PWR") (class "Default")
      (node (ref "J4") (pin "15") (pinfunction "15_15") (pintype "passive"))
      (node (ref "J4") (pin "16") (pinfunction "16_16") (pintype "passive"))
      (node (ref "R71") (pin "1") (pinfunction "1_1") (pintype "passive"))
    )
    (net (code "149") (name "OPD_SCL") (class "Default")
      (node (ref "J4") (pin "13") (pinfunction "13_13") (pintype "passive"))
      (node (ref "J4") (pin "14") (pinfunction "14_14") (pintype "passive"))
      (node (ref "R48") (pin "1") (pinfunction "1_1") (pintype "passive"))
    )
    (net (code "150") (name "OPD_SDA") (class "Default")
      (node (ref "J4") (pin "11") (pinfunction "11_11") (pintype "passive"))
      (node (ref "J4") (pin "12") (pinfunction "12_12") (pintype "passive"))
      (node (ref "R41") (pin "1") (pinfunction "1_1") (pintype "passive"))
    )
    (net (code "151") (name "OSC0_GND") (class "Default")
      (node (ref "C19") (pin "1") (pinfunction "1_1") (pintype "passive"))
      (node (ref "C22") (pin "1") (pinfunction "1_1") (pintype "passive"))
      (node (ref "U7") (pin "N15") (pinfunction "OSC0_GND_N15") (pintype "bidirectional"))
    )
    (net (code "152") (name "OSC0_IN") (class "Default")
      (node (ref "C19") (pin "2") (pinfunction "2_2") (pintype "passive"))
      (node (ref "R13") (pin "2") (pinfunction "2_2") (pintype "passive"))
      (node (ref "U7") (pin "P16") (pinfunction "OSC0_IN_P16") (pintype "bidirectional"))
      (node (ref "Y1") (pin "1") (pinfunction "X1_1") (pintype "passive"))
    )
    (net (code "153") (name "OSC0_OUT") (class "Default")
      (node (ref "C22") (pin "2") (pinfunction "2_2") (pintype "passive"))
      (node (ref "R13") (pin "1") (pinfunction "1_1") (pintype "passive"))
      (node (ref "U7") (pin "N16") (pinfunction "OSC0_OUT_N16") (pintype "bidirectional"))
      (node (ref "Y1") (pin "3") (pinfunction "X2_3") (pintype "passive"))
    )
    (net (code "154") (name "OUT1_N") (class "Default")
      (node (ref "J2") (pin "5") (pinfunction "5_5") (pintype "passive"))
      (node (ref "J2") (pin "6") (pinfunction "6_6") (pintype "passive"))
      (node (ref "R6") (pin "2") (pinfunction "2_2") (pintype "passive"))
      (node (ref "U2") (pin "8") (pinfunction "RXIN0-_8") (pintype "input"))
    )
    (net (code "155") (name "OUT1_P") (class "Default")
      (node (ref "J2") (pin "7") (pinfunction "7_7") (pintype "passive"))
      (node (ref "J2") (pin "8") (pinfunction "8_8") (pintype "passive"))
      (node (ref "R6") (pin "1") (pinfunction "1_1") (pintype "passive"))
      (node (ref "U2") (pin "9") (pinfunction "RXIN0+_9") (pintype "input"))
    )
    (net (code "156") (name "PB6{slash}SCL") (class "Default")
      (node (ref "TP67") (pin "1") (pinfunction "1_1") (pintype "passive"))
      (node (ref "U16") (pin "4") (pinfunction "IO0_4") (pintype "bidirectional"))
    )
    (net (code "157") (name "PB7{slash}SDA") (class "Default")
      (node (ref "TP68") (pin "1") (pinfunction "1_1") (pintype "passive"))
      (node (ref "U16") (pin "5") (pinfunction "IO1_5") (pintype "bidirectional"))
    )
    (net (code "158") (name "PEN-SCL-FILT") (class "Default")
      (node (ref "Q3") (pin "6") (pinfunction "D_6") (pintype "passive"))
      (node (ref "R37") (pin "2") (pinfunction "2_2") (pintype "passive"))
      (node (ref "R65") (pin "1") (pinfunction "1_1") (pintype "passive"))
      (node (ref "R67") (pin "1") (pinfunction "1_1") (pintype "passive"))
      (node (ref "R69") (pin "1") (pinfunction "1_1") (pintype "passive"))
      (node (ref "TP42") (pin "1") (pinfunction "1_1") (pintype "passive"))
      (node (ref "TP66") (pin "1") (pinfunction "1_1") (pintype "passive"))
      (node (ref "U16") (pin "15") (pinfunction "SCL_15") (pintype "input"))
    )
    (net (code "159") (name "PEN-SDA-FILT") (class "Default")
      (node (ref "Q3") (pin "4") (pinfunction "D_4") (pintype "passive"))
      (node (ref "R45") (pin "2") (pinfunction "2_2") (pintype "passive"))
      (node (ref "R66") (pin "2") (pinfunction "2_2") (pintype "passive"))
      (node (ref "R68") (pin "2") (pinfunction "2_2") (pintype "passive"))
      (node (ref "R70") (pin "2") (pinfunction "2_2") (pintype "passive"))
      (node (ref "TP41") (pin "1") (pinfunction "1_1") (pintype "passive"))
      (node (ref "TP65") (pin "1") (pinfunction "1_1") (pintype "passive"))
      (node (ref "U16") (pin "16") (pinfunction "SDA_16") (pintype "bidirectional"))
    )
    (net (code "160") (name "PMIC_PGOOD") (class "Default")
      (node (ref "TP110") (pin "P$1") (pinfunction "1_P$1") (pintype "bidirectional"))
      (node (ref "U4") (pin "2") (pinfunction "A_2") (pintype "bidirectional"))
      (node (ref "U7") (pin "N12") (pinfunction "PMIC_PGOOD_N12") (pintype "output"))
      (node (ref "U7") (pin "P11") (pinfunction "PWRONRSTN_P11") (pintype "bidirectional"))
    )
    (net (code "161") (name "POUT") (class "Default")
      (node (ref "TP64") (pin "1") (pinfunction "1_1") (pintype "passive"))
      (node (ref "U14") (pin "13") (pinfunction "POUT_13") (pintype "output"))
    )
    (net (code "162") (name "PRU0_0") (class "Default")
      (node (ref "TP30") (pin "1") (pinfunction "1_1") (pintype "passive"))
      (node (ref "U2") (pin "24") (pinfunction "RXOUT0_24") (pintype "output"))
      (node (ref "U7") (pin "A1") (pinfunction "MCASP0_ACLKX_A1") (pintype "bidirectional"))
    )
    (net (code "163") (name "PRU0_1") (class "Default")
      (node (ref "TP29") (pin "1") (pinfunction "1_1") (pintype "passive"))
      (node (ref "U2") (pin "26") (pinfunction "RXOUT1_26") (pintype "output"))
      (node (ref "U7") (pin "A2") (pinfunction "MCASP0_FSX_A2") (pintype "bidirectional"))
    )
    (net (code "164") (name "PRU0_2") (class "Default")
      (node (ref "TP28") (pin "1") (pinfunction "1_1") (pintype "passive"))
      (node (ref "U2") (pin "27") (pinfunction "RXOUT2_27") (pintype "output"))
      (node (ref "U7") (pin "B2") (pinfunction "MCASP0_AXR0_B2") (pintype "bidirectional"))
    )
    (net (code "165") (name "PRU0_3") (class "Default")
      (node (ref "TP27") (pin "1") (pinfunction "1_1") (pintype "passive"))
      (node (ref "U2") (pin "29") (pinfunction "RXOUT3_29") (pintype "output"))
      (node (ref "U7") (pin "B1") (pinfunction "MCASP0_AHCLKR_B1") (pintype "bidirectional"))
    )
    (net (code "166") (name "PRU0_4") (class "Default")
      (node (ref "TP26") (pin "1") (pinfunction "1_1") (pintype "passive"))
      (node (ref "U2") (pin "30") (pinfunction "RXOUT4_30") (pintype "output"))
      (node (ref "U7") (pin "A3") (pinfunction "MCASP0_ACLKR_A3") (pintype "bidirectional"))
    )
    (net (code "167") (name "PRU0_5") (class "Default")
      (node (ref "TP24") (pin "1") (pinfunction "1_1") (pintype "passive"))
      (node (ref "U2") (pin "31") (pinfunction "RXOUT5_31") (pintype "output"))
      (node (ref "U7") (pin "B3") (pinfunction "MCASP0_FSR_B3") (pintype "bidirectional"))
    )
    (net (code "168") (name "PRU0_6") (class "Default")
      (node (ref "TP23") (pin "1") (pinfunction "1_1") (pintype "passive"))
      (node (ref "U2") (pin "33") (pinfunction "RXOUT6_33") (pintype "output"))
      (node (ref "U7") (pin "C3") (pinfunction "MCASP0_AXR1_C3") (pintype "bidirectional"))
    )
    (net (code "169") (name "PRU0_7") (class "Default")
      (node (ref "R11") (pin "2") (pinfunction "2_2") (pintype "passive"))
      (node (ref "TP21") (pin "1") (pinfunction "1_1") (pintype "passive"))
      (node (ref "U7") (pin "C4") (pinfunction "MCASP0_AHCLKX_C4") (pintype "bidirectional"))
    )
    (net (code "170") (name "PRU0_14") (class "Default")
      (node (ref "TP33") (pin "1") (pinfunction "1_1") (pintype "passive"))
      (node (ref "U7") (pin "P6") (pinfunction "GPMC_AD12_P6") (pintype "bidirectional"))
    )
    (net (code "171") (name "PRU0_15") (class "Default")
      (node (ref "TP34") (pin "1") (pinfunction "1_1") (pintype "passive"))
      (node (ref "U7") (pin "R6") (pinfunction "GPMC_AD13_R6") (pintype "bidirectional"))
    )
    (net (code "172") (name "PRU0_16_CLK") (class "Default")
      (node (ref "TP20") (pin "1") (pinfunction "1_1") (pintype "passive"))
      (node (ref "U2") (pin "23") (pinfunction "RXCLKOUT_23") (pintype "output"))
      (node (ref "U7") (pin "B4") (pinfunction "XDMA_EVENT_INTR1_B4") (pintype "bidirectional"))
    )
    (net (code "173") (name "RESET#") (class "Default")
      (node (ref "TP109") (pin "P$1") (pinfunction "1_P$1") (pintype "bidirectional"))
      (node (ref "U4") (pin "4") (pinfunction "Y_4") (pintype "bidirectional"))
      (node (ref "U7") (pin "R11") (pinfunction "WARMRSTN_R11") (pintype "bidirectional"))
    )
    (net (code "174") (name "SENSOR_ENABLE") (class "Default")
      (node (ref "J2") (pin "13") (pinfunction "13_13") (pintype "passive"))
      (node (ref "J2") (pin "14") (pinfunction "14_14") (pintype "passive"))
      (node (ref "U7") (pin "F3") (pinfunction "LCD_VSYNC_F3") (pintype "bidirectional"))
    )
    (net (code "175") (name "SPI1_CLK") (class "Default")
      (node (ref "J2") (pin "17") (pinfunction "17_17") (pintype "passive"))
      (node (ref "J2") (pin "18") (pinfunction "18_18") (pintype "passive"))
      (node (ref "TP19") (pin "1") (pinfunction "1_1") (pintype "passive"))
      (node (ref "U7") (pin "C5") (pinfunction "ECAP0_IN_PWM0_OUT_C5") (pintype "bidirectional"))
    )
    (net (code "176") (name "SPI1_MISO") (class "Default")
      (node (ref "J2") (pin "15") (pinfunction "15_15") (pintype "passive"))
      (node (ref "J2") (pin "16") (pinfunction "16_16") (pintype "passive"))
      (node (ref "TP1") (pin "1") (pinfunction "1_1") (pintype "passive"))
      (node (ref "U7") (pin "C12") (pinfunction "UART0_CTSN_C12") (pintype "bidirectional"))
    )
    (net (code "177") (name "SPI1_MOSI") (class "Default")
      (node (ref "J2") (pin "19") (pinfunction "19_19") (pintype "passive"))
      (node (ref "J2") (pin "20") (pinfunction "20_20") (pintype "passive"))
      (node (ref "TP18") (pin "1") (pinfunction "1_1") (pintype "passive"))
      (node (ref "U7") (pin "C13") (pinfunction "UART0_RTSN_C13") (pintype "bidirectional"))
    )
    (net (code "178") (name "SYSBOOT0") (class "Default")
      (node (ref "R17") (pin "14") (pinfunction "14_14") (pintype "passive"))
      (node (ref "SB0") (pin "TP") (pinfunction "TP_TP") (pintype "input"))
      (node (ref "U7") (pin "G3") (pinfunction "LCD_DATA0_G3") (pintype "bidirectional"))
    )
    (net (code "179") (name "SYSBOOT1") (class "Default")
      (node (ref "R17") (pin "13") (pinfunction "13_13") (pintype "passive"))
      (node (ref "SB1") (pin "TP") (pinfunction "TP_TP") (pintype "input"))
      (node (ref "U7") (pin "G2") (pinfunction "LCD_DATA1_G2") (pintype "bidirectional"))
    )
    (net (code "180") (name "SYSBOOT2") (class "Default")
      (node (ref "J3") (pin "2") (pinfunction "2_2") (pintype "passive"))
      (node (ref "JP2") (pin "2") (pinfunction "2_2") (pintype "passive"))
      (node (ref "JP3") (pin "2") (pinfunction "2_2") (pintype "passive"))
      (node (ref "SB2") (pin "TP") (pinfunction "TP_TP") (pintype "input"))
      (node (ref "U7") (pin "G1") (pinfunction "LCD_DATA2_G1") (pintype "bidirectional"))
    )
    (net (code "181") (name "SYSBOOT3") (class "Default")
      (node (ref "R17") (pin "11") (pinfunction "11_11") (pintype "passive"))
      (node (ref "SB3") (pin "TP") (pinfunction "TP_TP") (pintype "input"))
      (node (ref "U7") (pin "H3") (pinfunction "LCD_DATA3_H3") (pintype "bidirectional"))
    )
    (net (code "182") (name "SYSBOOT4") (class "Default")
      (node (ref "R17") (pin "10") (pinfunction "10_10") (pintype "passive"))
      (node (ref "SB4") (pin "TP") (pinfunction "TP_TP") (pintype "input"))
      (node (ref "U7") (pin "H2") (pinfunction "LCD_DATA4_H2") (pintype "bidirectional"))
    )
    (net (code "183") (name "SYSBOOT5") (class "Default")
      (node (ref "R17") (pin "15") (pinfunction "15_15") (pintype "passive"))
      (node (ref "SB5") (pin "TP") (pinfunction "TP_TP") (pintype "input"))
      (node (ref "U7") (pin "H1") (pinfunction "LCD_DATA5_H1") (pintype "bidirectional"))
    )
    (net (code "184") (name "SYSBOOT6") (class "Default")
      (node (ref "R17") (pin "16") (pinfunction "16_16") (pintype "passive"))
      (node (ref "SB6") (pin "TP") (pinfunction "TP_TP") (pintype "input"))
      (node (ref "U7") (pin "J3") (pinfunction "LCD_DATA6_J3") (pintype "bidirectional"))
    )
    (net (code "185") (name "SYSBOOT7") (class "Default")
      (node (ref "R16") (pin "16") (pinfunction "16_16") (pintype "passive"))
      (node (ref "SB7") (pin "TP") (pinfunction "TP_TP") (pintype "input"))
      (node (ref "U7") (pin "J2") (pinfunction "LCD_DATA7_J2") (pintype "bidirectional"))
    )
    (net (code "186") (name "SYSBOOT8") (class "Default")
      (node (ref "R16") (pin "15") (pinfunction "15_15") (pintype "passive"))
      (node (ref "SB8") (pin "TP") (pinfunction "TP_TP") (pintype "input"))
      (node (ref "U7") (pin "J1") (pinfunction "LCD_DATA8_J1") (pintype "bidirectional"))
    )
    (net (code "187") (name "SYSBOOT9") (class "Default")
      (node (ref "R16") (pin "14") (pinfunction "14_14") (pintype "passive"))
      (node (ref "SB9") (pin "TP") (pinfunction "TP_TP") (pintype "input"))
      (node (ref "U7") (pin "K3") (pinfunction "LCD_DATA9_K3") (pintype "bidirectional"))
    )
    (net (code "188") (name "SYSBOOT10") (class "Default")
      (node (ref "R16") (pin "13") (pinfunction "13_13") (pintype "passive"))
      (node (ref "SB10") (pin "TP") (pinfunction "TP_TP") (pintype "input"))
      (node (ref "U7") (pin "K2") (pinfunction "LCD_DATA10_K2") (pintype "bidirectional"))
    )
    (net (code "189") (name "SYSBOOT11") (class "Default")
      (node (ref "R16") (pin "12") (pinfunction "12_12") (pintype "passive"))
      (node (ref "SB11") (pin "TP") (pinfunction "TP_TP") (pintype "input"))
      (node (ref "U7") (pin "K1") (pinfunction "LCD_DATA11_K1") (pintype "bidirectional"))
    )
    (net (code "190") (name "SYSBOOT12") (class "Default")
      (node (ref "R16") (pin "11") (pinfunction "11_11") (pintype "passive"))
      (node (ref "SB12") (pin "TP") (pinfunction "TP_TP") (pintype "input"))
      (node (ref "U7") (pin "L3") (pinfunction "LCD_DATA12_L3") (pintype "bidirectional"))
    )
    (net (code "191") (name "SYSBOOT13") (class "Default")
      (node (ref "R16") (pin "10") (pinfunction "10_10") (pintype "passive"))
      (node (ref "SB13") (pin "TP") (pinfunction "TP_TP") (pintype "input"))
      (node (ref "U7") (pin "L2") (pinfunction "LCD_DATA13_L2") (pintype "bidirectional"))
    )
    (net (code "192") (name "SYSBOOT14") (class "Default")
      (node (ref "R17") (pin "9") (pinfunction "9_9") (pintype "passive"))
      (node (ref "SB14") (pin "TP") (pinfunction "TP_TP") (pintype "input"))
      (node (ref "U7") (pin "L1") (pinfunction "LCD_DATA14_L1") (pintype "bidirectional"))
    )
    (net (code "193") (name "SYSBOOT15") (class "Default")
      (node (ref "R16") (pin "9") (pinfunction "9_9") (pintype "passive"))
      (node (ref "SB15") (pin "TP") (pinfunction "TP_TP") (pintype "input"))
      (node (ref "U7") (pin "M3") (pinfunction "LCD_DATA15_M3") (pintype "bidirectional"))
    )
    (net (code "194") (name "TEC_ENABLE") (class "Default")
      (node (ref "J2") (pin "10") (pinfunction "10_10") (pintype "passive"))
      (node (ref "J2") (pin "9") (pinfunction "9_9") (pintype "passive"))
      (node (ref "U7") (pin "F1") (pinfunction "LCD_PCLK_F1") (pintype "bidirectional"))
    )
    (net (code "195") (name "THERM+") (class "Default")
      (node (ref "C51") (pin "1") (pinfunction "1_1") (pintype "passive"))
      (node (ref "J2") (pin "11") (pinfunction "11_11") (pintype "passive"))
      (node (ref "J2") (pin "12") (pinfunction "12_12") (pintype "passive"))
      (node (ref "R21") (pin "1") (pinfunction "1_1") (pintype "passive"))
      (node (ref "U7") (pin "A8") (pinfunction "AIN0_A8") (pintype "bidirectional"))
    )
    (net (code "196") (name "TXCLK_N") (class "Default")
      (node (ref "J2") (pin "1") (pinfunction "1_1") (pintype "passive"))
      (node (ref "J2") (pin "2") (pinfunction "2_2") (pintype "passive"))
      (node (ref "R7") (pin "1") (pinfunction "1_1") (pintype "passive"))
      (node (ref "U2") (pin "16") (pinfunction "RXCLKIN-_16") (pintype "input"))
    )
    (net (code "197") (name "TXCLK_P") (class "Default")
      (node (ref "J2") (pin "3") (pinfunction "3_3") (pintype "passive"))
      (node (ref "J2") (pin "4") (pinfunction "4_4") (pintype "passive"))
      (node (ref "R7") (pin "2") (pinfunction "2_2") (pintype "passive"))
      (node (ref "U2") (pin "17") (pinfunction "RXCLKIN+_17") (pintype "input"))
    )
    (net (code "198") (name "UART0_RX") (class "Default")
      (node (ref "J1") (pin "12") (pinfunction "CARD-RX_12") (pintype "passive"))
      (node (ref "TP31") (pin "1") (pinfunction "1_1") (pintype "passive"))
      (node (ref "U7") (pin "A12") (pinfunction "UART0_RXD_A12") (pintype "bidirectional"))
    )
    (net (code "199") (name "UART0_TX") (class "Default")
      (node (ref "J1") (pin "13") (pinfunction "CARD-TX_13") (pintype "passive"))
      (node (ref "TP32") (pin "1") (pinfunction "1_1") (pintype "passive"))
      (node (ref "U7") (pin "B12") (pinfunction "UART0_TXD_B12") (pintype "bidirectional"))
    )
    (net (code "200") (name "USB_CLI_N") (class "Default")
      (node (ref "J1") (pin "5") (pinfunction "DEVICE-D-_5") (pintype "passive"))
      (node (ref "U1") (pin "3") (pinfunction "I2_3") (pintype "bidirectional"))
      (node (ref "U7") (pin "K16") (pinfunction "USB0_DM_K16") (pintype "bidirectional"))
    )
    (net (code "201") (name "USB_CLI_P") (class "Default")
      (node (ref "J1") (pin "4") (pinfunction "DEVICE-D+_4") (pintype "passive"))
      (node (ref "U1") (pin "1") (pinfunction "I1_1") (pintype "bidirectional"))
      (node (ref "U7") (pin "K15") (pinfunction "USB0_DP_K15") (pintype "bidirectional"))
    )
    (net (code "202") (name "USB_CLI_VBUS") (class "Default")
      (node (ref "FB2") (pin "1") (pinfunction "1_1") (pintype "passive"))
      (node (ref "J1") (pin "1") (pinfunction "VBUSP_1") (pintype "passive"))
      (node (ref "J1") (pin "2") (pinfunction "VBUSP_2") (pintype "passive"))
    )
    (net (code "203") (name "VBUS") (class "Default")
      (node (ref "J4") (pin "21") (pinfunction "21_21") (pintype "passive"))
      (node (ref "J4") (pin "22") (pinfunction "22_22") (pintype "passive"))
      (node (ref "J4") (pin "23") (pinfunction "23_23") (pintype "passive"))
      (node (ref "J4") (pin "24") (pinfunction "24_24") (pintype "passive"))
      (node (ref "J4") (pin "25") (pinfunction "25_25") (pintype "passive"))
      (node (ref "J4") (pin "26") (pinfunction "26_26") (pintype "passive"))
      (node (ref "Q6") (pin "4") (pinfunction "S_4") (pintype "passive"))
      (node (ref "R52") (pin "2") (pinfunction "2_2") (pintype "passive"))
    )
    (net (code "204") (name "VBUSP") (class "Default")
      (node (ref "C33") (pin "2") (pinfunction "2_2") (pintype "passive"))
      (node (ref "C37") (pin "1") (pinfunction "1_1") (pintype "passive"))
      (node (ref "C38") (pin "1") (pinfunction "1_1") (pintype "passive"))
      (node (ref "Q5") (pin "1") (pinfunction "D_1") (pintype "passive"))
      (node (ref "Q5") (pin "2") (pinfunction "D_2") (pintype "passive"))
      (node (ref "Q5") (pin "5") (pinfunction "D_5") (pintype "passive"))
      (node (ref "Q5") (pin "6") (pinfunction "D_6") (pintype "passive"))
      (node (ref "R34") (pin "2") (pinfunction "2_2") (pintype "passive"))
      (node (ref "R61") (pin "2") (pinfunction "2_2") (pintype "passive"))
      (node (ref "TP55") (pin "1") (pinfunction "1_1") (pintype "passive"))
      (node (ref "U15") (pin "2") (pinfunction "VIN_2") (pintype "power_in"))
      (node (ref "U15") (pin "3") (pinfunction "VIN_3") (pintype "power_in"))
      (node (ref "U15") (pin "4") (pinfunction "EN_4") (pintype "input"))
      (node (ref "U15") (pin "8") (pinfunction "VIN_8") (pintype "power_in"))
    )
    (net (code "205") (name "VDD") (class "Default")
      (node (ref "C4") (pin "1") (pinfunction "1_1") (pintype "passive"))
      (node (ref "TP3") (pin "P$1") (pinfunction "1_P$1") (pintype "bidirectional"))
      (node (ref "U1") (pin "5") (pinfunction "VCC_5") (pintype "power_in"))
      (node (ref "U7") (pin "K6") (pinfunction "SYS_VOUT_K6") (pintype "power_in"))
      (node (ref "U7") (pin "K7") (pinfunction "SYS_VOUT_K7") (pintype "power_in"))
      (node (ref "U7") (pin "L6") (pinfunction "SYS_VOUT_L6") (pintype "power_in"))
      (node (ref "U7") (pin "L7") (pinfunction "SYS_VOUT_L7") (pintype "power_in"))
    )
    (net (code "206") (name "VIN_USB") (class "Default")
      (node (ref "C13") (pin "1") (pinfunction "1_1") (pintype "passive"))
      (node (ref "FB2") (pin "2") (pinfunction "2_2") (pintype "passive"))
      (node (ref "U7") (pin "J16") (pinfunction "USB0_VBUS_J16") (pintype "bidirectional"))
      (node (ref "U7") (pin "P9") (pinfunction "VIN_USB_P9") (pintype "power_in"))
      (node (ref "U7") (pin "R9") (pinfunction "VIN_USB_R9") (pintype "power_in"))
      (node (ref "U7") (pin "T9") (pinfunction "VIN_USB_T9") (pintype "power_in"))
    )
    (net (code "207") (name "VPD") (class "Default")
      (node (ref "C39") (pin "2") (pinfunction "2_2") (pintype "passive"))
      (node (ref "R32") (pin "2") (pinfunction "2_2") (pintype "passive"))
      (node (ref "R36") (pin "2") (pinfunction "2_2") (pintype "passive"))
      (node (ref "R44") (pin "2") (pinfunction "2_2") (pintype "passive"))
      (node (ref "R53") (pin "2") (pinfunction "2_2") (pintype "passive"))
      (node (ref "R55") (pin "2") (pinfunction "2_2") (pintype "passive"))
      (node (ref "R57") (pin "2") (pinfunction "2_2") (pintype "passive"))
      (node (ref "R71") (pin "2") (pinfunction "2_2") (pintype "passive"))
      (node (ref "R72") (pin "2") (pinfunction "2_2") (pintype "passive"))
      (node (ref "TP63") (pin "1") (pinfunction "1_1") (pintype "passive"))
      (node (ref "U12") (pin "5") (pinfunction "VDD_5") (pintype "power_in"))
      (node (ref "U13") (pin "5") (pinfunction "VDD_5") (pintype "power_in"))
      (node (ref "U16") (pin "14") (pinfunction "V+_14") (pintype "power_in"))
    )
    (net (code "208") (name "unconnected-(J1-DEBUG-0-Pad17)") (class "Default")
      (node (ref "J1") (pin "17") (pinfunction "DEBUG-0_17") (pintype "passive"))
    )
    (net (code "209") (name "unconnected-(J1-HOST-D+-Pad7)") (class "Default")
      (node (ref "J1") (pin "7") (pinfunction "HOST-D+_7") (pintype "passive"))
    )
    (net (code "210") (name "unconnected-(J1-HOST-D--Pad8)") (class "Default")
      (node (ref "J1") (pin "8") (pinfunction "HOST-D-_8") (pintype "passive"))
    )
    (net (code "211") (name "unconnected-(J1-NRST-Pad10)") (class "Default")
      (node (ref "J1") (pin "10") (pinfunction "NRST_10") (pintype "passive"))
    )
    (net (code "212") (name "unconnected-(J1-SWCLK-Pad15)") (class "Default")
      (node (ref "J1") (pin "15") (pinfunction "SWCLK_15") (pintype "passive"))
    )
    (net (code "213") (name "unconnected-(J1-SWDIO-Pad14)") (class "Default")
      (node (ref "J1") (pin "14") (pinfunction "SWDIO_14") (pintype "passive"))
    )
    (net (code "214") (name "unconnected-(J1-SWO-Pad16)") (class "Default")
      (node (ref "J1") (pin "16") (pinfunction "SWO_16") (pintype "passive"))
    )
    (net (code "215") (name "unconnected-(J1-VTARGET-Pad11)") (class "Default")
      (node (ref "J1") (pin "11") (pinfunction "VTARGET_11") (pintype "passive"))
    )
    (net (code "216") (name "unconnected-(R8-11-Pad1)") (class "Default")
      (node (ref "R8") (pin "1") (pinfunction "11_1") (pintype "passive"))
    )
    (net (code "217") (name "unconnected-(R9-11-Pad1)") (class "Default")
      (node (ref "R9") (pin "1") (pinfunction "11_1") (pintype "passive"))
    )
    (net (code "218") (name "unconnected-(R10-33-Pad3)") (class "Default")
      (node (ref "R10") (pin "3") (pinfunction "33_3") (pintype "passive"))
    )
    (net (code "219") (name "unconnected-(R10-44-Pad4)") (class "Default")
      (node (ref "R10") (pin "4") (pinfunction "44_4") (pintype "passive"))
    )
    (net (code "220") (name "unconnected-(R10-66-Pad6)") (class "Default")
      (node (ref "R10") (pin "6") (pinfunction "66_6") (pintype "passive"))
    )
    (net (code "221") (name "unconnected-(R10-77-Pad7)") (class "Default")
      (node (ref "R10") (pin "7") (pinfunction "77_7") (pintype "passive"))
    )
    (net (code "222") (name "unconnected-(U2-RXOUT7-Pad34)") (class "Default")
      (node (ref "U2") (pin "34") (pinfunction "RXOUT7_34") (pintype "output"))
    )
    (net (code "223") (name "unconnected-(U2-RXOUT8-Pad35)") (class "Default")
      (node (ref "U2") (pin "35") (pinfunction "RXOUT8_35") (pintype "output"))
    )
    (net (code "224") (name "unconnected-(U2-RXOUT9-Pad37)") (class "Default")
      (node (ref "U2") (pin "37") (pinfunction "RXOUT9_37") (pintype "output"))
    )
    (net (code "225") (name "unconnected-(U2-RXOUT10-Pad39)") (class "Default")
      (node (ref "U2") (pin "39") (pinfunction "RXOUT10_39") (pintype "output"))
    )
    (net (code "226") (name "unconnected-(U2-RXOUT11-Pad40)") (class "Default")
      (node (ref "U2") (pin "40") (pinfunction "RXOUT11_40") (pintype "output"))
    )
    (net (code "227") (name "unconnected-(U2-RXOUT12-Pad41)") (class "Default")
      (node (ref "U2") (pin "41") (pinfunction "RXOUT12_41") (pintype "output"))
    )
    (net (code "228") (name "unconnected-(U2-RXOUT13-Pad43)") (class "Default")
      (node (ref "U2") (pin "43") (pinfunction "RXOUT13_43") (pintype "output"))
    )
    (net (code "229") (name "unconnected-(U2-RXOUT14-Pad45)") (class "Default")
      (node (ref "U2") (pin "45") (pinfunction "RXOUT14_45") (pintype "output"))
    )
    (net (code "230") (name "unconnected-(U2-RXOUT15-Pad46)") (class "Default")
      (node (ref "U2") (pin "46") (pinfunction "RXOUT15_46") (pintype "output"))
    )
    (net (code "231") (name "unconnected-(U2-RXOUT16-Pad47)") (class "Default")
      (node (ref "U2") (pin "47") (pinfunction "RXOUT16_47") (pintype "output"))
    )
    (net (code "232") (name "unconnected-(U2-RXOUT17-Pad1)") (class "Default")
      (node (ref "U2") (pin "1") (pinfunction "RXOUT17_1") (pintype "output"))
    )
    (net (code "233") (name "unconnected-(U2-RXOUT18-Pad2)") (class "Default")
      (node (ref "U2") (pin "2") (pinfunction "RXOUT18_2") (pintype "output"))
    )
    (net (code "234") (name "unconnected-(U2-RXOUT19-Pad4)") (class "Default")
      (node (ref "U2") (pin "4") (pinfunction "RXOUT19_4") (pintype "output"))
    )
    (net (code "235") (name "unconnected-(U2-RXOUT20-Pad5)") (class "Default")
      (node (ref "U2") (pin "5") (pinfunction "RXOUT20_5") (pintype "output"))
    )
    (net (code "236") (name "unconnected-(U7B-AIN4-PadC7)") (class "Default")
      (node (ref "U7") (pin "C7") (pinfunction "AIN4_C7") (pintype "bidirectional"))
    )
    (net (code "237") (name "unconnected-(U7B-AIN5-PadC8)") (class "Default")
      (node (ref "U7") (pin "C8") (pinfunction "AIN5_C8") (pintype "bidirectional"))
    )
    (net (code "238") (name "unconnected-(U7B-AIN6-PadC9)") (class "Default")
      (node (ref "U7") (pin "C9") (pinfunction "AIN6_C9") (pintype "bidirectional"))
    )
    (net (code "239") (name "unconnected-(U7B-AIN7-PadD7)") (class "Default")
      (node (ref "U7") (pin "D7") (pinfunction "AIN7_D7") (pintype "bidirectional"))
    )
    (net (code "240") (name "unconnected-(U7C-GPMC_A0-PadT12)") (class "Default")
      (node (ref "U7") (pin "T12") (pinfunction "GPMC_A0_T12") (pintype "bidirectional"))
    )
    (net (code "241") (name "unconnected-(U7C-GPMC_A1-PadR12)") (class "Default")
      (node (ref "U7") (pin "R12") (pinfunction "GPMC_A1_R12") (pintype "bidirectional"))
    )
    (net (code "242") (name "unconnected-(U7C-GPMC_A2-PadP12)") (class "Default")
      (node (ref "U7") (pin "P12") (pinfunction "GPMC_A2_P12") (pintype "bidirectional"))
    )
    (net (code "243") (name "unconnected-(U7C-GPMC_A3-PadT13)") (class "Default")
      (node (ref "U7") (pin "T13") (pinfunction "GPMC_A3_T13") (pintype "bidirectional"))
    )
    (net (code "244") (name "unconnected-(U7C-GPMC_A9-PadT15)") (class "Default")
      (node (ref "U7") (pin "T15") (pinfunction "GPMC_A9_T15") (pintype "bidirectional"))
    )
    (net (code "245") (name "unconnected-(U7C-GPMC_A10-PadR15)") (class "Default")
      (node (ref "U7") (pin "R15") (pinfunction "GPMC_A10_R15") (pintype "bidirectional"))
    )
    (net (code "246") (name "unconnected-(U7C-GPMC_A11-PadT16)") (class "Default")
      (node (ref "U7") (pin "T16") (pinfunction "GPMC_A11_T16") (pintype "bidirectional"))
    )
    (net (code "247") (name "unconnected-(U7C-GPMC_AD8-PadT4)") (class "Default")
      (node (ref "U7") (pin "T4") (pinfunction "GPMC_AD8_T4") (pintype "bidirectional"))
    )
    (net (code "248") (name "unconnected-(U7C-GPMC_AD9-PadP5)") (class "Default")
      (node (ref "U7") (pin "P5") (pinfunction "GPMC_AD9_P5") (pintype "bidirectional"))
    )
    (net (code "249") (name "unconnected-(U7C-GPMC_AD10-PadR5)") (class "Default")
      (node (ref "U7") (pin "R5") (pinfunction "GPMC_AD10_R5") (pintype "bidirectional"))
    )
    (net (code "250") (name "unconnected-(U7C-GPMC_AD11-PadT5)") (class "Default")
      (node (ref "U7") (pin "T5") (pinfunction "GPMC_AD11_T5") (pintype "bidirectional"))
    )
    (net (code "251") (name "unconnected-(U7C-GPMC_AD14-PadT6)") (class "Default")
      (node (ref "U7") (pin "T6") (pinfunction "GPMC_AD14_T6") (pintype "bidirectional"))
    )
    (net (code "252") (name "unconnected-(U7C-GPMC_AD15-PadP7)") (class "Default")
      (node (ref "U7") (pin "P7") (pinfunction "GPMC_AD15_P7") (pintype "bidirectional"))
    )
    (net (code "253") (name "unconnected-(U7C-GPMC_ADVN_ALE-PadM1)") (class "Default")
      (node (ref "U7") (pin "M1") (pinfunction "GPMC_ADVN_ALE_M1") (pintype "bidirectional"))
    )
    (net (code "254") (name "unconnected-(U7C-GPMC_BEN0_CLE-PadN3)") (class "Default")
      (node (ref "U7") (pin "N3") (pinfunction "GPMC_BEN0_CLE_N3") (pintype "bidirectional"))
    )
    (net (code "255") (name "unconnected-(U7C-GPMC_BEN1-PadN14)") (class "Default")
      (node (ref "U7") (pin "N14") (pinfunction "GPMC_BEN1_N14") (pintype "bidirectional"))
    )
    (net (code "256") (name "unconnected-(U7C-GPMC_CLK-PadT7)") (class "Default")
      (node (ref "U7") (pin "T7") (pinfunction "GPMC_CLK_T7") (pintype "bidirectional"))
    )
    (net (code "257") (name "unconnected-(U7C-GPMC_CSN0-PadP3)") (class "Default")
      (node (ref "U7") (pin "P3") (pinfunction "GPMC_CSN0_P3") (pintype "bidirectional"))
    )
    (net (code "258") (name "unconnected-(U7C-GPMC_CSN3-PadR7)") (class "Default")
      (node (ref "U7") (pin "R7") (pinfunction "GPMC_CSN3_R7") (pintype "bidirectional"))
    )
    (net (code "259") (name "unconnected-(U7C-GPMC_OEN_REN-PadN1)") (class "Default")
      (node (ref "U7") (pin "N1") (pinfunction "GPMC_OEN_REN_N1") (pintype "bidirectional"))
    )
    (net (code "260") (name "unconnected-(U7C-GPMC_WAIT0-PadP15)") (class "Default")
      (node (ref "U7") (pin "P15") (pinfunction "GPMC_WAIT0_P15") (pintype "bidirectional"))
    )
    (net (code "261") (name "unconnected-(U7C-GPMC_WEN-PadN2)") (class "Default")
      (node (ref "U7") (pin "N2") (pinfunction "GPMC_WEN_N2") (pintype "bidirectional"))
    )
    (net (code "262") (name "unconnected-(U7C-GPMC_WPN-PadR16)") (class "Default")
      (node (ref "U7") (pin "R16") (pinfunction "GPMC_WPN_R16") (pintype "bidirectional"))
    )
    (net (code "263") (name "unconnected-(U7C-XDMA_EVENT_INTR0-PadA4)") (class "Default")
      (node (ref "U7") (pin "A4") (pinfunction "XDMA_EVENT_INTR0_A4") (pintype "bidirectional"))
    )
    (net (code "264") (name "unconnected-(U7D-LCD_AC_BIAS_EN-PadE1)") (class "Default")
      (node (ref "U7") (pin "E1") (pinfunction "LCD_AC_BIAS_EN_E1") (pintype "bidirectional"))
    )
    (net (code "265") (name "unconnected-(U7D-LCD_HSYNC-PadF2)") (class "Default")
      (node (ref "U7") (pin "F2") (pinfunction "LCD_HSYNC_F2") (pintype "bidirectional"))
    )
    (net (code "266") (name "unconnected-(U7D-MDC-PadD13)") (class "Default")
      (node (ref "U7") (pin "D13") (pinfunction "MDC_D13") (pintype "bidirectional"))
    )
    (net (code "267") (name "unconnected-(U7D-MDIO-PadE13)") (class "Default")
      (node (ref "U7") (pin "E13") (pinfunction "MDIO_E13") (pintype "bidirectional"))
    )
    (net (code "268") (name "unconnected-(U7D-MII1_COL-PadF15)") (class "Default")
      (node (ref "U7") (pin "F15") (pinfunction "MII1_COL_F15") (pintype "bidirectional"))
    )
    (net (code "269") (name "unconnected-(U7D-MII1_CRS-PadF14)") (class "Default")
      (node (ref "U7") (pin "F14") (pinfunction "MII1_CRS_F14") (pintype "bidirectional"))
    )
    (net (code "270") (name "unconnected-(U7D-MII1_RXD0-PadE14)") (class "Default")
      (node (ref "U7") (pin "E14") (pinfunction "MII1_RXD0_E14") (pintype "bidirectional"))
    )
    (net (code "271") (name "unconnected-(U7D-MII1_RXD1-PadD16)") (class "Default")
      (node (ref "U7") (pin "D16") (pinfunction "MII1_RXD1_D16") (pintype "bidirectional"))
    )
    (net (code "272") (name "unconnected-(U7D-MII1_RXD2-PadD15)") (class "Default")
      (node (ref "U7") (pin "D15") (pinfunction "MII1_RXD2_D15") (pintype "bidirectional"))
    )
    (net (code "273") (name "unconnected-(U7D-MII1_RXD3-PadD14)") (class "Default")
      (node (ref "U7") (pin "D14") (pinfunction "MII1_RXD3_D14") (pintype "bidirectional"))
    )
    (net (code "274") (name "unconnected-(U7D-MII1_RX_CLK-PadE16)") (class "Default")
      (node (ref "U7") (pin "E16") (pinfunction "MII1_RX_CLK_E16") (pintype "bidirectional"))
    )
    (net (code "275") (name "unconnected-(U7D-MII1_RX_DV-PadF16)") (class "Default")
      (node (ref "U7") (pin "F16") (pinfunction "MII1_RX_DV_F16") (pintype "bidirectional"))
    )
    (net (code "276") (name "unconnected-(U7D-MII1_RX_ER-PadE15)") (class "Default")
      (node (ref "U7") (pin "E15") (pinfunction "MII1_RX_ER_E15") (pintype "bidirectional"))
    )
    (net (code "277") (name "unconnected-(U7D-MII1_TXD0-PadH15)") (class "Default")
      (node (ref "U7") (pin "H15") (pinfunction "MII1_TXD0_H15") (pintype "bidirectional"))
    )
    (net (code "278") (name "unconnected-(U7D-MII1_TXD1-PadH14)") (class "Default")
      (node (ref "U7") (pin "H14") (pinfunction "MII1_TXD1_H14") (pintype "bidirectional"))
    )
    (net (code "279") (name "unconnected-(U7D-MII1_TXD2-PadG16)") (class "Default")
      (node (ref "U7") (pin "G16") (pinfunction "MII1_TXD2_G16") (pintype "bidirectional"))
    )
    (net (code "280") (name "unconnected-(U7D-MII1_TXD3-PadG15)") (class "Default")
      (node (ref "U7") (pin "G15") (pinfunction "MII1_TXD3_G15") (pintype "bidirectional"))
    )
    (net (code "281") (name "unconnected-(U7D-MII1_TX_CLK-PadH16)") (class "Default")
      (node (ref "U7") (pin "H16") (pinfunction "MII1_TX_CLK_H16") (pintype "bidirectional"))
    )
    (net (code "282") (name "unconnected-(U7D-MII1_TX_EN-PadG14)") (class "Default")
      (node (ref "U7") (pin "G14") (pinfunction "MII1_TX_EN_G14") (pintype "bidirectional"))
    )
    (net (code "283") (name "unconnected-(U7D-RMII1_REF_CLK-PadJ14)") (class "Default")
      (node (ref "U7") (pin "J14") (pinfunction "RMII1_REF_CLK_J14") (pintype "bidirectional"))
    )
    (net (code "284") (name "unconnected-(U7F-NC-PadD12)") (class "Default")
      (node (ref "U7") (pin "D12") (pinfunction "NC_D12") (pintype "bidirectional"))
    )
    (net (code "285") (name "unconnected-(U7F-NC-PadJ6)") (class "Default")
      (node (ref "U7") (pin "J6") (pinfunction "NC_J6") (pintype "bidirectional"))
    )
    (net (code "286") (name "unconnected-(U7F-NC-PadK4)") (class "Default")
      (node (ref "U7") (pin "K4") (pinfunction "NC_K4") (pintype "bidirectional"))
    )
    (net (code "287") (name "~{FAULT}") (class "Default")
      (node (ref "Q2") (pin "3") (pinfunction "D_3") (pintype "passive"))
      (node (ref "R32") (pin "1") (pinfunction "1_1") (pintype "passive"))
      (node (ref "TP45") (pin "1") (pinfunction "1_1") (pintype "passive"))
      (node (ref "U16") (pin "7") (pinfunction "IO2_7") (pintype "bidirectional"))
    )
    (net (code "288") (name "~{SD}") (class "Default")
      (node (ref "J4") (pin "39") (pinfunction "39_39") (pintype "passive"))
      (node (ref "J4") (pin "40") (pinfunction "40_40") (pintype "passive"))
    )
  )
)
